# distillerone.net
KiCad netlist of a schematic drawn in EAGLE
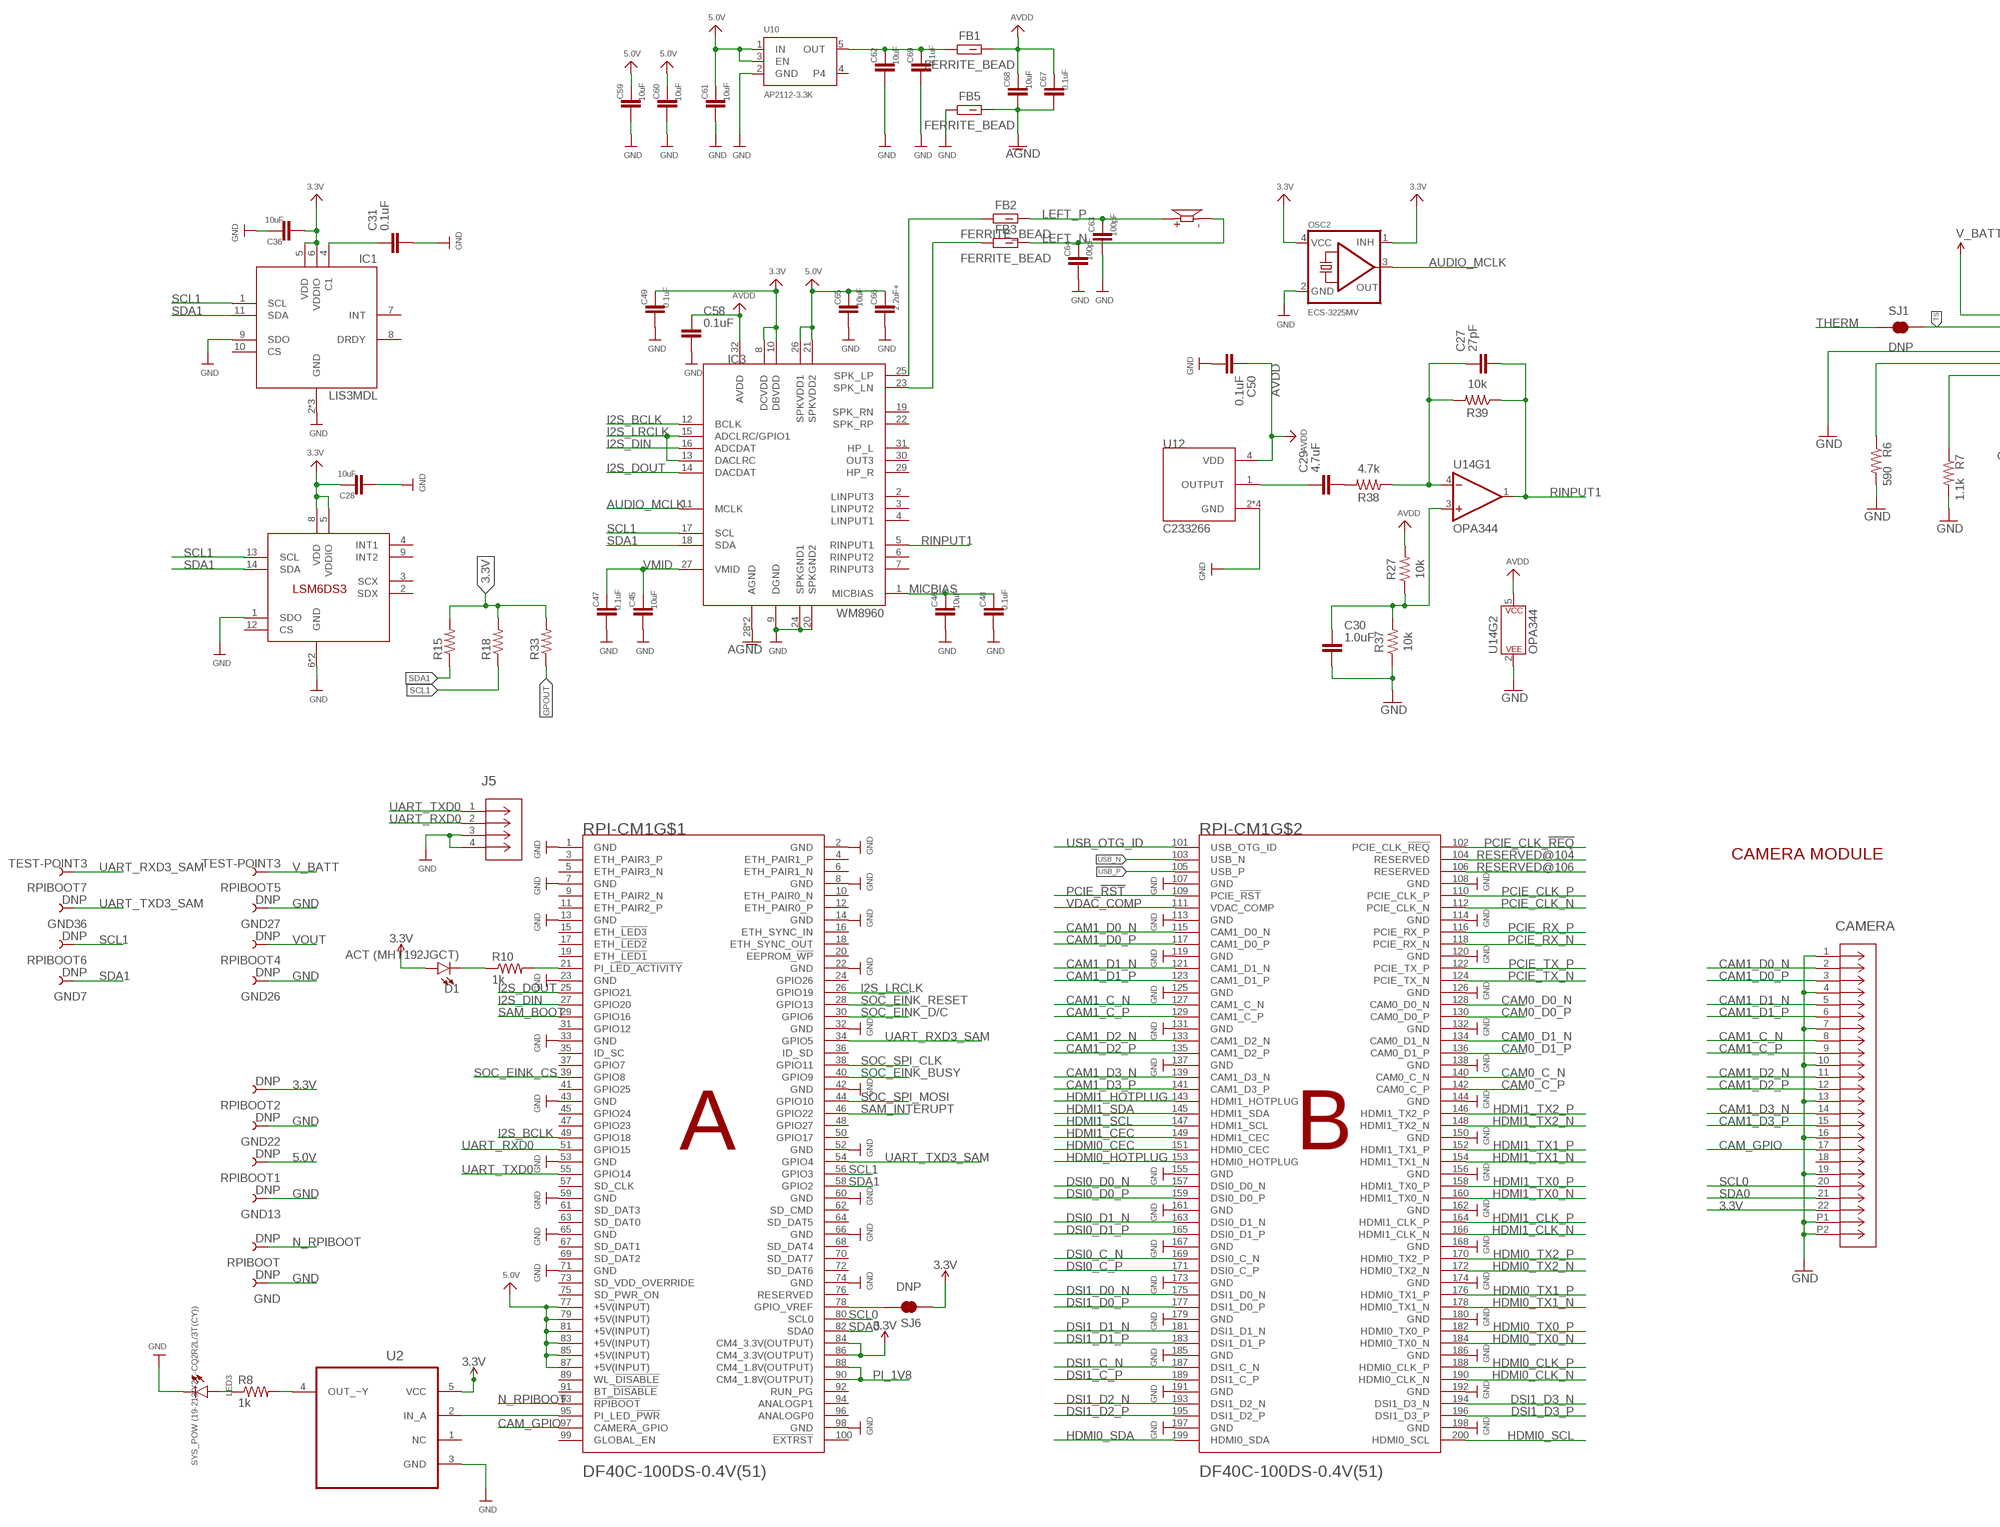
[diagram p0: schematic, sheet 1, part 1 of 3]
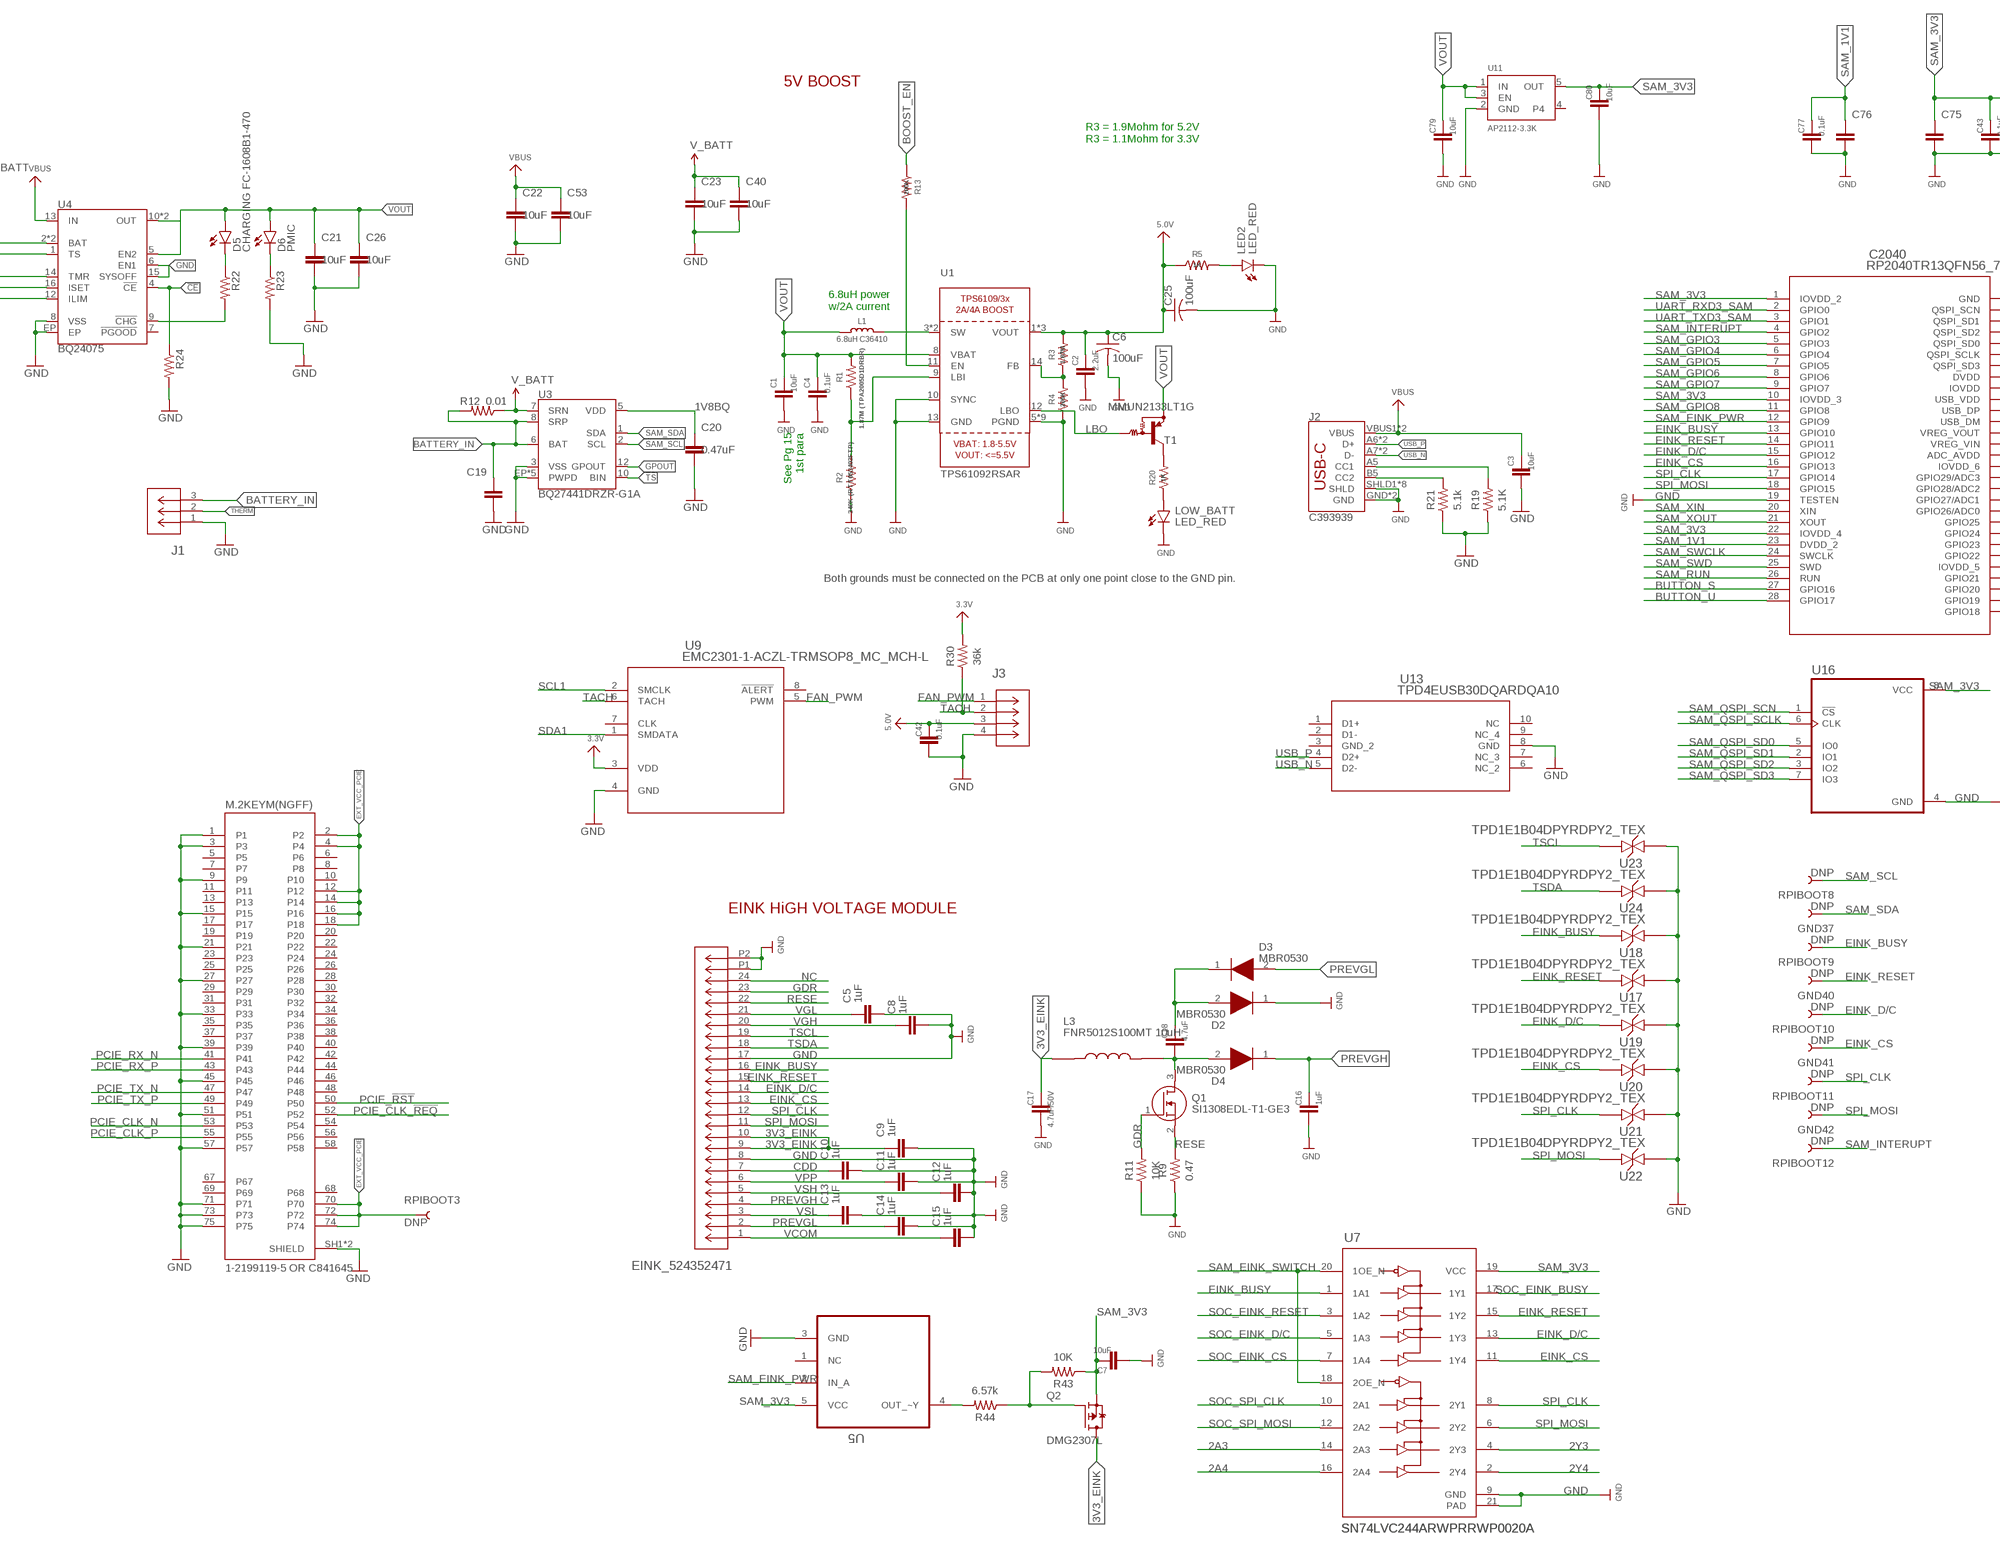
[diagram p1: schematic, sheet 1, part 2 of 3]
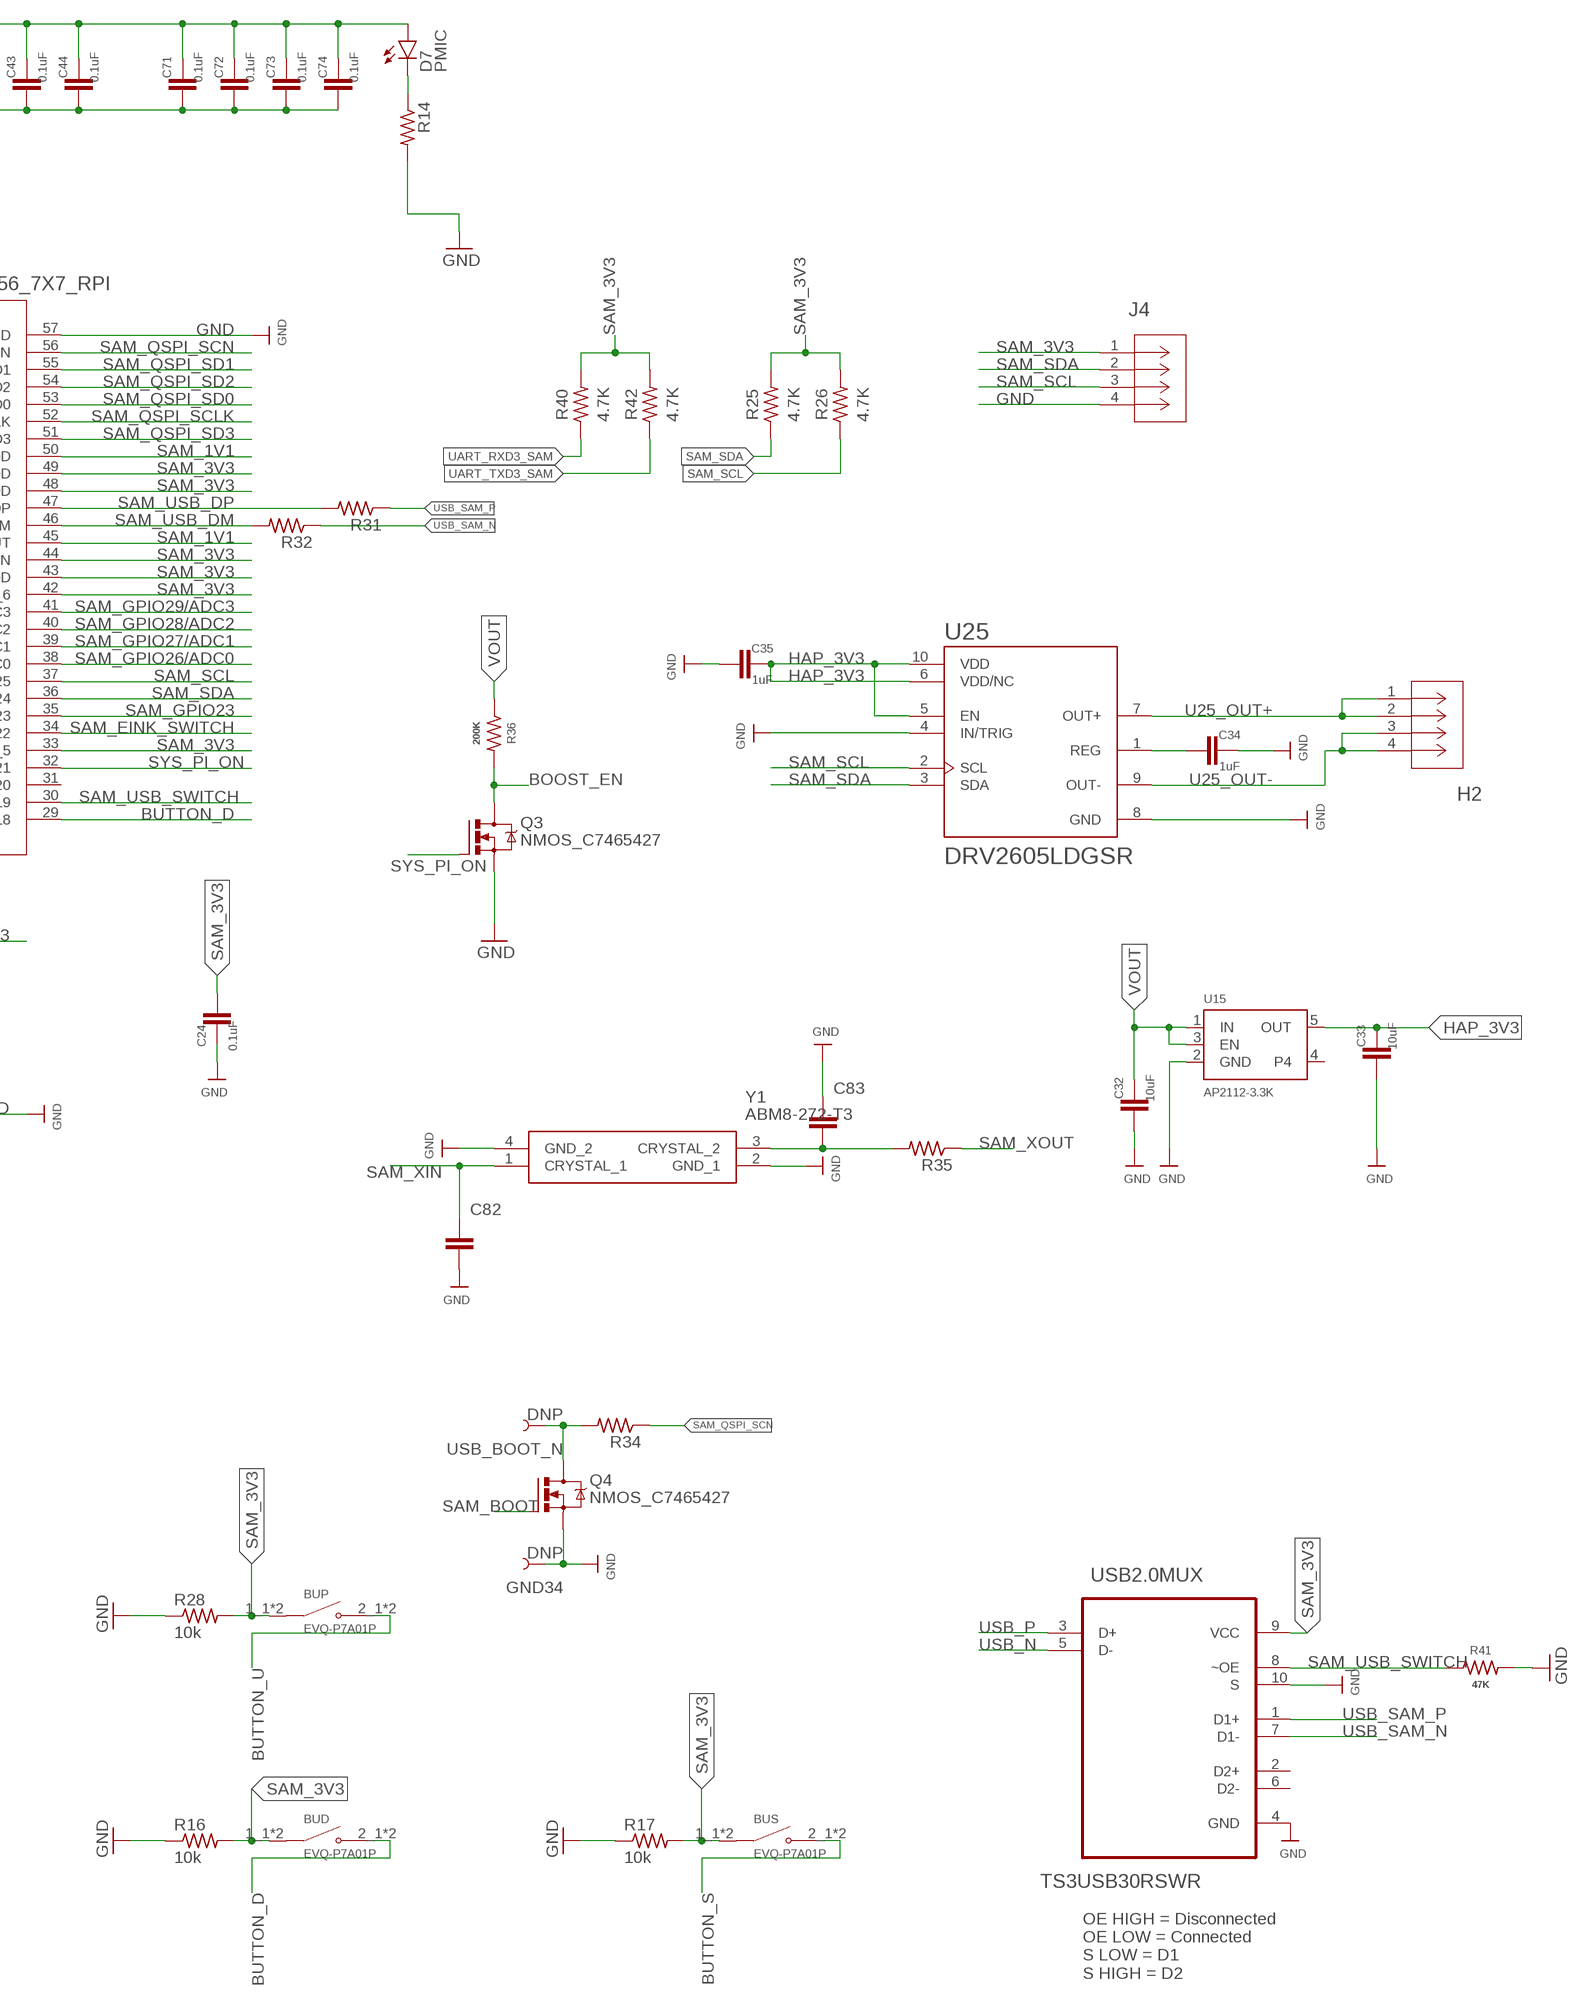
[diagram p2: schematic, sheet 1, part 3 of 3]

(export (version "E")
  (design (tool "Eeschema 10.0.6"))
  (components
    (comp (ref "BUD")
      (value "EVQ-P7A01P")
      (footprint "eagle-import:SW_EVQ-P7A01P")
      (fields (field (name "MANUFACTURER") "Panasonic Electronic Components"))
      (libsource (lib "eagle-import") (part "EVQ-P7A01P"))
    )
    (comp (ref "BUP")
      (value "EVQ-P7A01P")
      (footprint "eagle-import:SW_EVQ-P7A01P")
      (fields (field (name "MANUFACTURER") "Panasonic Electronic Components"))
      (libsource (lib "eagle-import") (part "EVQ-P7A01P"))
    )
    (comp (ref "BUS")
      (value "EVQ-P7A01P")
      (footprint "eagle-import:SW_EVQ-P7A01P")
      (fields (field (name "MANUFACTURER") "Panasonic Electronic Components"))
      (libsource (lib "eagle-import") (part "EVQ-P7A01P"))
    )
    (comp (ref "C1")
      (value "10uF")
      (footprint "eagle-import:CAPC1005X60")
      (libsource (lib "eagle-import") (part "CCHIP-0402(1005-METRIC)_"))
    )
    (comp (ref "C2")
      (value "2.2uF")
      (footprint "eagle-import:CAPC1005X60")
      (libsource (lib "eagle-import") (part "CCHIP-0402(1005-METRIC)_"))
    )
    (comp (ref "C3")
      (value "10uF")
      (footprint "eagle-import:CAPC1005X60")
      (libsource (lib "eagle-import") (part "CCHIP-0402(1005-METRIC)_"))
    )
    (comp (ref "C4")
      (value "0.1uF")
      (footprint "eagle-import:CAPC1005X60")
      (libsource (lib "eagle-import") (part "CCHIP-0402(1005-METRIC)_"))
    )
    (comp (ref "C5")
      (value "1uF")
      (footprint "eagle-import:CAPC1005X60")
      (libsource (lib "eagle-import") (part "CCHIP-0402(1005-METRIC)_"))
    )
    (comp (ref "C6")
      (value "100uF")
      (footprint "eagle-import:C1210")
      (libsource (lib "eagle-import") (part "C-USC1210"))
    )
    (comp (ref "C7")
      (value "10uF")
      (footprint "eagle-import:CAPC1005X60")
      (libsource (lib "eagle-import") (part "CCHIP-0402(1005-METRIC)_"))
    )
    (comp (ref "C8")
      (value "1uF")
      (footprint "eagle-import:CAPC1005X60")
      (libsource (lib "eagle-import") (part "CCHIP-0402(1005-METRIC)_"))
    )
    (comp (ref "C9")
      (value "1uF")
      (footprint "eagle-import:CAPC1005X60")
      (libsource (lib "eagle-import") (part "CCHIP-0402(1005-METRIC)_"))
    )
    (comp (ref "C10")
      (value "1uF")
      (footprint "eagle-import:CAPC1005X60")
      (libsource (lib "eagle-import") (part "CCHIP-0402(1005-METRIC)_"))
    )
    (comp (ref "C11")
      (value "1uF")
      (footprint "eagle-import:CAPC1005X60")
      (libsource (lib "eagle-import") (part "CCHIP-0402(1005-METRIC)_"))
    )
    (comp (ref "C12")
      (value "1uF")
      (footprint "eagle-import:CAPC1005X60")
      (libsource (lib "eagle-import") (part "CCHIP-0402(1005-METRIC)_"))
    )
    (comp (ref "C13")
      (value "1uF")
      (footprint "eagle-import:CAPC1005X60")
      (libsource (lib "eagle-import") (part "CCHIP-0402(1005-METRIC)_"))
    )
    (comp (ref "C14")
      (value "1uF")
      (footprint "eagle-import:CAPC1005X60")
      (libsource (lib "eagle-import") (part "CCHIP-0402(1005-METRIC)_"))
    )
    (comp (ref "C15")
      (value "1uF")
      (footprint "eagle-import:CAPC1005X60")
      (libsource (lib "eagle-import") (part "CCHIP-0402(1005-METRIC)_"))
    )
    (comp (ref "C16")
      (value "1uF")
      (footprint "eagle-import:CAPC1005X60")
      (libsource (lib "eagle-import") (part "CCHIP-0402(1005-METRIC)_"))
    )
    (comp (ref "C17")
      (value "4.7uF/50V")
      (footprint "eagle-import:CAPC1005X60")
      (libsource (lib "eagle-import") (part "CCHIP-0402(1005-METRIC)_"))
    )
    (comp (ref "C18")
      (value "4.7uF")
      (footprint "eagle-import:CAPC1608X85")
      (libsource (lib "eagle-import") (part "CCHIP-0603(1608-METRIC)_"))
    )
    (comp (ref "C19")
      (value "1.0uF")
      (footprint "eagle-import:CAPC1005X60")
      (libsource (lib "eagle-import") (part "CCHIP-0402(1005-METRIC)_"))
    )
    (comp (ref "C20")
      (value "0.47uF")
      (footprint "eagle-import:CAPC1005X60")
      (libsource (lib "eagle-import") (part "CCHIP-0402(1005-METRIC)_"))
    )
    (comp (ref "C21")
      (value "10uF")
      (footprint "eagle-import:CAPC1005X60")
      (libsource (lib "eagle-import") (part "CCHIP-0402(1005-METRIC)_"))
    )
    (comp (ref "C22")
      (value "10uF")
      (footprint "eagle-import:CAPC1005X60")
      (libsource (lib "eagle-import") (part "CCHIP-0402(1005-METRIC)_"))
    )
    (comp (ref "C23")
      (value "10uF")
      (footprint "eagle-import:CAPC1005X60")
      (libsource (lib "eagle-import") (part "CCHIP-0402(1005-METRIC)_"))
    )
    (comp (ref "C24")
      (value "0.1uF")
      (footprint "eagle-import:CAPC1005X60")
      (libsource (lib "eagle-import") (part "CCHIP-0402(1005-METRIC)_"))
    )
    (comp (ref "C25")
      (value "100uF")
      (footprint "eagle-import:C1210")
      (libsource (lib "eagle-import") (part "C-USC1210"))
    )
    (comp (ref "C26")
      (value "10uF")
      (footprint "eagle-import:CAPC1005X60")
      (libsource (lib "eagle-import") (part "CCHIP-0402(1005-METRIC)_"))
    )
    (comp (ref "C27")
      (value "27pF")
      (footprint "eagle-import:CAPC1005X60")
      (libsource (lib "eagle-import") (part "CCHIP-0402(1005-METRIC)_"))
    )
    (comp (ref "C28")
      (value "10uF")
      (footprint "eagle-import:CAPC1005X60")
      (libsource (lib "eagle-import") (part "CCHIP-0402(1005-METRIC)_"))
    )
    (comp (ref "C29")
      (value "4.7uF")
      (footprint "eagle-import:CAPC1005X60")
      (libsource (lib "eagle-import") (part "CCHIP-0402(1005-METRIC)_"))
    )
    (comp (ref "C30")
      (value "1.0uF")
      (footprint "eagle-import:CAPC1005X60")
      (libsource (lib "eagle-import") (part "CCHIP-0402(1005-METRIC)_"))
    )
    (comp (ref "C31")
      (value "0.1uF")
      (footprint "eagle-import:CAPC1005X60")
      (libsource (lib "eagle-import") (part "CCHIP-0402(1005-METRIC)_"))
    )
    (comp (ref "C32")
      (value "10uF")
      (footprint "eagle-import:CAPC1005X60")
      (libsource (lib "eagle-import") (part "CCHIP-0402(1005-METRIC)_"))
    )
    (comp (ref "C33")
      (value "10uF")
      (footprint "eagle-import:CAPC1005X60")
      (libsource (lib "eagle-import") (part "CCHIP-0402(1005-METRIC)_"))
    )
    (comp (ref "C34")
      (value "1uF")
      (footprint "eagle-import:CAPC1005X60")
      (libsource (lib "eagle-import") (part "CCHIP-0402(1005-METRIC)_"))
    )
    (comp (ref "C35")
      (value "1uF")
      (footprint "eagle-import:CAPC1005X60")
      (libsource (lib "eagle-import") (part "CCHIP-0402(1005-METRIC)_"))
    )
    (comp (ref "C36")
      (value "10uF")
      (footprint "eagle-import:CAPC1005X60")
      (libsource (lib "eagle-import") (part "CCHIP-0402(1005-METRIC)_"))
    )
    (comp (ref "C40")
      (value "10uF")
      (footprint "eagle-import:CAPC1005X60")
      (libsource (lib "eagle-import") (part "CCHIP-0402(1005-METRIC)_"))
    )
    (comp (ref "C42")
      (value "0.1uF")
      (footprint "eagle-import:CAPC1608X85")
      (libsource (lib "eagle-import") (part "CCHIP-0603(1608-METRIC)_"))
    )
    (comp (ref "C43")
      (value "0.1uF")
      (footprint "eagle-import:CAPC1005X60")
      (libsource (lib "eagle-import") (part "CCHIP-0402(1005-METRIC)_"))
    )
    (comp (ref "C44")
      (value "0.1uF")
      (footprint "eagle-import:CAPC1005X60")
      (libsource (lib "eagle-import") (part "CCHIP-0402(1005-METRIC)_"))
    )
    (comp (ref "C45")
      (value "10uF")
      (footprint "eagle-import:CAPC1005X60")
      (libsource (lib "eagle-import") (part "CCHIP-0402(1005-METRIC)_"))
    )
    (comp (ref "C46")
      (value "10uF")
      (footprint "eagle-import:CAPC1005X60")
      (libsource (lib "eagle-import") (part "CCHIP-0402(1005-METRIC)_"))
    )
    (comp (ref "C47")
      (value "0.1uF")
      (footprint "eagle-import:CAPC1005X60")
      (libsource (lib "eagle-import") (part "CCHIP-0402(1005-METRIC)_"))
    )
    (comp (ref "C48")
      (value "0.1uF")
      (footprint "eagle-import:CAPC1005X60")
      (libsource (lib "eagle-import") (part "CCHIP-0402(1005-METRIC)_"))
    )
    (comp (ref "C49")
      (value "0.1uF")
      (footprint "eagle-import:CAPC1005X60")
      (libsource (lib "eagle-import") (part "CCHIP-0402(1005-METRIC)_"))
    )
    (comp (ref "C50")
      (value "0.1uF")
      (footprint "eagle-import:CAPC1005X60")
      (libsource (lib "eagle-import") (part "CCHIP-0402(1005-METRIC)_"))
    )
    (comp (ref "C53")
      (value "10uF")
      (footprint "eagle-import:CAPC1005X60")
      (libsource (lib "eagle-import") (part "CCHIP-0402(1005-METRIC)_"))
    )
    (comp (ref "C58")
      (value "0.1uF")
      (footprint "eagle-import:CAPC1005X60")
      (libsource (lib "eagle-import") (part "CCHIP-0402(1005-METRIC)_"))
    )
    (comp (ref "C59")
      (value "10uF")
      (footprint "eagle-import:CAPC1005X60")
      (libsource (lib "eagle-import") (part "CCHIP-0402(1005-METRIC)_"))
    )
    (comp (ref "C60")
      (value "10uF")
      (footprint "eagle-import:CAPC1005X60")
      (libsource (lib "eagle-import") (part "CCHIP-0402(1005-METRIC)_"))
    )
    (comp (ref "C61")
      (value "10uF")
      (footprint "eagle-import:CAPC1005X60")
      (libsource (lib "eagle-import") (part "CCHIP-0402(1005-METRIC)_"))
    )
    (comp (ref "C62")
      (value "10uF")
      (footprint "eagle-import:CAPC1005X60")
      (libsource (lib "eagle-import") (part "CCHIP-0402(1005-METRIC)_"))
    )
    (comp (ref "C63")
      (value "100pF")
      (footprint "eagle-import:CAPC1005X60")
      (libsource (lib "eagle-import") (part "CCHIP-0402(1005-METRIC)_"))
    )
    (comp (ref "C64")
      (value "100pF")
      (footprint "eagle-import:CAPC1005X60")
      (libsource (lib "eagle-import") (part "CCHIP-0402(1005-METRIC)_"))
    )
    (comp (ref "C65")
      (value "10uF")
      (footprint "eagle-import:CAPC1005X60")
      (libsource (lib "eagle-import") (part "CCHIP-0402(1005-METRIC)_"))
    )
    (comp (ref "C66")
      (value "2.2uF+")
      (footprint "eagle-import:CAPC1005X60")
      (libsource (lib "eagle-import") (part "CCHIP-0402(1005-METRIC)_"))
    )
    (comp (ref "C67")
      (value "0.1uF")
      (footprint "eagle-import:CAPC1005X60")
      (libsource (lib "eagle-import") (part "CCHIP-0402(1005-METRIC)_"))
    )
    (comp (ref "C68")
      (value "10uF")
      (footprint "eagle-import:CAPC1005X60")
      (libsource (lib "eagle-import") (part "CCHIP-0402(1005-METRIC)_"))
    )
    (comp (ref "C69")
      (value "0.1uF")
      (footprint "eagle-import:CAPC1005X60")
      (libsource (lib "eagle-import") (part "CCHIP-0402(1005-METRIC)_"))
    )
    (comp (ref "C71")
      (value "0.1uF")
      (footprint "eagle-import:CAPC1005X60")
      (libsource (lib "eagle-import") (part "CCHIP-0402(1005-METRIC)_"))
    )
    (comp (ref "C72")
      (value "0.1uF")
      (footprint "eagle-import:CAPC1005X60")
      (libsource (lib "eagle-import") (part "CCHIP-0402(1005-METRIC)_"))
    )
    (comp (ref "C73")
      (value "0.1uF")
      (footprint "eagle-import:CAPC1005X60")
      (libsource (lib "eagle-import") (part "CCHIP-0402(1005-METRIC)_"))
    )
    (comp (ref "C74")
      (value "0.1uF")
      (footprint "eagle-import:CAPC1005X60")
      (libsource (lib "eagle-import") (part "CCHIP-0402(1005-METRIC)_"))
    )
    (comp (ref "C75")
      (value "1.0uF")
      (footprint "eagle-import:CAPC1005X60")
      (libsource (lib "eagle-import") (part "CCHIP-0402(1005-METRIC)_"))
    )
    (comp (ref "C76")
      (value "1.0uF")
      (footprint "eagle-import:CAPC1005X60")
      (libsource (lib "eagle-import") (part "CCHIP-0402(1005-METRIC)_"))
    )
    (comp (ref "C77")
      (value "0.1uF")
      (footprint "eagle-import:CAPC1005X60")
      (libsource (lib "eagle-import") (part "CCHIP-0402(1005-METRIC)_"))
    )
    (comp (ref "C79")
      (value "10uF")
      (footprint "eagle-import:CAPC1005X60")
      (libsource (lib "eagle-import") (part "CCHIP-0402(1005-METRIC)_"))
    )
    (comp (ref "C80")
      (value "10uF")
      (footprint "eagle-import:CAPC1005X60")
      (libsource (lib "eagle-import") (part "CCHIP-0402(1005-METRIC)_"))
    )
    (comp (ref "C82")
      (value "15p")
      (footprint "eagle-import:CAPC1005X60")
      (libsource (lib "eagle-import") (part "CCHIP-0402(1005-METRIC)_"))
    )
    (comp (ref "C83")
      (value "15p")
      (footprint "eagle-import:CAPC1005X60")
      (libsource (lib "eagle-import") (part "CCHIP-0402(1005-METRIC)_"))
    )
    (comp (ref "C2040")
      (value "RP2040TR13QFN56_7X7_RPI")
      (footprint "eagle-import:QFN56_7X7_RPI")
      (fields
        (field (name "MANUFACTURER_PART_NUMBER") "RP2040TR13")
        (field (name "COPYRIGHT") "Copyright (C) 2024 Ultra Librarian. All rights reserved.")
      )
      (libsource (lib "eagle-import") (part "RP2040TR13QFN56_7X7_RPI"))
    )
    (comp (ref "CAMERA")
      (value "C262642")
      (footprint "eagle-import:CON_524372271_MOL")
      (fields
        (field (name "MANUFACTURER_PART_NUMBER") "524372271")
        (field (name "COPYRIGHT") "Copyright (C) 2024 Ultra Librarian. All rights reserved.")
      )
      (libsource (lib "eagle-import") (part "524372271CON_524372271_MOL"))
    )
    (comp (ref "D1")
      (value "ACT (MHT192JGCT)")
      (footprint "eagle-import:LED-0603@1")
      (libsource (lib "eagle-import") (part "LED-GREEN0603"))
    )
    (comp (ref "D2")
      (value "MBR0530")
      (footprint "eagle-import:SOD3716X135N")
      (fields (field (name "MF") "ON Semiconductor"))
      (libsource (lib "eagle-import") (part "MBR0530"))
    )
    (comp (ref "D3")
      (value "MBR0530")
      (footprint "eagle-import:SOD3716X135N")
      (fields (field (name "MF") "ON Semiconductor"))
      (libsource (lib "eagle-import") (part "MBR0530"))
    )
    (comp (ref "D4")
      (value "MBR0530")
      (footprint "eagle-import:SOD3716X135N")
      (fields (field (name "MF") "ON Semiconductor"))
      (libsource (lib "eagle-import") (part "MBR0530"))
    )
    (comp (ref "D5")
      (value "CHARGING FC-1608B1-470")
      (footprint "eagle-import:LED-0603")
      (libsource (lib "eagle-import") (part "LED-BLUE0603"))
    )
    (comp (ref "D6")
      (value "PMIC")
      (footprint "eagle-import:LED-0603")
      (libsource (lib "eagle-import") (part "LED-RED0603"))
    )
    (comp (ref "D7")
      (value "PMIC")
      (footprint "eagle-import:LED-0603")
      (libsource (lib "eagle-import") (part "LED-RED0603"))
    )
    (comp (ref "EINK_524352471")
      (value "524372471")
      (footprint "eagle-import:CON_524372471_MOL")
      (fields (field (name "COPYRIGHT") "Copyright (C) 2024 Ultra Librarian. All rights reserved."))
      (libsource (lib "eagle-import") (part "524372471CON_524372471_MOL"))
    )
    (comp (ref "FB1")
      (value "FERRITE_BEAD")
      (footprint "eagle-import:BEADC1608X95N")
      (libsource (lib "eagle-import") (part "FBCHIP-0603(1608-METRIC)"))
    )
    (comp (ref "FB2")
      (value "FERRITE_BEAD")
      (footprint "eagle-import:BEADC1608X95N")
      (libsource (lib "eagle-import") (part "FBCHIP-0603(1608-METRIC)"))
    )
    (comp (ref "FB3")
      (value "FERRITE_BEAD")
      (footprint "eagle-import:BEADC1608X95N")
      (libsource (lib "eagle-import") (part "FBCHIP-0603(1608-METRIC)"))
    )
    (comp (ref "FB5")
      (value "FERRITE_BEAD")
      (footprint "eagle-import:BEADC1608X95N")
      (libsource (lib "eagle-import") (part "FBCHIP-0603(1608-METRIC)"))
    )
    (comp (ref "GND")
      (value "DNP")
      (footprint "eagle-import:PAD.03X.03")
      (libsource (lib "eagle-import") (part "TEST-POINT3"))
    )
    (comp (ref "GND7")
      (value "DNP")
      (footprint "eagle-import:PAD.03X.03")
      (libsource (lib "eagle-import") (part "TEST-POINT3"))
    )
    (comp (ref "GND13")
      (value "DNP")
      (footprint "eagle-import:PAD.03X.03")
      (libsource (lib "eagle-import") (part "TEST-POINT3"))
    )
    (comp (ref "GND22")
      (value "DNP")
      (footprint "eagle-import:PAD.03X.03")
      (libsource (lib "eagle-import") (part "TEST-POINT3"))
    )
    (comp (ref "GND26")
      (value "DNP")
      (footprint "eagle-import:PAD.03X.03")
      (libsource (lib "eagle-import") (part "TEST-POINT3"))
    )
    (comp (ref "GND27")
      (value "DNP")
      (footprint "eagle-import:PAD.03X.03")
      (libsource (lib "eagle-import") (part "TEST-POINT3"))
    )
    (comp (ref "GND34")
      (value "DNP")
      (footprint "eagle-import:PAD.03X.03")
      (libsource (lib "eagle-import") (part "TEST-POINT3"))
    )
    (comp (ref "GND36")
      (value "DNP")
      (footprint "eagle-import:PAD.03X.03")
      (libsource (lib "eagle-import") (part "TEST-POINT3"))
    )
    (comp (ref "GND37")
      (value "DNP")
      (footprint "eagle-import:PAD.03X.03")
      (libsource (lib "eagle-import") (part "TEST-POINT3"))
    )
    (comp (ref "GND40")
      (value "DNP")
      (footprint "eagle-import:PAD.03X.03")
      (libsource (lib "eagle-import") (part "TEST-POINT3"))
    )
    (comp (ref "GND41")
      (value "DNP")
      (footprint "eagle-import:PAD.03X.03")
      (libsource (lib "eagle-import") (part "TEST-POINT3"))
    )
    (comp (ref "GND42")
      (value "DNP")
      (footprint "eagle-import:PAD.03X.03")
      (libsource (lib "eagle-import") (part "TEST-POINT3"))
    )
    (comp (ref "H2")
      (value "BM04B-SRSS-TBCONN4_BM04B-SRSS_JST")
      (footprint "eagle-import:CONN4_BM04B-SRSS_JST")
      (fields
        (field (name "MANUFACTURER_PART_NUMBER") "BM04B-SRSS-TB")
        (field (name "COPYRIGHT") "Copyright (C) 2024 Ultra Librarian. All rights reserved.")
      )
      (libsource (lib "eagle-import") (part "BM04B-SRSS-TBCONN4_BM04B-SRSS_JST"))
    )
    (comp (ref "IC1")
      (value "LIS3MDL")
      (footprint "eagle-import:LGA12_2X2MM")
      (libsource (lib "eagle-import") (part "LIS3MDL"))
    )
    (comp (ref "IC3")
      (value "WM8960")
      (footprint "eagle-import:QFN32_5MM")
      (libsource (lib "eagle-import") (part "WM8960"))
    )
    (comp (ref "J1")
      (value "SM03B-SRSS-TBCONN_SM03B-SRSS-TB_JST")
      (footprint "eagle-import:CONN_SM03B-SRSS-TB_JST")
      (fields
        (field (name "MANUFACTURER_PART_NUMBER") "SM03B-SRSS-TB")
        (field (name "COPYRIGHT") "Copyright (C) 2024 Ultra Librarian. All rights reserved.")
      )
      (libsource (lib "eagle-import") (part "SM03B-SRSS-TBCONN_SM03B-SRSS-TB_JST"))
    )
    (comp (ref "J2")
      (value "C393939")
      (footprint "eagle-import:USB-C-16P")
      (libsource (lib "eagle-import") (part "USB_C16PIN"))
    )
    (comp (ref "J3")
      (value "BM04B-SRSS-TBCONN4_BM04B-SRSS_JST")
      (footprint "eagle-import:CONN4_BM04B-SRSS_JST")
      (fields
        (field (name "MANUFACTURER_PART_NUMBER") "BM04B-SRSS-TB")
        (field (name "COPYRIGHT") "Copyright (C) 2024 Ultra Librarian. All rights reserved.")
      )
      (libsource (lib "eagle-import") (part "BM04B-SRSS-TBCONN4_BM04B-SRSS_JST"))
    )
    (comp (ref "J4")
      (value "BM04B-SRSS-TBCONN4_BM04B-SRSS_JST")
      (footprint "eagle-import:CONN4_BM04B-SRSS_JST")
      (fields
        (field (name "MANUFACTURER_PART_NUMBER") "BM04B-SRSS-TB")
        (field (name "COPYRIGHT") "Copyright (C) 2024 Ultra Librarian. All rights reserved.")
      )
      (libsource (lib "eagle-import") (part "BM04B-SRSS-TBCONN4_BM04B-SRSS_JST"))
    )
    (comp (ref "J5")
      (value "BM04B-SRSS-TBCONN4_BM04B-SRSS_JST")
      (footprint "eagle-import:CONN4_BM04B-SRSS_JST")
      (fields
        (field (name "MANUFACTURER_PART_NUMBER") "BM04B-SRSS-TB")
        (field (name "COPYRIGHT") "Copyright (C) 2024 Ultra Librarian. All rights reserved.")
      )
      (libsource (lib "eagle-import") (part "BM04B-SRSS-TBCONN4_BM04B-SRSS_JST"))
    )
    (comp (ref "L1")
      (value "6.8uH C36410")
      (footprint "eagle-import:INDUCTOR_5X5MM_TDK_VLC5045")
      (libsource (lib "eagle-import") (part "INDUCTORTDK_VLC5045"))
    )
    (comp (ref "L3")
      (value "FNR5012S100MT 10uH")
      (footprint "eagle-import:IND_LQH5BPN2R2NT0L")
      (fields (field (name "MANUFACTURER") "Murata"))
      (libsource (lib "eagle-import") (part "LQH5BPN2R2NT0L"))
    )
    (comp (ref "LED2")
      (value "LED_RED")
      (footprint "eagle-import:LEDC1608X65N_RND-R")
      (libsource (lib "eagle-import") (part "CHIP-ROUND-R_0603"))
    )
    (comp (ref "LED3")
      (value "SYS_POW (19-213/Y2C-CQ2R2L/3T(CY))")
      (footprint "eagle-import:LED-0603")
      (libsource (lib "eagle-import") (part "LED0603"))
    )
    (comp (ref "LOW_BATT")
      (value "LED_RED")
      (footprint "eagle-import:LEDC1608X65N_RND-R")
      (libsource (lib "eagle-import") (part "CHIP-ROUND-R_0603"))
    )
    (comp (ref "LS1")
      (value "CMS-18138A-SP")
      (footprint "eagle-import:CUI_CMS-18138A-SP")
      (fields (field (name "MF") "CUI Devices"))
      (libsource (lib "eagle-import") (part "CMS-18138A-SP"))
    )
    (comp (ref "M.2KEYM(NGFF)")
      (value "1-2199119-5 OR C841645")
      (footprint "eagle-import:TE_1-2199119-5")
      (fields
        (field (name "COMMENT") "1-2199119-5")
        (field (name "DIGIKEY_PART_NUMBER") "A115902TR-ND")
        (field (name "MF") "TE Connectivity")
      )
      (libsource (lib "eagle-import") (part "1-2199119-5"))
    )
    (comp (ref "OSC2")
      (value "ECS-3225MV")
      (footprint "eagle-import:OSC_3.2X2.5MM")
      (libsource (lib "eagle-import") (part "OSCILLATOR3.2X2.5"))
    )
    (comp (ref "Q1")
      (value "SI1308EDL-T1-GE3")
      (footprint "eagle-import:SOT65P210X110-3N")
      (fields (field (name "MF") "Vishay Siliconix"))
      (libsource (lib "eagle-import") (part "SI1308EDL-T1-GE3"))
    )
    (comp (ref "Q2")
      (value "DMG2307L")
      (footprint "eagle-import:SOT96P240X110-3N")
      (fields (field (name "MF") "Diodes Inc."))
      (libsource (lib "eagle-import") (part "DMG2307L"))
    )
    (comp (ref "Q3")
      (value "NMOS_C7465427")
      (footprint "eagle-import:SOT23")
      (libsource (lib "eagle-import") (part "NMOSFETSOT23-GSD"))
    )
    (comp (ref "Q4")
      (value "NMOS_C7465427")
      (footprint "eagle-import:SOT23")
      (libsource (lib "eagle-import") (part "NMOSFETSOT23-GSD"))
    )
    (comp (ref "R1")
      (value "1.87M (TPA2005D1DRBR)")
      (footprint "eagle-import:RESC1005X40")
      (libsource (lib "eagle-import") (part "R-USCHIP-0402(1005-METRIC)_"))
    )
    (comp (ref "R2")
      (value "340K (RTT053403FTP)")
      (footprint "eagle-import:RESC1005X40")
      (libsource (lib "eagle-import") (part "R-USCHIP-0402(1005-METRIC)_"))
    )
    (comp (ref "R3")
      (value "1.87M")
      (footprint "eagle-import:RESC1005X40")
      (libsource (lib "eagle-import") (part "R-USCHIP-0402(1005-METRIC)_"))
    )
    (comp (ref "R4")
      (value "200K")
      (footprint "eagle-import:RESC1005X40")
      (libsource (lib "eagle-import") (part "R-USCHIP-0402(1005-METRIC)_"))
    )
    (comp (ref "R5")
      (value "1K")
      (footprint "eagle-import:RESC1005X40")
      (libsource (lib "eagle-import") (part "R-USCHIP-0402(1005-METRIC)_"))
    )
    (comp (ref "R6")
      (value "590")
      (footprint "eagle-import:RESC1005X40")
      (libsource (lib "eagle-import") (part "R-USCHIP-0402(1005-METRIC)_"))
    )
    (comp (ref "R7")
      (value "1.1k")
      (footprint "eagle-import:RESC1005X40")
      (libsource (lib "eagle-import") (part "R-USCHIP-0402(1005-METRIC)_"))
    )
    (comp (ref "R8")
      (value "1k")
      (footprint "eagle-import:RESC1005X40")
      (libsource (lib "eagle-import") (part "R-USCHIP-0402(1005-METRIC)_"))
    )
    (comp (ref "R9")
      (value "0.47")
      (footprint "eagle-import:RESC1005X40")
      (libsource (lib "eagle-import") (part "R-USCHIP-0402(1005-METRIC)_"))
    )
    (comp (ref "R10")
      (value "1k")
      (footprint "eagle-import:RESC1005X40")
      (libsource (lib "eagle-import") (part "R-USCHIP-0402(1005-METRIC)_"))
    )
    (comp (ref "R11")
      (value "10K")
      (footprint "eagle-import:RESC1005X40")
      (libsource (lib "eagle-import") (part "R-USCHIP-0402(1005-METRIC)_"))
    )
    (comp (ref "R12")
      (value "0.01")
      (footprint "eagle-import:1206")
      (libsource (lib "eagle-import") (part "RESISTOR1206"))
    )
    (comp (ref "R13")
      (value "200K")
      (footprint "eagle-import:RESC1005X40")
      (libsource (lib "eagle-import") (part "R-USCHIP-0402(1005-METRIC)_"))
    )
    (comp (ref "R14")
      (value "1K")
      (footprint "eagle-import:RESC1005X40")
      (libsource (lib "eagle-import") (part "R-USCHIP-0402(1005-METRIC)_"))
    )
    (comp (ref "R15")
      (value "4.7K")
      (footprint "eagle-import:RESC1005X40")
      (libsource (lib "eagle-import") (part "R-USCHIP-0402(1005-METRIC)_"))
    )
    (comp (ref "R16")
      (value "10k")
      (footprint "eagle-import:RESC1005X40")
      (libsource (lib "eagle-import") (part "R-USCHIP-0402(1005-METRIC)_"))
    )
    (comp (ref "R17")
      (value "10k")
      (footprint "eagle-import:RESC1005X40")
      (libsource (lib "eagle-import") (part "R-USCHIP-0402(1005-METRIC)_"))
    )
    (comp (ref "R18")
      (value "4.7K")
      (footprint "eagle-import:RESC1005X40")
      (libsource (lib "eagle-import") (part "R-USCHIP-0402(1005-METRIC)_"))
    )
    (comp (ref "R19")
      (value "5.1K")
      (footprint "eagle-import:RESC1005X40")
      (libsource (lib "eagle-import") (part "R-USCHIP-0402(1005-METRIC)_"))
    )
    (comp (ref "R20")
      (value "1K")
      (footprint "eagle-import:RESC1005X40")
      (libsource (lib "eagle-import") (part "R-USCHIP-0402(1005-METRIC)_"))
    )
    (comp (ref "R21")
      (value "5.1k")
      (footprint "eagle-import:RESC1005X40")
      (libsource (lib "eagle-import") (part "R-USCHIP-0402(1005-METRIC)_"))
    )
    (comp (ref "R22")
      (value "180")
      (footprint "eagle-import:RESC1005X40")
      (libsource (lib "eagle-import") (part "R-USCHIP-0402(1005-METRIC)_"))
    )
    (comp (ref "R23")
      (value "1K")
      (footprint "eagle-import:RESC1005X40")
      (libsource (lib "eagle-import") (part "R-USCHIP-0402(1005-METRIC)_"))
    )
    (comp (ref "R24")
      (value "100k")
      (footprint "eagle-import:RESC1005X40")
      (libsource (lib "eagle-import") (part "R-USCHIP-0402(1005-METRIC)_"))
    )
    (comp (ref "R25")
      (value "4.7K")
      (footprint "eagle-import:RESC1005X40")
      (libsource (lib "eagle-import") (part "R-USCHIP-0402(1005-METRIC)_"))
    )
    (comp (ref "R26")
      (value "4.7K")
      (footprint "eagle-import:RESC1005X40")
      (libsource (lib "eagle-import") (part "R-USCHIP-0402(1005-METRIC)_"))
    )
    (comp (ref "R27")
      (value "10k")
      (footprint "eagle-import:RESC1005X40")
      (libsource (lib "eagle-import") (part "R-USCHIP-0402(1005-METRIC)_"))
    )
    (comp (ref "R28")
      (value "10k")
      (footprint "eagle-import:RESC1005X40")
      (libsource (lib "eagle-import") (part "R-USCHIP-0402(1005-METRIC)_"))
    )
    (comp (ref "R30")
      (value "36k")
      (footprint "eagle-import:RESC1005X40")
      (libsource (lib "eagle-import") (part "R-USCHIP-0402(1005-METRIC)_"))
    )
    (comp (ref "R31")
      (value "27")
      (footprint "eagle-import:RESC1005X40")
      (libsource (lib "eagle-import") (part "R-USCHIP-0402(1005-METRIC)_"))
    )
    (comp (ref "R32")
      (value "27")
      (footprint "eagle-import:RESC1005X40")
      (libsource (lib "eagle-import") (part "R-USCHIP-0402(1005-METRIC)_"))
    )
    (comp (ref "R33")
      (value "10K")
      (footprint "eagle-import:RESC1005X40")
      (libsource (lib "eagle-import") (part "R-USCHIP-0402(1005-METRIC)_"))
    )
    (comp (ref "R34")
      (value "1k")
      (footprint "eagle-import:RESC1005X40")
      (libsource (lib "eagle-import") (part "R-USCHIP-0402(1005-METRIC)_"))
    )
    (comp (ref "R35")
      (value "1k")
      (footprint "eagle-import:RESC1005X40")
      (libsource (lib "eagle-import") (part "R-USCHIP-0402(1005-METRIC)_"))
    )
    (comp (ref "R36")
      (value "200K")
      (footprint "eagle-import:RESC1005X40")
      (libsource (lib "eagle-import") (part "R-USCHIP-0402(1005-METRIC)_"))
    )
    (comp (ref "R37")
      (value "10k")
      (footprint "eagle-import:RESC1005X40")
      (libsource (lib "eagle-import") (part "R-USCHIP-0402(1005-METRIC)_"))
    )
    (comp (ref "R38")
      (value "4.7k")
      (footprint "eagle-import:RESC1005X40")
      (libsource (lib "eagle-import") (part "R-USCHIP-0402(1005-METRIC)_"))
    )
    (comp (ref "R39")
      (value "10k")
      (footprint "eagle-import:RESC1005X40")
      (libsource (lib "eagle-import") (part "R-USCHIP-0402(1005-METRIC)_"))
    )
    (comp (ref "R40")
      (value "4.7K")
      (footprint "eagle-import:RESC1005X40")
      (libsource (lib "eagle-import") (part "R-USCHIP-0402(1005-METRIC)_"))
    )
    (comp (ref "R41")
      (value "47K")
      (footprint "eagle-import:RESC1005X40")
      (libsource (lib "eagle-import") (part "R-USCHIP-0402(1005-METRIC)_"))
    )
    (comp (ref "R42")
      (value "4.7K")
      (footprint "eagle-import:RESC1005X40")
      (libsource (lib "eagle-import") (part "R-USCHIP-0402(1005-METRIC)_"))
    )
    (comp (ref "R43")
      (value "10K")
      (footprint "eagle-import:RESC1005X40")
      (libsource (lib "eagle-import") (part "R-USCHIP-0402(1005-METRIC)_"))
    )
    (comp (ref "R44")
      (value "6.57k")
      (footprint "eagle-import:RESC1005X40")
      (libsource (lib "eagle-import") (part "R-USCHIP-0402(1005-METRIC)_"))
    )
    (comp (ref "RPI-CM1")
      (value "DF40C-100DS-0.4V(51)")
      (footprint "eagle-import:RPI-CM4")
      (libsource (lib "eagle-import") (part "RPI-CM4"))
    )
    (comp (ref "RPIBOOT")
      (value "DNP")
      (footprint "eagle-import:PAD.03X.03")
      (libsource (lib "eagle-import") (part "TEST-POINT3"))
    )
    (comp (ref "RPIBOOT1")
      (value "DNP")
      (footprint "eagle-import:PAD.03X.03")
      (libsource (lib "eagle-import") (part "TEST-POINT3"))
    )
    (comp (ref "RPIBOOT2")
      (value "DNP")
      (footprint "eagle-import:PAD.03X.03")
      (libsource (lib "eagle-import") (part "TEST-POINT3"))
    )
    (comp (ref "RPIBOOT3")
      (value "DNP")
      (footprint "eagle-import:PAD.03X.03")
      (libsource (lib "eagle-import") (part "TEST-POINT3"))
    )
    (comp (ref "RPIBOOT4")
      (value "DNP")
      (footprint "eagle-import:PAD.03X.03")
      (libsource (lib "eagle-import") (part "TEST-POINT3"))
    )
    (comp (ref "RPIBOOT5")
      (value "TEST-POINT3")
      (footprint "eagle-import:PAD.03X.03")
      (libsource (lib "eagle-import") (part "TEST-POINT3"))
    )
    (comp (ref "RPIBOOT6")
      (value "DNP")
      (footprint "eagle-import:PAD.03X.03")
      (libsource (lib "eagle-import") (part "TEST-POINT3"))
    )
    (comp (ref "RPIBOOT7")
      (value "TEST-POINT3")
      (footprint "eagle-import:PAD.03X.03")
      (libsource (lib "eagle-import") (part "TEST-POINT3"))
    )
    (comp (ref "RPIBOOT8")
      (value "DNP")
      (footprint "eagle-import:PAD.03X.03")
      (libsource (lib "eagle-import") (part "TEST-POINT3"))
    )
    (comp (ref "RPIBOOT9")
      (value "DNP")
      (footprint "eagle-import:PAD.03X.03")
      (libsource (lib "eagle-import") (part "TEST-POINT3"))
    )
    (comp (ref "RPIBOOT10")
      (value "DNP")
      (footprint "eagle-import:PAD.03X.03")
      (libsource (lib "eagle-import") (part "TEST-POINT3"))
    )
    (comp (ref "RPIBOOT11")
      (value "DNP")
      (footprint "eagle-import:PAD.03X.03")
      (libsource (lib "eagle-import") (part "TEST-POINT3"))
    )
    (comp (ref "RPIBOOT12")
      (value "DNP")
      (footprint "eagle-import:PAD.03X.03")
      (libsource (lib "eagle-import") (part "TEST-POINT3"))
    )
    (comp (ref "SJ1")
      (value "DNP")
      (footprint "eagle-import:PAD-JUMPER-2-NC_BY_TRACE_YES_SILK")
      (libsource (lib "eagle-import") (part "JUMPER-PAD-2-NC_BY_TRACE"))
    )
    (comp (ref "SJ6")
      (value "DNP")
      (footprint "eagle-import:PAD-JUMPER-2-NC_BY_TRACE_YES_SILK")
      (libsource (lib "eagle-import") (part "JUMPER-PAD-2-NC_BY_TRACE"))
    )
    (comp (ref "T1")
      (value "MMUN2133LT1G")
      (footprint "eagle-import:SC59-BEC")
      (libsource (lib "eagle-import") (part "-PNP_DRIVER-SC59-BECMUN2114T1"))
    )
    (comp (ref "U1")
      (value "TPS61092RSAR")
      (footprint "eagle-import:PVQFN-16")
      (libsource (lib "eagle-import") (part "VREG_TPS6103X"))
    )
    (comp (ref "U2")
      (value "MC74VHC1G14DFT1G")
      (footprint "eagle-import:SOT65P210X110-5N")
      (fields (field (name "MF") "ON Semiconductor"))
      (libsource (lib "eagle-import") (part "MC74VHC1G14DFT1G"))
    )
    (comp (ref "U3")
      (value "BQ27441DRZR-G1A")
      (footprint "eagle-import:PDSO-N12")
      (libsource (lib "eagle-import") (part "BQ27441-G1"))
    )
    (comp (ref "U4")
      (value "BQ24075")
      (footprint "eagle-import:PVQFN-N16")
      (libsource (lib "eagle-import") (part "BQ24075"))
    )
    (comp (ref "U5")
      (value "MC74VHC1G14DFT1G OR C66196")
      (footprint "eagle-import:SOT65P210X110-5N")
      (fields (field (name "MF") "ON Semiconductor") (field (name "MP") "MC74VHC1G14DFT1G"))
      (libsource (lib "eagle-import") (part "MC74VHC1G14DFT1G"))
    )
    (comp (ref "U6")
      (value "LSM6DS3")
      (footprint "eagle-import:LGA-14L")
      (libsource (lib "eagle-import") (part "LSM6DS3"))
    )
    (comp (ref "U7")
      (value "SN74LVC244ARWPRRWP0020A")
      (footprint "eagle-import:RWP0020A")
      (fields
        (field (name "MANUFACTURER_PART_NUMBER") "SN74LVC244ARWPR")
        (field (name "COPYRIGHT") "Copyright (C) 2024 Ultra Librarian. All rights reserved.")
      )
      (libsource (lib "eagle-import") (part "SN74LVC244ARWPRRWP0020A"))
    )
    (comp (ref "U9")
      (value "EMC2301-1-ACZL-TRMSOP8_MC_MCH-L")
      (footprint "eagle-import:MSOP8_MC_MCH-L")
      (fields
        (field (name "MANUFACTURER_PART_NUMBER") "EMC2301-1-ACZL-TR")
        (field (name "COPYRIGHT") "Copyright (C) 2024 Ultra Librarian. All rights reserved.")
      )
      (libsource (lib "eagle-import") (part "EMC2301-1-ACZL-TRMSOP8_MC_MCH-L"))
    )
    (comp (ref "U10")
      (value "AP2112-3.3K")
      (footprint "eagle-import:SOT23-5")
      (libsource (lib "eagle-import") (part "VREG_SOT23-5"))
    )
    (comp (ref "U11")
      (value "AP2112-3.3K")
      (footprint "eagle-import:SOT23-5")
      (libsource (lib "eagle-import") (part "VREG_SOT23-5"))
    )
    (comp (ref "U12")
      (value "C233266")
      (footprint "eagle-import:XDCR_SPU0410LR5H-QB")
      (fields (field (name "MANUFACTURER") "KNOWLES"))
      (libsource (lib "eagle-import") (part "SPU0410LR5H-QB"))
    )
    (comp (ref "U13")
      (value "TPD4EUSB30DQARDQA10")
      (footprint "eagle-import:DQA10")
      (fields
        (field (name "MANUFACTURER_PART_NUMBER") "TPD4EUSB30DQAR")
        (field (name "COPYRIGHT") "Copyright (C) 2024 Ultra Librarian. All rights reserved.")
      )
      (libsource (lib "eagle-import") (part "TPD4EUSB30DQARDQA10"))
    )
    (comp (ref "U14")
      (value "OPA344")
      (footprint "eagle-import:SOT23-5")
      (libsource (lib "eagle-import") (part "OPA344"))
    )
    (comp (ref "U15")
      (value "AP2112-3.3K")
      (footprint "eagle-import:SOT23-5")
      (libsource (lib "eagle-import") (part "VREG_SOT23-5"))
    )
    (comp (ref "U16")
      (value "W25Q16JVUXIQ_TR")
      (footprint "eagle-import:PSON50P300X200X60-9N")
      (fields (field (name "MANUFACTURER") "Winbond"))
      (libsource (lib "eagle-import") (part "W25Q16JVUXIQ_TR"))
    )
    (comp (ref "U17")
      (value "TPD1E1B04DPYRDPY2_TEX")
      (footprint "eagle-import:DPY2_TEX")
      (fields
        (field (name "MANUFACTURER_PART_NUMBER") "TPD1E1B04DPYR")
        (field (name "COPYRIGHT") "Copyright (C) 2024 Ultra Librarian. All rights reserved.")
      )
      (libsource (lib "eagle-import") (part "TPD1E1B04DPYRDPY2_TEX"))
    )
    (comp (ref "U18")
      (value "TPD1E1B04DPYRDPY2_TEX")
      (footprint "eagle-import:DPY2_TEX")
      (fields
        (field (name "MANUFACTURER_PART_NUMBER") "TPD1E1B04DPYR")
        (field (name "COPYRIGHT") "Copyright (C) 2024 Ultra Librarian. All rights reserved.")
      )
      (libsource (lib "eagle-import") (part "TPD1E1B04DPYRDPY2_TEX"))
    )
    (comp (ref "U19")
      (value "TPD1E1B04DPYRDPY2_TEX")
      (footprint "eagle-import:DPY2_TEX")
      (fields
        (field (name "MANUFACTURER_PART_NUMBER") "TPD1E1B04DPYR")
        (field (name "COPYRIGHT") "Copyright (C) 2024 Ultra Librarian. All rights reserved.")
      )
      (libsource (lib "eagle-import") (part "TPD1E1B04DPYRDPY2_TEX"))
    )
    (comp (ref "U20")
      (value "TPD1E1B04DPYRDPY2_TEX")
      (footprint "eagle-import:DPY2_TEX")
      (fields
        (field (name "MANUFACTURER_PART_NUMBER") "TPD1E1B04DPYR")
        (field (name "COPYRIGHT") "Copyright (C) 2024 Ultra Librarian. All rights reserved.")
      )
      (libsource (lib "eagle-import") (part "TPD1E1B04DPYRDPY2_TEX"))
    )
    (comp (ref "U21")
      (value "TPD1E1B04DPYRDPY2_TEX")
      (footprint "eagle-import:DPY2_TEX")
      (fields
        (field (name "MANUFACTURER_PART_NUMBER") "TPD1E1B04DPYR")
        (field (name "COPYRIGHT") "Copyright (C) 2024 Ultra Librarian. All rights reserved.")
      )
      (libsource (lib "eagle-import") (part "TPD1E1B04DPYRDPY2_TEX"))
    )
    (comp (ref "U22")
      (value "TPD1E1B04DPYRDPY2_TEX")
      (footprint "eagle-import:DPY2_TEX")
      (fields
        (field (name "MANUFACTURER_PART_NUMBER") "TPD1E1B04DPYR")
        (field (name "COPYRIGHT") "Copyright (C) 2024 Ultra Librarian. All rights reserved.")
      )
      (libsource (lib "eagle-import") (part "TPD1E1B04DPYRDPY2_TEX"))
    )
    (comp (ref "U23")
      (value "TPD1E1B04DPYRDPY2_TEX")
      (footprint "eagle-import:DPY2_TEX")
      (fields
        (field (name "MANUFACTURER_PART_NUMBER") "TPD1E1B04DPYR")
        (field (name "COPYRIGHT") "Copyright (C) 2024 Ultra Librarian. All rights reserved.")
      )
      (libsource (lib "eagle-import") (part "TPD1E1B04DPYRDPY2_TEX"))
    )
    (comp (ref "U24")
      (value "TPD1E1B04DPYRDPY2_TEX")
      (footprint "eagle-import:DPY2_TEX")
      (fields
        (field (name "MANUFACTURER_PART_NUMBER") "TPD1E1B04DPYR")
        (field (name "COPYRIGHT") "Copyright (C) 2024 Ultra Librarian. All rights reserved.")
      )
      (libsource (lib "eagle-import") (part "TPD1E1B04DPYRDPY2_TEX"))
    )
    (comp (ref "U25")
      (value "DRV2605LDGSR")
      (footprint "eagle-import:SOP50P490X110-10N")
      (fields (field (name "MANUFACTURER") "Texas Instruments"))
      (libsource (lib "eagle-import") (part "DRV2605LDGSR"))
    )
    (comp (ref "USB2.0MUX")
      (value "TS3USB30RSWR")
      (footprint "eagle-import:10-UFQFN")
      (fields (field (name "DIGI-KEY_PART_NUMBER") "296-22547-2-ND") (field (name "MF") "Texas Instruments"))
      (libsource (lib "eagle-import") (part "TS3USB30RSWR"))
    )
    (comp (ref "USB_BOOT_N")
      (value "DNP")
      (footprint "eagle-import:PAD.03X.03")
      (libsource (lib "eagle-import") (part "TEST-POINT3"))
    )
    (comp (ref "Y1")
      (value "ABM8-272-T3")
      (footprint "eagle-import:ABM8272T3")
      (fields (field (name "MOUSER_PART_NUMBER") "815-ABM8-272-T3"))
      (libsource (lib "eagle-import") (part "ABM8-272-T3"))
    )
  )
  (nets
    (net (code "1") (name "/1V8BQ") (class "Default")
      (node (ref "C20") (pin "1") (pinfunction "1_1") (pintype "passive"))
      (node (ref "U3") (pin "5") (pinfunction "VDD_5") (pintype "bidirectional"))
    )
    (net (code "2") (name "/2A3") (class "Default")
      (node (ref "U7") (pin "14") (pinfunction "2A3_14") (pintype "input"))
    )
    (net (code "3") (name "/2A4") (class "Default")
      (node (ref "U7") (pin "16") (pinfunction "2A4_16") (pintype "input"))
    )
    (net (code "4") (name "/2Y3") (class "Default")
      (node (ref "U7") (pin "4") (pinfunction "2Y3_4") (pintype "output"))
    )
    (net (code "5") (name "/2Y4") (class "Default")
      (node (ref "U7") (pin "2") (pinfunction "2Y4_2") (pintype "output"))
    )
    (net (code "6") (name "/AUDIO_MCLK") (class "Default")
      (node (ref "IC3") (pin "11") (pinfunction "MCLK_11") (pintype "input"))
      (node (ref "OSC2") (pin "3") (pinfunction "OUT_3") (pintype "output"))
    )
    (net (code "7") (name "/BUTTON_D") (class "Default")
      (node (ref "BUD") (pin "2_1") (pinfunction "2_2_1") (pintype "passive"))
      (node (ref "BUD") (pin "2_2") (pinfunction "2_2_2") (pintype "passive"))
      (node (ref "C2040") (pin "29") (pinfunction "GPIO18_29") (pintype "bidirectional"))
    )
    (net (code "8") (name "/BUTTON_S") (class "Default")
      (node (ref "BUS") (pin "2_1") (pinfunction "2_2_1") (pintype "passive"))
      (node (ref "BUS") (pin "2_2") (pinfunction "2_2_2") (pintype "passive"))
      (node (ref "C2040") (pin "27") (pinfunction "GPIO16_27") (pintype "bidirectional"))
    )
    (net (code "9") (name "/BUTTON_U") (class "Default")
      (node (ref "BUP") (pin "2_1") (pinfunction "2_2_1") (pintype "passive"))
      (node (ref "BUP") (pin "2_2") (pinfunction "2_2_2") (pintype "passive"))
      (node (ref "C2040") (pin "28") (pinfunction "GPIO17_28") (pintype "bidirectional"))
    )
    (net (code "10") (name "/CAM0_C_N") (class "Default")
      (node (ref "RPI-CM1") (pin "140") (pinfunction "CAM0_C_N_140") (pintype "passive"))
    )
    (net (code "11") (name "/CAM0_C_P") (class "Default")
      (node (ref "RPI-CM1") (pin "142") (pinfunction "CAM0_C_P_142") (pintype "passive"))
    )
    (net (code "12") (name "/CAM0_D0_N") (class "Default")
      (node (ref "RPI-CM1") (pin "128") (pinfunction "CAM0_D0_N_128") (pintype "passive"))
    )
    (net (code "13") (name "/CAM0_D0_P") (class "Default")
      (node (ref "RPI-CM1") (pin "130") (pinfunction "CAM0_D0_P_130") (pintype "passive"))
    )
    (net (code "14") (name "/CAM0_D1_N") (class "Default")
      (node (ref "RPI-CM1") (pin "134") (pinfunction "CAM0_D1_N_134") (pintype "passive"))
    )
    (net (code "15") (name "/CAM0_D1_P") (class "Default")
      (node (ref "RPI-CM1") (pin "136") (pinfunction "CAM0_D1_P_136") (pintype "passive"))
    )
    (net (code "16") (name "/CAM1_C_N") (class "Default")
      (node (ref "CAMERA") (pin "8") (pinfunction "8_8") (pintype "passive"))
      (node (ref "RPI-CM1") (pin "127") (pinfunction "CAM1_C_N_127") (pintype "passive"))
    )
    (net (code "17") (name "/CAM1_C_P") (class "Default")
      (node (ref "CAMERA") (pin "9") (pinfunction "9_9") (pintype "passive"))
      (node (ref "RPI-CM1") (pin "129") (pinfunction "CAM1_C_P_129") (pintype "passive"))
    )
    (net (code "18") (name "/CAM1_D0_N") (class "Default")
      (node (ref "CAMERA") (pin "2") (pinfunction "2_2") (pintype "passive"))
      (node (ref "RPI-CM1") (pin "115") (pinfunction "CAM1_D0_N_115") (pintype "passive"))
    )
    (net (code "19") (name "/CAM1_D0_P") (class "Default")
      (node (ref "CAMERA") (pin "3") (pinfunction "3_3") (pintype "passive"))
      (node (ref "RPI-CM1") (pin "117") (pinfunction "CAM1_D0_P_117") (pintype "passive"))
    )
    (net (code "20") (name "/CAM1_D1_N") (class "Default")
      (node (ref "CAMERA") (pin "5") (pinfunction "5_5") (pintype "passive"))
      (node (ref "RPI-CM1") (pin "121") (pinfunction "CAM1_D1_N_121") (pintype "passive"))
    )
    (net (code "21") (name "/CAM1_D1_P") (class "Default")
      (node (ref "CAMERA") (pin "6") (pinfunction "6_6") (pintype "passive"))
      (node (ref "RPI-CM1") (pin "123") (pinfunction "CAM1_D1_P_123") (pintype "passive"))
    )
    (net (code "22") (name "/CAM1_D2_N") (class "Default")
      (node (ref "CAMERA") (pin "11") (pinfunction "11_11") (pintype "passive"))
      (node (ref "RPI-CM1") (pin "133") (pinfunction "CAM1_D2_N_133") (pintype "passive"))
    )
    (net (code "23") (name "/CAM1_D2_P") (class "Default")
      (node (ref "CAMERA") (pin "12") (pinfunction "12_12") (pintype "passive"))
      (node (ref "RPI-CM1") (pin "135") (pinfunction "CAM1_D2_P_135") (pintype "passive"))
    )
    (net (code "24") (name "/CAM1_D3_N") (class "Default")
      (node (ref "CAMERA") (pin "14") (pinfunction "14_14") (pintype "passive"))
      (node (ref "RPI-CM1") (pin "139") (pinfunction "CAM1_D3_N_139") (pintype "passive"))
    )
    (net (code "25") (name "/CAM1_D3_P") (class "Default")
      (node (ref "CAMERA") (pin "15") (pinfunction "15_15") (pintype "passive"))
      (node (ref "RPI-CM1") (pin "141") (pinfunction "CAM1_D3_P_141") (pintype "passive"))
    )
    (net (code "26") (name "/CAM_GPIO") (class "Default")
      (node (ref "CAMERA") (pin "17") (pinfunction "17_17") (pintype "passive"))
      (node (ref "RPI-CM1") (pin "97") (pinfunction "CAMERA_GPIO_97") (pintype "passive"))
    )
    (net (code "27") (name "/CDD") (class "Default")
      (node (ref "C10") (pin "1") (pinfunction "1_1") (pintype "passive"))
      (node (ref "EINK_524352471") (pin "7") (pinfunction "7_7") (pintype "passive"))
    )
    (net (code "28") (name "/DSI0_C_N") (class "Default")
      (node (ref "RPI-CM1") (pin "169") (pinfunction "DSI0_C_N_169") (pintype "passive"))
    )
    (net (code "29") (name "/DSI0_C_P") (class "Default")
      (node (ref "RPI-CM1") (pin "171") (pinfunction "DSI0_C_P_171") (pintype "passive"))
    )
    (net (code "30") (name "/DSI0_D0_N") (class "Default")
      (node (ref "RPI-CM1") (pin "157") (pinfunction "DSI0_D0_N_157") (pintype "passive"))
    )
    (net (code "31") (name "/DSI0_D0_P") (class "Default")
      (node (ref "RPI-CM1") (pin "159") (pinfunction "DSI0_D0_P_159") (pintype "passive"))
    )
    (net (code "32") (name "/DSI0_D1_N") (class "Default")
      (node (ref "RPI-CM1") (pin "163") (pinfunction "DSI0_D1_N_163") (pintype "passive"))
    )
    (net (code "33") (name "/DSI0_D1_P") (class "Default")
      (node (ref "RPI-CM1") (pin "165") (pinfunction "DSI0_D1_P_165") (pintype "passive"))
    )
    (net (code "34") (name "/DSI1_C_N") (class "Default")
      (node (ref "RPI-CM1") (pin "187") (pinfunction "DSI1_C_N_187") (pintype "passive"))
    )
    (net (code "35") (name "/DSI1_C_P") (class "Default")
      (node (ref "RPI-CM1") (pin "189") (pinfunction "DSI1_C_P_189") (pintype "passive"))
    )
    (net (code "36") (name "/DSI1_D0_N") (class "Default")
      (node (ref "RPI-CM1") (pin "175") (pinfunction "DSI1_D0_N_175") (pintype "passive"))
    )
    (net (code "37") (name "/DSI1_D0_P") (class "Default")
      (node (ref "RPI-CM1") (pin "177") (pinfunction "DSI1_D0_P_177") (pintype "passive"))
    )
    (net (code "38") (name "/DSI1_D1_N") (class "Default")
      (node (ref "RPI-CM1") (pin "181") (pinfunction "DSI1_D1_N_181") (pintype "passive"))
    )
    (net (code "39") (name "/DSI1_D1_P") (class "Default")
      (node (ref "RPI-CM1") (pin "183") (pinfunction "DSI1_D1_P_183") (pintype "passive"))
    )
    (net (code "40") (name "/DSI1_D2_N") (class "Default")
      (node (ref "RPI-CM1") (pin "193") (pinfunction "DSI1_D2_N_193") (pintype "passive"))
    )
    (net (code "41") (name "/DSI1_D2_P") (class "Default")
      (node (ref "RPI-CM1") (pin "195") (pinfunction "DSI1_D2_P_195") (pintype "passive"))
    )
    (net (code "42") (name "/DSI1_D3_N") (class "Default")
      (node (ref "RPI-CM1") (pin "194") (pinfunction "DSI1_D3_N_194") (pintype "passive"))
    )
    (net (code "43") (name "/DSI1_D3_P") (class "Default")
      (node (ref "RPI-CM1") (pin "196") (pinfunction "DSI1_D3_P_196") (pintype "passive"))
    )
    (net (code "44") (name "/EINK_BUSY") (class "Default")
      (node (ref "C2040") (pin "13") (pinfunction "GPIO10_13") (pintype "bidirectional"))
      (node (ref "EINK_524352471") (pin "16") (pinfunction "16_16") (pintype "passive"))
      (node (ref "RPIBOOT9") (pin "P$1") (pinfunction "1_P$1") (pintype "bidirectional"))
      (node (ref "U18") (pin "2") (pinfunction "I/O_2") (pintype "passive"))
      (node (ref "U7") (pin "1") (pinfunction "1A1_1") (pintype "input"))
    )
    (net (code "45") (name "/EINK_CS") (class "Default")
      (node (ref "C2040") (pin "16") (pinfunction "GPIO13_16") (pintype "bidirectional"))
      (node (ref "EINK_524352471") (pin "13") (pinfunction "13_13") (pintype "passive"))
      (node (ref "GND41") (pin "P$1") (pinfunction "1_P$1") (pintype "bidirectional"))
      (node (ref "U20") (pin "2") (pinfunction "I/O_2") (pintype "passive"))
      (node (ref "U7") (pin "11") (pinfunction "1Y4_11") (pintype "output"))
    )
    (net (code "46") (name "/EINK_D{slash}C") (class "Default")
      (node (ref "C2040") (pin "15") (pinfunction "GPIO12_15") (pintype "bidirectional"))
      (node (ref "EINK_524352471") (pin "14") (pinfunction "14_14") (pintype "passive"))
      (node (ref "RPIBOOT10") (pin "P$1") (pinfunction "1_P$1") (pintype "bidirectional"))
      (node (ref "U19") (pin "2") (pinfunction "I/O_2") (pintype "passive"))
      (node (ref "U7") (pin "13") (pinfunction "1Y3_13") (pintype "output"))
    )
    (net (code "47") (name "/EINK_RESET") (class "Default")
      (node (ref "C2040") (pin "14") (pinfunction "GPIO11_14") (pintype "bidirectional"))
      (node (ref "EINK_524352471") (pin "15") (pinfunction "15_15") (pintype "passive"))
      (node (ref "GND40") (pin "P$1") (pinfunction "1_P$1") (pintype "bidirectional"))
      (node (ref "U17") (pin "2") (pinfunction "I/O_2") (pintype "passive"))
      (node (ref "U7") (pin "15") (pinfunction "1Y2_15") (pintype "output"))
    )
    (net (code "48") (name "/FAN_PWM") (class "Default")
      (node (ref "J3") (pin "1") (pinfunction "1_1") (pintype "passive"))
      (node (ref "U9") (pin "5") (pinfunction "PWM_5") (pintype "output"))
    )
    (net (code "49") (name "/GDR") (class "Default")
      (node (ref "EINK_524352471") (pin "23") (pinfunction "23_23") (pintype "passive"))
      (node (ref "Q1") (pin "1") (pinfunction "G_1") (pintype "bidirectional"))
      (node (ref "R11") (pin "2") (pinfunction "2_2") (pintype "passive"))
    )
    (net (code "50") (name "/GND_2") (class "Default")
      (node (ref "U13") (pin "3") (pinfunction "GND_2_3") (pintype "power_in"))
    )
    (net (code "51") (name "/HDMI0_CEC") (class "Default")
      (node (ref "RPI-CM1") (pin "151") (pinfunction "HDMI0_CEC_151") (pintype "passive"))
    )
    (net (code "52") (name "/HDMI0_CLK_N") (class "Default")
      (node (ref "RPI-CM1") (pin "190") (pinfunction "HDMI0_CLK_N_190") (pintype "passive"))
    )
    (net (code "53") (name "/HDMI0_CLK_P") (class "Default")
      (node (ref "RPI-CM1") (pin "188") (pinfunction "HDMI0_CLK_P_188") (pintype "passive"))
    )
    (net (code "54") (name "/HDMI0_HOTPLUG") (class "Default")
      (node (ref "RPI-CM1") (pin "153") (pinfunction "HDMI0_HOTPLUG_153") (pintype "passive"))
    )
    (net (code "55") (name "/HDMI0_SCL") (class "Default")
      (node (ref "RPI-CM1") (pin "200") (pinfunction "HDMI0_SCL_200") (pintype "passive"))
    )
    (net (code "56") (name "/HDMI0_SDA") (class "Default")
      (node (ref "RPI-CM1") (pin "199") (pinfunction "HDMI0_SDA_199") (pintype "passive"))
    )
    (net (code "57") (name "/HDMI0_TX0_N") (class "Default")
      (node (ref "RPI-CM1") (pin "184") (pinfunction "HDMI0_TX0_N_184") (pintype "passive"))
    )
    (net (code "58") (name "/HDMI0_TX0_P") (class "Default")
      (node (ref "RPI-CM1") (pin "182") (pinfunction "HDMI0_TX0_P_182") (pintype "passive"))
    )
    (net (code "59") (name "/HDMI0_TX1_N") (class "Default")
      (node (ref "RPI-CM1") (pin "178") (pinfunction "HDMI0_TX1_N_178") (pintype "passive"))
    )
    (net (code "60") (name "/HDMI0_TX1_P") (class "Default")
      (node (ref "RPI-CM1") (pin "176") (pinfunction "HDMI0_TX1_P_176") (pintype "passive"))
    )
    (net (code "61") (name "/HDMI0_TX2_N") (class "Default")
      (node (ref "RPI-CM1") (pin "172") (pinfunction "HDMI0_TX2_N_172") (pintype "passive"))
    )
    (net (code "62") (name "/HDMI0_TX2_P") (class "Default")
      (node (ref "RPI-CM1") (pin "170") (pinfunction "HDMI0_TX2_P_170") (pintype "passive"))
    )
    (net (code "63") (name "/HDMI1_CEC") (class "Default")
      (node (ref "RPI-CM1") (pin "149") (pinfunction "HDMI1_CEC_149") (pintype "passive"))
    )
    (net (code "64") (name "/HDMI1_CLK_N") (class "Default")
      (node (ref "RPI-CM1") (pin "166") (pinfunction "HDMI1_CLK_N_166") (pintype "passive"))
    )
    (net (code "65") (name "/HDMI1_CLK_P") (class "Default")
      (node (ref "RPI-CM1") (pin "164") (pinfunction "HDMI1_CLK_P_164") (pintype "passive"))
    )
    (net (code "66") (name "/HDMI1_HOTPLUG") (class "Default")
      (node (ref "RPI-CM1") (pin "143") (pinfunction "HDMI1_HOTPLUG_143") (pintype "passive"))
    )
    (net (code "67") (name "/HDMI1_SCL") (class "Default")
      (node (ref "RPI-CM1") (pin "147") (pinfunction "HDMI1_SCL_147") (pintype "passive"))
    )
    (net (code "68") (name "/HDMI1_SDA") (class "Default")
      (node (ref "RPI-CM1") (pin "145") (pinfunction "HDMI1_SDA_145") (pintype "passive"))
    )
    (net (code "69") (name "/HDMI1_TX0_N") (class "Default")
      (node (ref "RPI-CM1") (pin "160") (pinfunction "HDMI1_TX0_N_160") (pintype "passive"))
    )
    (net (code "70") (name "/HDMI1_TX0_P") (class "Default")
      (node (ref "RPI-CM1") (pin "158") (pinfunction "HDMI1_TX0_P_158") (pintype "passive"))
    )
    (net (code "71") (name "/HDMI1_TX1_N") (class "Default")
      (node (ref "RPI-CM1") (pin "154") (pinfunction "HDMI1_TX1_N_154") (pintype "passive"))
    )
    (net (code "72") (name "/HDMI1_TX1_P") (class "Default")
      (node (ref "RPI-CM1") (pin "152") (pinfunction "HDMI1_TX1_P_152") (pintype "passive"))
    )
    (net (code "73") (name "/HDMI1_TX2_N") (class "Default")
      (node (ref "RPI-CM1") (pin "148") (pinfunction "HDMI1_TX2_N_148") (pintype "passive"))
    )
    (net (code "74") (name "/HDMI1_TX2_P") (class "Default")
      (node (ref "RPI-CM1") (pin "146") (pinfunction "HDMI1_TX2_P_146") (pintype "passive"))
    )
    (net (code "75") (name "/I2S_BCLK") (class "Default")
      (node (ref "IC3") (pin "12") (pinfunction "BCLK_12") (pintype "bidirectional"))
      (node (ref "RPI-CM1") (pin "49") (pinfunction "GPIO18_49") (pintype "passive"))
    )
    (net (code "76") (name "/I2S_DIN") (class "Default")
      (node (ref "IC3") (pin "16") (pinfunction "ADCDAT_16") (pintype "input"))
      (node (ref "RPI-CM1") (pin "27") (pinfunction "GPIO20_27") (pintype "passive"))
    )
    (net (code "77") (name "/I2S_DOUT") (class "Default")
      (node (ref "IC3") (pin "14") (pinfunction "DACDAT_14") (pintype "bidirectional"))
      (node (ref "RPI-CM1") (pin "25") (pinfunction "GPIO21_25") (pintype "passive"))
    )
    (net (code "78") (name "/I2S_LRCLK") (class "Default")
      (node (ref "IC3") (pin "13") (pinfunction "DACLRC_13") (pintype "bidirectional"))
      (node (ref "IC3") (pin "15") (pinfunction "ADCLRC/GPIO1_15") (pintype "bidirectional"))
      (node (ref "RPI-CM1") (pin "26") (pinfunction "GPIO19_26") (pintype "passive"))
    )
    (net (code "79") (name "/LBO") (class "Default")
      (node (ref "T1") (pin "B") (pinfunction "B_B") (pintype "passive"))
      (node (ref "U1") (pin "12") (pinfunction "LBO_12") (pintype "output"))
    )
    (net (code "80") (name "/LEFT_N") (class "Default")
      (node (ref "C64") (pin "1") (pinfunction "1_1") (pintype "passive"))
      (node (ref "FB3") (pin "2") (pinfunction "2_2") (pintype "passive"))
      (node (ref "LS1") (pin "N") (pinfunction "N_N") (pintype "passive"))
    )
    (net (code "81") (name "/LEFT_P") (class "Default")
      (node (ref "C63") (pin "1") (pinfunction "1_1") (pintype "passive"))
      (node (ref "FB2") (pin "2") (pinfunction "2_2") (pintype "passive"))
      (node (ref "LS1") (pin "P") (pinfunction "P_P") (pintype "passive"))
    )
    (net (code "82") (name "/MICBIAS") (class "Default")
      (node (ref "C46") (pin "1") (pinfunction "1_1") (pintype "passive"))
      (node (ref "C48") (pin "1") (pinfunction "1_1") (pintype "passive"))
      (node (ref "IC3") (pin "1") (pinfunction "MICBIAS_1") (pintype "output"))
    )
    (net (code "83") (name "/NC") (class "Default")
      (node (ref "EINK_524352471") (pin "24") (pinfunction "24_24") (pintype "passive"))
    )
    (net (code "84") (name "/N_RPIBOOT") (class "Default")
      (node (ref "RPI-CM1") (pin "93") (pinfunction "~{RPIBOOT}_93") (pintype "passive"))
      (node (ref "RPIBOOT") (pin "P$1") (pinfunction "1_P$1") (pintype "bidirectional"))
    )
    (net (code "85") (name "/PCIE_CLK_N") (class "Default")
      (node (ref "M.2KEYM(NGFF)") (pin "53") (pinfunction "P53_53") (pintype "passive"))
      (node (ref "RPI-CM1") (pin "112") (pinfunction "PCIE_CLK_N_112") (pintype "passive"))
    )
    (net (code "86") (name "/PCIE_CLK_P") (class "Default")
      (node (ref "M.2KEYM(NGFF)") (pin "55") (pinfunction "P55_55") (pintype "passive"))
      (node (ref "RPI-CM1") (pin "110") (pinfunction "PCIE_CLK_P_110") (pintype "passive"))
    )
    (net (code "87") (name "/PCIE_CLK_~{REQ}") (class "Default")
      (node (ref "M.2KEYM(NGFF)") (pin "52") (pinfunction "P52_52") (pintype "passive"))
      (node (ref "RPI-CM1") (pin "102") (pinfunction "PCIE_CLK_~{REQ}_102") (pintype "passive"))
    )
    (net (code "88") (name "/PCIE_RX_N") (class "Default")
      (node (ref "M.2KEYM(NGFF)") (pin "41") (pinfunction "P41_41") (pintype "passive"))
      (node (ref "RPI-CM1") (pin "118") (pinfunction "PCIE_RX_N_118") (pintype "passive"))
    )
    (net (code "89") (name "/PCIE_RX_P") (class "Default")
      (node (ref "M.2KEYM(NGFF)") (pin "43") (pinfunction "P43_43") (pintype "passive"))
      (node (ref "RPI-CM1") (pin "116") (pinfunction "PCIE_RX_P_116") (pintype "passive"))
    )
    (net (code "90") (name "/PCIE_TX_N") (class "Default")
      (node (ref "M.2KEYM(NGFF)") (pin "47") (pinfunction "P47_47") (pintype "passive"))
      (node (ref "RPI-CM1") (pin "124") (pinfunction "PCIE_TX_N_124") (pintype "passive"))
    )
    (net (code "91") (name "/PCIE_TX_P") (class "Default")
      (node (ref "M.2KEYM(NGFF)") (pin "49") (pinfunction "P49_49") (pintype "passive"))
      (node (ref "RPI-CM1") (pin "122") (pinfunction "PCIE_TX_P_122") (pintype "passive"))
    )
    (net (code "92") (name "/PCIE_~{RST}") (class "Default")
      (node (ref "M.2KEYM(NGFF)") (pin "50") (pinfunction "P50_50") (pintype "passive"))
      (node (ref "RPI-CM1") (pin "109") (pinfunction "PCIE_~{RST}_109") (pintype "passive"))
    )
    (net (code "93") (name "/PI_1V8") (class "Default")
      (node (ref "RPI-CM1") (pin "88") (pinfunction "CM4_1.8V(OUTPUT)_88") (pintype "passive"))
      (node (ref "RPI-CM1") (pin "90") (pinfunction "CM4_1.8V(OUTPUT)_90") (pintype "passive"))
    )
    (net (code "94") (name "/RESE") (class "Default")
      (node (ref "EINK_524352471") (pin "22") (pinfunction "22_22") (pintype "passive"))
      (node (ref "Q1") (pin "2") (pinfunction "S_2") (pintype "bidirectional"))
      (node (ref "R9") (pin "2") (pinfunction "2_2") (pintype "passive"))
    )
    (net (code "95") (name "/RESERVED@104") (class "Default")
      (node (ref "RPI-CM1") (pin "104") (pinfunction "RESERVED_104") (pintype "passive"))
    )
    (net (code "96") (name "/RESERVED@106") (class "Default")
      (node (ref "RPI-CM1") (pin "106") (pinfunction "RESERVED_106") (pintype "passive"))
    )
    (net (code "97") (name "/RINPUT1") (class "Default")
      (node (ref "C27") (pin "2") (pinfunction "2_2") (pintype "passive"))
      (node (ref "IC3") (pin "5") (pinfunction "RINPUT1_5") (pintype "input"))
      (node (ref "R39") (pin "1") (pinfunction "1_1") (pintype "passive"))
      (node (ref "U14") (pin "1") (pinfunction "OUT_1") (pintype "output"))
    )
    (net (code "98") (name "/SAM_BOOT") (class "Default")
      (node (ref "Q4") (pin "1") (pinfunction "G_1") (pintype "passive"))
      (node (ref "RPI-CM1") (pin "29") (pinfunction "GPIO16_29") (pintype "passive"))
    )
    (net (code "99") (name "/SAM_EINK_PWR") (class "Default")
      (node (ref "C2040") (pin "12") (pinfunction "GPIO9_12") (pintype "bidirectional"))
      (node (ref "U5") (pin "2") (pinfunction "IN_A_2") (pintype "input"))
    )
    (net (code "100") (name "/SAM_EINK_SWITCH") (class "Default")
      (node (ref "C2040") (pin "34") (pinfunction "GPIO22_34") (pintype "bidirectional"))
      (node (ref "U7") (pin "18") (pinfunction "2OE_N_18") (pintype "input"))
      (node (ref "U7") (pin "20") (pinfunction "1OE_N_20") (pintype "input"))
    )
    (net (code "101") (name "/SAM_GPIO3") (class "Default")
      (node (ref "C2040") (pin "5") (pinfunction "GPIO3_5") (pintype "bidirectional"))
    )
    (net (code "102") (name "/SAM_GPIO4") (class "Default")
      (node (ref "C2040") (pin "6") (pinfunction "GPIO4_6") (pintype "bidirectional"))
    )
    (net (code "103") (name "/SAM_GPIO5") (class "Default")
      (node (ref "C2040") (pin "7") (pinfunction "GPIO5_7") (pintype "bidirectional"))
    )
    (net (code "104") (name "/SAM_GPIO6") (class "Default")
      (node (ref "C2040") (pin "8") (pinfunction "GPIO6_8") (pintype "bidirectional"))
    )
    (net (code "105") (name "/SAM_GPIO7") (class "Default")
      (node (ref "C2040") (pin "9") (pinfunction "GPIO7_9") (pintype "bidirectional"))
    )
    (net (code "106") (name "/SAM_GPIO8") (class "Default")
      (node (ref "C2040") (pin "11") (pinfunction "GPIO8_11") (pintype "bidirectional"))
    )
    (net (code "107") (name "/SAM_GPIO23") (class "Default")
      (node (ref "C2040") (pin "35") (pinfunction "GPIO23_35") (pintype "bidirectional"))
    )
    (net (code "108") (name "/SAM_GPIO26{slash}ADC0") (class "Default")
      (node (ref "C2040") (pin "38") (pinfunction "GPIO26/ADC0_38") (pintype "bidirectional"))
    )
    (net (code "109") (name "/SAM_GPIO27{slash}ADC1") (class "Default")
      (node (ref "C2040") (pin "39") (pinfunction "GPIO27/ADC1_39") (pintype "bidirectional"))
    )
    (net (code "110") (name "/SAM_GPIO28{slash}ADC2") (class "Default")
      (node (ref "C2040") (pin "40") (pinfunction "GPIO28/ADC2_40") (pintype "bidirectional"))
    )
    (net (code "111") (name "/SAM_GPIO29{slash}ADC3") (class "Default")
      (node (ref "C2040") (pin "41") (pinfunction "GPIO29/ADC3_41") (pintype "bidirectional"))
    )
    (net (code "112") (name "/SAM_INTERUPT") (class "Default")
      (node (ref "C2040") (pin "4") (pinfunction "GPIO2_4") (pintype "bidirectional"))
      (node (ref "RPI-CM1") (pin "46") (pinfunction "GPIO22_46") (pintype "passive"))
      (node (ref "RPIBOOT12") (pin "P$1") (pinfunction "1_P$1") (pintype "bidirectional"))
    )
    (net (code "113") (name "/SAM_QSPI_SCLK") (class "Default")
      (node (ref "C2040") (pin "52") (pinfunction "QSPI_SCLK_52") (pintype "bidirectional"))
      (node (ref "U16") (pin "6") (pinfunction "CLK_6") (pintype "input"))
    )
    (net (code "114") (name "/SAM_QSPI_SD0") (class "Default")
      (node (ref "C2040") (pin "53") (pinfunction "QSPI_SD0_53") (pintype "bidirectional"))
      (node (ref "U16") (pin "5") (pinfunction "IO0_5") (pintype "bidirectional"))
    )
    (net (code "115") (name "/SAM_QSPI_SD1") (class "Default")
      (node (ref "C2040") (pin "55") (pinfunction "QSPI_SD1_55") (pintype "bidirectional"))
      (node (ref "U16") (pin "2") (pinfunction "IO1_2") (pintype "bidirectional"))
    )
    (net (code "116") (name "/SAM_QSPI_SD2") (class "Default")
      (node (ref "C2040") (pin "54") (pinfunction "QSPI_SD2_54") (pintype "bidirectional"))
      (node (ref "U16") (pin "3") (pinfunction "IO2_3") (pintype "bidirectional"))
    )
    (net (code "117") (name "/SAM_QSPI_SD3") (class "Default")
      (node (ref "C2040") (pin "51") (pinfunction "QSPI_SD3_51") (pintype "bidirectional"))
      (node (ref "U16") (pin "7") (pinfunction "IO3_7") (pintype "bidirectional"))
    )
    (net (code "118") (name "/SAM_RUN") (class "Default")
      (node (ref "C2040") (pin "26") (pinfunction "RUN_26") (pintype "input"))
    )
    (net (code "119") (name "/SAM_SWCLK") (class "Default")
      (node (ref "C2040") (pin "24") (pinfunction "SWCLK_24") (pintype "input"))
    )
    (net (code "120") (name "/SAM_SWD") (class "Default")
      (node (ref "C2040") (pin "25") (pinfunction "SWD_25") (pintype "bidirectional"))
    )
    (net (code "121") (name "/SAM_USB_DM") (class "Default")
      (node (ref "C2040") (pin "46") (pinfunction "USB_DM_46") (pintype "bidirectional"))
      (node (ref "R32") (pin "2") (pinfunction "2_2") (pintype "passive"))
    )
    (net (code "122") (name "/SAM_USB_DP") (class "Default")
      (node (ref "C2040") (pin "47") (pinfunction "USB_DP_47") (pintype "bidirectional"))
      (node (ref "R31") (pin "2") (pinfunction "2_2") (pintype "passive"))
    )
    (net (code "123") (name "/SAM_USB_SWITCH") (class "Default")
      (node (ref "C2040") (pin "30") (pinfunction "GPIO19_30") (pintype "bidirectional"))
      (node (ref "R41") (pin "1") (pinfunction "1_1") (pintype "passive"))
      (node (ref "USB2.0MUX") (pin "8") (pinfunction "~{OE}_8") (pintype "input"))
    )
    (net (code "124") (name "/SAM_XIN") (class "Default")
      (node (ref "C2040") (pin "20") (pinfunction "XIN_20") (pintype "passive"))
      (node (ref "C82") (pin "1") (pinfunction "1_1") (pintype "passive"))
      (node (ref "Y1") (pin "1") (pinfunction "CRYSTAL_1_1") (pintype "bidirectional"))
    )
    (net (code "125") (name "/SAM_XOUT") (class "Default")
      (node (ref "C2040") (pin "21") (pinfunction "XOUT_21") (pintype "passive"))
      (node (ref "R35") (pin "1") (pinfunction "1_1") (pintype "passive"))
    )
    (net (code "126") (name "/SCL0") (class "Default")
      (node (ref "CAMERA") (pin "20") (pinfunction "20_20") (pintype "passive"))
      (node (ref "RPI-CM1") (pin "80") (pinfunction "SCL0_80") (pintype "passive"))
    )
    (net (code "127") (name "/SDA0") (class "Default")
      (node (ref "CAMERA") (pin "21") (pinfunction "21_21") (pintype "passive"))
      (node (ref "RPI-CM1") (pin "82") (pinfunction "SDA0_82") (pintype "passive"))
    )
    (net (code "128") (name "/SOC_EINK_BUSY") (class "Default")
      (node (ref "RPI-CM1") (pin "40") (pinfunction "GPIO9_40") (pintype "passive"))
      (node (ref "U7") (pin "17") (pinfunction "1Y1_17") (pintype "output"))
    )
    (net (code "129") (name "/SOC_EINK_CS") (class "Default")
      (node (ref "RPI-CM1") (pin "39") (pinfunction "GPIO8_39") (pintype "passive"))
      (node (ref "U7") (pin "7") (pinfunction "1A4_7") (pintype "input"))
    )
    (net (code "130") (name "/SOC_EINK_D{slash}C") (class "Default")
      (node (ref "RPI-CM1") (pin "30") (pinfunction "GPIO6_30") (pintype "passive"))
      (node (ref "U7") (pin "5") (pinfunction "1A3_5") (pintype "input"))
    )
    (net (code "131") (name "/SOC_EINK_RESET") (class "Default")
      (node (ref "RPI-CM1") (pin "28") (pinfunction "GPIO13_28") (pintype "passive"))
      (node (ref "U7") (pin "3") (pinfunction "1A2_3") (pintype "input"))
    )
    (net (code "132") (name "/SOC_SPI_CLK") (class "Default")
      (node (ref "RPI-CM1") (pin "38") (pinfunction "GPIO11_38") (pintype "passive"))
      (node (ref "U7") (pin "10") (pinfunction "2A1_10") (pintype "input"))
    )
    (net (code "133") (name "/SOC_SPI_MOSI") (class "Default")
      (node (ref "RPI-CM1") (pin "44") (pinfunction "GPIO10_44") (pintype "passive"))
      (node (ref "U7") (pin "12") (pinfunction "2A2_12") (pintype "input"))
    )
    (net (code "134") (name "/SPI_CLK") (class "Default")
      (node (ref "C2040") (pin "17") (pinfunction "GPIO14_17") (pintype "bidirectional"))
      (node (ref "EINK_524352471") (pin "12") (pinfunction "12_12") (pintype "passive"))
      (node (ref "RPIBOOT11") (pin "P$1") (pinfunction "1_P$1") (pintype "bidirectional"))
      (node (ref "U21") (pin "2") (pinfunction "I/O_2") (pintype "passive"))
      (node (ref "U7") (pin "8") (pinfunction "2Y1_8") (pintype "output"))
    )
    (net (code "135") (name "/SPI_MOSI") (class "Default")
      (node (ref "C2040") (pin "18") (pinfunction "GPIO15_18") (pintype "bidirectional"))
      (node (ref "EINK_524352471") (pin "11") (pinfunction "11_11") (pintype "passive"))
      (node (ref "GND42") (pin "P$1") (pinfunction "1_P$1") (pintype "bidirectional"))
      (node (ref "U22") (pin "2") (pinfunction "I/O_2") (pintype "passive"))
      (node (ref "U7") (pin "6") (pinfunction "2Y2_6") (pintype "output"))
    )
    (net (code "136") (name "/SYS_PI_ON") (class "Default")
      (node (ref "C2040") (pin "32") (pinfunction "GPIO21_32") (pintype "bidirectional"))
      (node (ref "Q3") (pin "1") (pinfunction "G_1") (pintype "passive"))
    )
    (net (code "137") (name "/TACH") (class "Default")
      (node (ref "J3") (pin "2") (pinfunction "2_2") (pintype "passive"))
      (node (ref "R30") (pin "1") (pinfunction "1_1") (pintype "passive"))
      (node (ref "U9") (pin "6") (pinfunction "TACH_6") (pintype "input"))
    )
    (net (code "138") (name "/TSCL") (class "Default")
      (node (ref "EINK_524352471") (pin "19") (pinfunction "19_19") (pintype "passive"))
      (node (ref "U23") (pin "2") (pinfunction "I/O_2") (pintype "passive"))
    )
    (net (code "139") (name "/TSDA") (class "Default")
      (node (ref "EINK_524352471") (pin "18") (pinfunction "18_18") (pintype "passive"))
      (node (ref "U24") (pin "2") (pinfunction "I/O_2") (pintype "passive"))
    )
    (net (code "140") (name "/U25_OUT+") (class "Default")
      (node (ref "H2") (pin "1") (pinfunction "1_1") (pintype "passive"))
      (node (ref "H2") (pin "2") (pinfunction "2_2") (pintype "passive"))
      (node (ref "U25") (pin "7") (pinfunction "OUT+_7") (pintype "output"))
    )
    (net (code "141") (name "/U25_OUT-") (class "Default")
      (node (ref "H2") (pin "3") (pinfunction "3_3") (pintype "passive"))
      (node (ref "H2") (pin "4") (pinfunction "4_4") (pintype "passive"))
      (node (ref "U25") (pin "9") (pinfunction "OUT-_9") (pintype "output"))
    )
    (net (code "142") (name "/UART_RXD0") (class "Default")
      (node (ref "J5") (pin "2") (pinfunction "2_2") (pintype "passive"))
      (node (ref "RPI-CM1") (pin "51") (pinfunction "GPIO15_51") (pintype "passive"))
    )
    (net (code "143") (name "/UART_TXD0") (class "Default")
      (node (ref "J5") (pin "1") (pinfunction "1_1") (pintype "passive"))
      (node (ref "RPI-CM1") (pin "55") (pinfunction "GPIO14_55") (pintype "passive"))
    )
    (net (code "144") (name "/USB_OTG_ID") (class "Default")
      (node (ref "RPI-CM1") (pin "101") (pinfunction "USB_OTG_ID_101") (pintype "passive"))
    )
    (net (code "145") (name "/VCOM") (class "Default")
      (node (ref "C15") (pin "1") (pinfunction "1_1") (pintype "passive"))
      (node (ref "EINK_524352471") (pin "1") (pinfunction "1_1") (pintype "passive"))
    )
    (net (code "146") (name "/VDAC_COMP") (class "Default")
      (node (ref "RPI-CM1") (pin "111") (pinfunction "VDAC_COMP_111") (pintype "passive"))
    )
    (net (code "147") (name "/VGH") (class "Default")
      (node (ref "C8") (pin "1") (pinfunction "1_1") (pintype "passive"))
      (node (ref "EINK_524352471") (pin "20") (pinfunction "20_20") (pintype "passive"))
    )
    (net (code "148") (name "/VGL") (class "Default")
      (node (ref "C5") (pin "1") (pinfunction "1_1") (pintype "passive"))
      (node (ref "EINK_524352471") (pin "21") (pinfunction "21_21") (pintype "passive"))
    )
    (net (code "149") (name "/VMID") (class "Default")
      (node (ref "C45") (pin "1") (pinfunction "1_1") (pintype "passive"))
      (node (ref "C47") (pin "1") (pinfunction "1_1") (pintype "passive"))
      (node (ref "IC3") (pin "27") (pinfunction "VMID_27") (pintype "input"))
    )
    (net (code "150") (name "/VPP") (class "Default")
      (node (ref "C11") (pin "1") (pinfunction "1_1") (pintype "passive"))
      (node (ref "EINK_524352471") (pin "6") (pinfunction "6_6") (pintype "passive"))
    )
    (net (code "151") (name "/VSH") (class "Default")
      (node (ref "C12") (pin "1") (pinfunction "1_1") (pintype "passive"))
      (node (ref "EINK_524352471") (pin "5") (pinfunction "5_5") (pintype "passive"))
    )
    (net (code "152") (name "/VSL") (class "Default")
      (node (ref "C13") (pin "1") (pinfunction "1_1") (pintype "passive"))
      (node (ref "EINK_524352471") (pin "3") (pinfunction "3_3") (pintype "passive"))
    )
    (net (code "153") (name "/~{CE}") (class "Default")
      (node (ref "R24") (pin "1") (pinfunction "1_1") (pintype "passive"))
      (node (ref "U4") (pin "4") (pinfunction "~{CE}_4") (pintype "bidirectional"))
    )
    (net (code "154") (name "3.3V") (class "Default")
      (node (ref "C28") (pin "1") (pinfunction "1_1") (pintype "passive"))
      (node (ref "C36") (pin "2") (pinfunction "2_2") (pintype "passive"))
      (node (ref "C49") (pin "1") (pinfunction "1_1") (pintype "passive"))
      (node (ref "CAMERA") (pin "22") (pinfunction "22_22") (pintype "passive"))
      (node (ref "D1") (pin "A") (pinfunction "A_A") (pintype "passive"))
      (node (ref "IC1") (pin "5") (pinfunction "VDD_5") (pintype "power_in"))
      (node (ref "IC1") (pin "6") (pinfunction "VDDIO_6") (pintype "power_in"))
      (node (ref "IC3") (pin "10") (pinfunction "DBVDD_10") (pintype "power_in"))
      (node (ref "IC3") (pin "8") (pinfunction "DCVDD_8") (pintype "power_in"))
      (node (ref "OSC2") (pin "1") (pinfunction "INH_1") (pintype "bidirectional"))
      (node (ref "OSC2") (pin "4") (pinfunction "VCC_4") (pintype "power_in"))
      (node (ref "R15") (pin "2") (pinfunction "2_2") (pintype "passive"))
      (node (ref "R18") (pin "2") (pinfunction "2_2") (pintype "passive"))
      (node (ref "R30") (pin "2") (pinfunction "2_2") (pintype "passive"))
      (node (ref "R33") (pin "2") (pinfunction "2_2") (pintype "passive"))
      (node (ref "RPI-CM1") (pin "84") (pinfunction "CM4_3.3V(OUTPUT)_84") (pintype "passive"))
      (node (ref "RPI-CM1") (pin "86") (pinfunction "CM4_3.3V(OUTPUT)_86") (pintype "passive"))
      (node (ref "RPIBOOT2") (pin "P$1") (pinfunction "1_P$1") (pintype "bidirectional"))
      (node (ref "SJ6") (pin "1") (pinfunction "1_1") (pintype "passive"))
      (node (ref "U2") (pin "5") (pinfunction "VCC_5") (pintype "power_in"))
      (node (ref "U6") (pin "5") (pinfunction "VDDIO_5") (pintype "power_in"))
      (node (ref "U6") (pin "8") (pinfunction "VDD_8") (pintype "power_in"))
      (node (ref "U9") (pin "3") (pinfunction "VDD_3") (pintype "power_in"))
    )
    (net (code "155") (name "3V3_EINK") (class "Default")
      (node (ref "C17") (pin "1") (pinfunction "1_1") (pintype "passive"))
      (node (ref "C9") (pin "1") (pinfunction "1_1") (pintype "passive"))
      (node (ref "EINK_524352471") (pin "10") (pinfunction "10_10") (pintype "passive"))
      (node (ref "EINK_524352471") (pin "9") (pinfunction "9_9") (pintype "passive"))
      (node (ref "L3") (pin "1") (pinfunction "1_1") (pintype "passive"))
      (node (ref "Q2") (pin "3") (pinfunction "D_3") (pintype "passive"))
    )
    (net (code "156") (name "5.0V") (class "Default")
      (node (ref "C2") (pin "1") (pinfunction "1_1") (pintype "passive"))
      (node (ref "C25") (pin "1") (pinfunction "1_1") (pintype "passive"))
      (node (ref "C42") (pin "1") (pinfunction "1_1") (pintype "passive"))
      (node (ref "C59") (pin "1") (pinfunction "1_1") (pintype "passive"))
      (node (ref "C6") (pin "1") (pinfunction "1_1") (pintype "passive"))
      (node (ref "C60") (pin "1") (pinfunction "1_1") (pintype "passive"))
      (node (ref "C61") (pin "1") (pinfunction "1_1") (pintype "passive"))
      (node (ref "C65") (pin "1") (pinfunction "1_1") (pintype "passive"))
      (node (ref "C66") (pin "1") (pinfunction "1_1") (pintype "passive"))
      (node (ref "IC3") (pin "21") (pinfunction "SPKVDD2_21") (pintype "power_in"))
      (node (ref "IC3") (pin "26") (pinfunction "SPKVDD1_26") (pintype "power_in"))
      (node (ref "J3") (pin "3") (pinfunction "3_3") (pintype "passive"))
      (node (ref "R3") (pin "2") (pinfunction "2_2") (pintype "passive"))
      (node (ref "R5") (pin "1") (pinfunction "1_1") (pintype "passive"))
      (node (ref "RPI-CM1") (pin "77") (pinfunction "+5V(INPUT)_77") (pintype "passive"))
      (node (ref "RPI-CM1") (pin "79") (pinfunction "+5V(INPUT)_79") (pintype "passive"))
      (node (ref "RPI-CM1") (pin "81") (pinfunction "+5V(INPUT)_81") (pintype "passive"))
      (node (ref "RPI-CM1") (pin "83") (pinfunction "+5V(INPUT)_83") (pintype "passive"))
      (node (ref "RPI-CM1") (pin "85") (pinfunction "+5V(INPUT)_85") (pintype "passive"))
      (node (ref "RPI-CM1") (pin "87") (pinfunction "+5V(INPUT)_87") (pintype "passive"))
      (node (ref "RPIBOOT1") (pin "P$1") (pinfunction "1_P$1") (pintype "bidirectional"))
      (node (ref "U1") (pin "1") (pinfunction "VOUT_1") (pintype "power_in"))
      (node (ref "U1") (pin "15") (pinfunction "VOUT_15") (pintype "power_in"))
      (node (ref "U1") (pin "16") (pinfunction "VOUT_16") (pintype "power_in"))
      (node (ref "U10") (pin "1") (pinfunction "IN_1") (pintype "power_in"))
      (node (ref "U10") (pin "3") (pinfunction "EN_3") (pintype "input"))
    )
    (net (code "157") (name "AGND") (class "Default")
      (node (ref "C67") (pin "2") (pinfunction "2_2") (pintype "passive"))
      (node (ref "C68") (pin "2") (pinfunction "2_2") (pintype "passive"))
      (node (ref "FB5") (pin "2") (pinfunction "2_2") (pintype "passive"))
      (node (ref "IC3") (pin "28") (pinfunction "AGND_28") (pintype "power_in"))
      (node (ref "IC3") (pin "33") (pinfunction "AGND_33") (pintype "power_in"))
    )
    (net (code "158") (name "AVDD") (class "Default")
      (node (ref "C50") (pin "1") (pinfunction "1_1") (pintype "passive"))
      (node (ref "C58") (pin "1") (pinfunction "1_1") (pintype "passive"))
      (node (ref "C67") (pin "1") (pinfunction "1_1") (pintype "passive"))
      (node (ref "C68") (pin "1") (pinfunction "1_1") (pintype "passive"))
      (node (ref "FB1") (pin "2") (pinfunction "2_2") (pintype "passive"))
      (node (ref "IC3") (pin "32") (pinfunction "AVDD_32") (pintype "power_in"))
      (node (ref "R27") (pin "2") (pinfunction "2_2") (pintype "passive"))
      (node (ref "U12") (pin "4") (pinfunction "VDD_4") (pintype "power_in"))
      (node (ref "U14") (pin "5") (pinfunction "P$V+_5") (pintype "bidirectional"))
    )
    (net (code "159") (name "BATTERY_IN") (class "Default")
      (node (ref "C19") (pin "1") (pinfunction "1_1") (pintype "passive"))
      (node (ref "J1") (pin "3") (pinfunction "3_3") (pintype "passive"))
      (node (ref "R12") (pin "2") (pinfunction "2_2") (pintype "passive"))
      (node (ref "U3") (pin "6") (pinfunction "BAT_6") (pintype "bidirectional"))
      (node (ref "U3") (pin "8") (pinfunction "SRP_8") (pintype "bidirectional"))
    )
    (net (code "160") (name "BOOST_EN") (class "Default")
      (node (ref "Q3") (pin "3") (pinfunction "D_3") (pintype "passive"))
      (node (ref "R13") (pin "1") (pinfunction "1_1") (pintype "passive"))
      (node (ref "R36") (pin "2") (pinfunction "2_2") (pintype "passive"))
    )
    (net (code "161") (name "EXT_VCC_PCIE") (class "Default")
      (node (ref "M.2KEYM(NGFF)") (pin "12") (pinfunction "P12_12") (pintype "passive"))
      (node (ref "M.2KEYM(NGFF)") (pin "14") (pinfunction "P14_14") (pintype "passive"))
      (node (ref "M.2KEYM(NGFF)") (pin "16") (pinfunction "P16_16") (pintype "passive"))
      (node (ref "M.2KEYM(NGFF)") (pin "18") (pinfunction "P18_18") (pintype "passive"))
      (node (ref "M.2KEYM(NGFF)") (pin "2") (pinfunction "P2_2") (pintype "passive"))
      (node (ref "M.2KEYM(NGFF)") (pin "4") (pinfunction "P4_4") (pintype "passive"))
      (node (ref "M.2KEYM(NGFF)") (pin "70") (pinfunction "P70_70") (pintype "passive"))
      (node (ref "M.2KEYM(NGFF)") (pin "72") (pinfunction "P72_72") (pintype "passive"))
      (node (ref "M.2KEYM(NGFF)") (pin "74") (pinfunction "P74_74") (pintype "passive"))
      (node (ref "RPIBOOT3") (pin "P$1") (pinfunction "1_P$1") (pintype "bidirectional"))
    )
    (net (code "162") (name "GND") (class "Default")
      (node (ref "C1") (pin "2") (pinfunction "2_2") (pintype "passive"))
      (node (ref "C10") (pin "2") (pinfunction "2_2") (pintype "passive"))
      (node (ref "C11") (pin "2") (pinfunction "2_2") (pintype "passive"))
      (node (ref "C12") (pin "2") (pinfunction "2_2") (pintype "passive"))
      (node (ref "C13") (pin "2") (pinfunction "2_2") (pintype "passive"))
      (node (ref "C14") (pin "2") (pinfunction "2_2") (pintype "passive"))
      (node (ref "C15") (pin "2") (pinfunction "2_2") (pintype "passive"))
      (node (ref "C16") (pin "2") (pinfunction "2_2") (pintype "passive"))
      (node (ref "C17") (pin "2") (pinfunction "2_2") (pintype "passive"))
      (node (ref "C19") (pin "2") (pinfunction "2_2") (pintype "passive"))
      (node (ref "C2") (pin "2") (pinfunction "2_2") (pintype "passive"))
      (node (ref "C20") (pin "2") (pinfunction "2_2") (pintype "passive"))
      (node (ref "C2040") (pin "19") (pinfunction "TESTEN_19") (pintype "input"))
      (node (ref "C2040") (pin "57") (pinfunction "GND_57") (pintype "passive"))
      (node (ref "C21") (pin "2") (pinfunction "2_2") (pintype "passive"))
      (node (ref "C22") (pin "2") (pinfunction "2_2") (pintype "passive"))
      (node (ref "C23") (pin "2") (pinfunction "2_2") (pintype "passive"))
      (node (ref "C24") (pin "1") (pinfunction "1_1") (pintype "passive"))
      (node (ref "C25") (pin "2") (pinfunction "2_2") (pintype "passive"))
      (node (ref "C26") (pin "2") (pinfunction "2_2") (pintype "passive"))
      (node (ref "C28") (pin "2") (pinfunction "2_2") (pintype "passive"))
      (node (ref "C3") (pin "2") (pinfunction "2_2") (pintype "passive"))
      (node (ref "C30") (pin "2") (pinfunction "2_2") (pintype "passive"))
      (node (ref "C31") (pin "2") (pinfunction "2_2") (pintype "passive"))
      (node (ref "C32") (pin "2") (pinfunction "2_2") (pintype "passive"))
      (node (ref "C33") (pin "2") (pinfunction "2_2") (pintype "passive"))
      (node (ref "C34") (pin "1") (pinfunction "1_1") (pintype "passive"))
      (node (ref "C35") (pin "2") (pinfunction "2_2") (pintype "passive"))
      (node (ref "C36") (pin "1") (pinfunction "1_1") (pintype "passive"))
      (node (ref "C4") (pin "2") (pinfunction "2_2") (pintype "passive"))
      (node (ref "C40") (pin "2") (pinfunction "2_2") (pintype "passive"))
      (node (ref "C42") (pin "2") (pinfunction "2_2") (pintype "passive"))
      (node (ref "C43") (pin "2") (pinfunction "2_2") (pintype "passive"))
      (node (ref "C44") (pin "2") (pinfunction "2_2") (pintype "passive"))
      (node (ref "C45") (pin "2") (pinfunction "2_2") (pintype "passive"))
      (node (ref "C46") (pin "2") (pinfunction "2_2") (pintype "passive"))
      (node (ref "C47") (pin "2") (pinfunction "2_2") (pintype "passive"))
      (node (ref "C48") (pin "2") (pinfunction "2_2") (pintype "passive"))
      (node (ref "C49") (pin "2") (pinfunction "2_2") (pintype "passive"))
      (node (ref "C5") (pin "2") (pinfunction "2_2") (pintype "passive"))
      (node (ref "C50") (pin "2") (pinfunction "2_2") (pintype "passive"))
      (node (ref "C53") (pin "2") (pinfunction "2_2") (pintype "passive"))
      (node (ref "C58") (pin "2") (pinfunction "2_2") (pintype "passive"))
      (node (ref "C59") (pin "2") (pinfunction "2_2") (pintype "passive"))
      (node (ref "C6") (pin "2") (pinfunction "2_2") (pintype "passive"))
      (node (ref "C60") (pin "2") (pinfunction "2_2") (pintype "passive"))
      (node (ref "C61") (pin "2") (pinfunction "2_2") (pintype "passive"))
      (node (ref "C62") (pin "2") (pinfunction "2_2") (pintype "passive"))
      (node (ref "C63") (pin "2") (pinfunction "2_2") (pintype "passive"))
      (node (ref "C64") (pin "2") (pinfunction "2_2") (pintype "passive"))
      (node (ref "C65") (pin "2") (pinfunction "2_2") (pintype "passive"))
      (node (ref "C66") (pin "2") (pinfunction "2_2") (pintype "passive"))
      (node (ref "C69") (pin "2") (pinfunction "2_2") (pintype "passive"))
      (node (ref "C7") (pin "2") (pinfunction "2_2") (pintype "passive"))
      (node (ref "C71") (pin "2") (pinfunction "2_2") (pintype "passive"))
      (node (ref "C72") (pin "2") (pinfunction "2_2") (pintype "passive"))
      (node (ref "C73") (pin "2") (pinfunction "2_2") (pintype "passive"))
      (node (ref "C74") (pin "2") (pinfunction "2_2") (pintype "passive"))
      (node (ref "C75") (pin "2") (pinfunction "2_2") (pintype "passive"))
      (node (ref "C76") (pin "2") (pinfunction "2_2") (pintype "passive"))
      (node (ref "C77") (pin "2") (pinfunction "2_2") (pintype "passive"))
      (node (ref "C79") (pin "2") (pinfunction "2_2") (pintype "passive"))
      (node (ref "C8") (pin "2") (pinfunction "2_2") (pintype "passive"))
      (node (ref "C80") (pin "2") (pinfunction "2_2") (pintype "passive"))
      (node (ref "C82") (pin "2") (pinfunction "2_2") (pintype "passive"))
      (node (ref "C83") (pin "1") (pinfunction "1_1") (pintype "passive"))
      (node (ref "C9") (pin "2") (pinfunction "2_2") (pintype "passive"))
      (node (ref "CAMERA") (pin "1") (pinfunction "1_1") (pintype "passive"))
      (node (ref "CAMERA") (pin "10") (pinfunction "10_10") (pintype "passive"))
      (node (ref "CAMERA") (pin "13") (pinfunction "13_13") (pintype "passive"))
      (node (ref "CAMERA") (pin "16") (pinfunction "16_16") (pintype "passive"))
      (node (ref "CAMERA") (pin "19") (pinfunction "19_19") (pintype "passive"))
      (node (ref "CAMERA") (pin "4") (pinfunction "4_4") (pintype "passive"))
      (node (ref "CAMERA") (pin "7") (pinfunction "7_7") (pintype "passive"))
      (node (ref "CAMERA") (pin "P1") (pinfunction "P1_P1") (pintype "passive"))
      (node (ref "CAMERA") (pin "P2") (pinfunction "P2_P2") (pintype "passive"))
      (node (ref "D2") (pin "1") (pinfunction "K_1") (pintype "bidirectional"))
      (node (ref "EINK_524352471") (pin "17") (pinfunction "17_17") (pintype "passive"))
      (node (ref "EINK_524352471") (pin "8") (pinfunction "8_8") (pintype "passive"))
      (node (ref "EINK_524352471") (pin "P1") (pinfunction "P1_P1") (pintype "passive"))
      (node (ref "EINK_524352471") (pin "P2") (pinfunction "P2_P2") (pintype "passive"))
      (node (ref "FB5") (pin "1") (pinfunction "1_1") (pintype "passive"))
      (node (ref "GND") (pin "P$1") (pinfunction "1_P$1") (pintype "bidirectional"))
      (node (ref "GND13") (pin "P$1") (pinfunction "1_P$1") (pintype "bidirectional"))
      (node (ref "GND22") (pin "P$1") (pinfunction "1_P$1") (pintype "bidirectional"))
      (node (ref "GND26") (pin "P$1") (pinfunction "1_P$1") (pintype "bidirectional"))
      (node (ref "GND27") (pin "P$1") (pinfunction "1_P$1") (pintype "bidirectional"))
      (node (ref "GND34") (pin "P$1") (pinfunction "1_P$1") (pintype "bidirectional"))
      (node (ref "IC1") (pin "12") (pinfunction "GND_12") (pintype "power_in"))
      (node (ref "IC1") (pin "2") (pinfunction "GND_2") (pintype "power_in"))
      (node (ref "IC1") (pin "3") (pinfunction "GND_3") (pintype "power_in"))
      (node (ref "IC1") (pin "9") (pinfunction "SDO_9") (pintype "bidirectional"))
      (node (ref "IC3") (pin "20") (pinfunction "SPKGND2_20") (pintype "power_in"))
      (node (ref "IC3") (pin "24") (pinfunction "SPKGND1_24") (pintype "power_in"))
      (node (ref "IC3") (pin "9") (pinfunction "DGND_9") (pintype "power_in"))
      (node (ref "J1") (pin "1") (pinfunction "1_1") (pintype "passive"))
      (node (ref "J2") (pin "GND") (pinfunction "GND_GND") (pintype "bidirectional"))
      (node (ref "J2") (pin "GND2") (pinfunction "GND_GND2") (pintype "bidirectional"))
      (node (ref "J2") (pin "SHLD1") (pinfunction "SHLD_SHLD1") (pintype "bidirectional"))
      (node (ref "J2") (pin "SHLD2") (pinfunction "SHLD_SHLD2") (pintype "bidirectional"))
      (node (ref "J2") (pin "SHLD3") (pinfunction "SHLD_SHLD3") (pintype "bidirectional"))
      (node (ref "J2") (pin "SHLD4") (pinfunction "SHLD_SHLD4") (pintype "bidirectional"))
      (node (ref "J2") (pin "SHLD5") (pinfunction "SHLD_SHLD5") (pintype "bidirectional"))
      (node (ref "J2") (pin "SHLD6") (pinfunction "SHLD_SHLD6") (pintype "bidirectional"))
      (node (ref "J2") (pin "SHLD7") (pinfunction "SHLD_SHLD7") (pintype "bidirectional"))
      (node (ref "J2") (pin "SHLD8") (pinfunction "SHLD_SHLD8") (pintype "bidirectional"))
      (node (ref "J3") (pin "4") (pinfunction "4_4") (pintype "passive"))
      (node (ref "J4") (pin "4") (pinfunction "4_4") (pintype "passive"))
      (node (ref "J5") (pin "3") (pinfunction "3_3") (pintype "passive"))
      (node (ref "J5") (pin "4") (pinfunction "4_4") (pintype "passive"))
      (node (ref "LED2") (pin "C") (pinfunction "C_C") (pintype "passive"))
      (node (ref "LED3") (pin "C") (pinfunction "C_C") (pintype "passive"))
      (node (ref "LOW_BATT") (pin "C") (pinfunction "C_C") (pintype "passive"))
      (node (ref "M.2KEYM(NGFF)") (pin "1") (pinfunction "P1_1") (pintype "passive"))
      (node (ref "M.2KEYM(NGFF)") (pin "15") (pinfunction "P15_15") (pintype "passive"))
      (node (ref "M.2KEYM(NGFF)") (pin "21") (pinfunction "P21_21") (pintype "passive"))
      (node (ref "M.2KEYM(NGFF)") (pin "27") (pinfunction "P27_27") (pintype "passive"))
      (node (ref "M.2KEYM(NGFF)") (pin "3") (pinfunction "P3_3") (pintype "passive"))
      (node (ref "M.2KEYM(NGFF)") (pin "33") (pinfunction "P33_33") (pintype "passive"))
      (node (ref "M.2KEYM(NGFF)") (pin "39") (pinfunction "P39_39") (pintype "passive"))
      (node (ref "M.2KEYM(NGFF)") (pin "45") (pinfunction "P45_45") (pintype "passive"))
      (node (ref "M.2KEYM(NGFF)") (pin "51") (pinfunction "P51_51") (pintype "passive"))
      (node (ref "M.2KEYM(NGFF)") (pin "57") (pinfunction "P57_57") (pintype "passive"))
      (node (ref "M.2KEYM(NGFF)") (pin "71") (pinfunction "P71_71") (pintype "passive"))
      (node (ref "M.2KEYM(NGFF)") (pin "73") (pinfunction "P73_73") (pintype "passive"))
      (node (ref "M.2KEYM(NGFF)") (pin "75") (pinfunction "P75_75") (pintype "passive"))
      (node (ref "M.2KEYM(NGFF)") (pin "9") (pinfunction "P9_9") (pintype "passive"))
      (node (ref "M.2KEYM(NGFF)") (pin "SH1") (pinfunction "SHIELD_SH1") (pintype "passive"))
      (node (ref "M.2KEYM(NGFF)") (pin "SH2") (pinfunction "SHIELD_SH2") (pintype "passive"))
      (node (ref "OSC2") (pin "2") (pinfunction "GND_2") (pintype "power_in"))
      (node (ref "Q3") (pin "2") (pinfunction "S_2") (pintype "passive"))
      (node (ref "Q4") (pin "2") (pinfunction "S_2") (pintype "passive"))
      (node (ref "R11") (pin "1") (pinfunction "1_1") (pintype "passive"))
      (node (ref "R14") (pin "2") (pinfunction "2_2") (pintype "passive"))
      (node (ref "R16") (pin "1") (pinfunction "1_1") (pintype "passive"))
      (node (ref "R17") (pin "1") (pinfunction "1_1") (pintype "passive"))
      (node (ref "R19") (pin "1") (pinfunction "1_1") (pintype "passive"))
      (node (ref "R2") (pin "1") (pinfunction "1_1") (pintype "passive"))
      (node (ref "R21") (pin "1") (pinfunction "1_1") (pintype "passive"))
      (node (ref "R23") (pin "2") (pinfunction "2_2") (pintype "passive"))
      (node (ref "R24") (pin "2") (pinfunction "2_2") (pintype "passive"))
      (node (ref "R28") (pin "1") (pinfunction "1_1") (pintype "passive"))
      (node (ref "R37") (pin "1") (pinfunction "1_1") (pintype "passive"))
      (node (ref "R4") (pin "1") (pinfunction "1_1") (pintype "passive"))
      (node (ref "R41") (pin "2") (pinfunction "2_2") (pintype "passive"))
      (node (ref "R6") (pin "2") (pinfunction "2_2") (pintype "passive"))
      (node (ref "R7") (pin "2") (pinfunction "2_2") (pintype "passive"))
      (node (ref "R9") (pin "1") (pinfunction "1_1") (pintype "passive"))
      (node (ref "RPI-CM1") (pin "1") (pinfunction "GND_1") (pintype "passive"))
      (node (ref "RPI-CM1") (pin "107") (pinfunction "GND_107") (pintype "passive"))
      (node (ref "RPI-CM1") (pin "108") (pinfunction "GND_108") (pintype "passive"))
      (node (ref "RPI-CM1") (pin "113") (pinfunction "GND_113") (pintype "passive"))
      (node (ref "RPI-CM1") (pin "114") (pinfunction "GND_114") (pintype "passive"))
      (node (ref "RPI-CM1") (pin "119") (pinfunction "GND_119") (pintype "passive"))
      (node (ref "RPI-CM1") (pin "120") (pinfunction "GND_120") (pintype "passive"))
      (node (ref "RPI-CM1") (pin "125") (pinfunction "GND_125") (pintype "passive"))
      (node (ref "RPI-CM1") (pin "126") (pinfunction "GND_126") (pintype "passive"))
      (node (ref "RPI-CM1") (pin "13") (pinfunction "GND_13") (pintype "passive"))
      (node (ref "RPI-CM1") (pin "131") (pinfunction "GND_131") (pintype "passive"))
      (node (ref "RPI-CM1") (pin "132") (pinfunction "GND_132") (pintype "passive"))
      (node (ref "RPI-CM1") (pin "137") (pinfunction "GND_137") (pintype "passive"))
      (node (ref "RPI-CM1") (pin "138") (pinfunction "GND_138") (pintype "passive"))
      (node (ref "RPI-CM1") (pin "14") (pinfunction "GND_14") (pintype "passive"))
      (node (ref "RPI-CM1") (pin "144") (pinfunction "GND_144") (pintype "passive"))
      (node (ref "RPI-CM1") (pin "150") (pinfunction "GND_150") (pintype "passive"))
      (node (ref "RPI-CM1") (pin "155") (pinfunction "GND_155") (pintype "passive"))
      (node (ref "RPI-CM1") (pin "156") (pinfunction "GND_156") (pintype "passive"))
      (node (ref "RPI-CM1") (pin "161") (pinfunction "GND_161") (pintype "passive"))
      (node (ref "RPI-CM1") (pin "162") (pinfunction "GND_162") (pintype "passive"))
      (node (ref "RPI-CM1") (pin "167") (pinfunction "GND_167") (pintype "passive"))
      (node (ref "RPI-CM1") (pin "168") (pinfunction "GND_168") (pintype "passive"))
      (node (ref "RPI-CM1") (pin "173") (pinfunction "GND_173") (pintype "passive"))
      (node (ref "RPI-CM1") (pin "174") (pinfunction "GND_174") (pintype "passive"))
      (node (ref "RPI-CM1") (pin "179") (pinfunction "GND_179") (pintype "passive"))
      (node (ref "RPI-CM1") (pin "180") (pinfunction "GND_180") (pintype "passive"))
      (node (ref "RPI-CM1") (pin "185") (pinfunction "GND_185") (pintype "passive"))
      (node (ref "RPI-CM1") (pin "186") (pinfunction "GND_186") (pintype "passive"))
      (node (ref "RPI-CM1") (pin "191") (pinfunction "GND_191") (pintype "passive"))
      (node (ref "RPI-CM1") (pin "192") (pinfunction "GND_192") (pintype "passive"))
      (node (ref "RPI-CM1") (pin "197") (pinfunction "GND_197") (pintype "passive"))
      (node (ref "RPI-CM1") (pin "198") (pinfunction "GND_198") (pintype "passive"))
      (node (ref "RPI-CM1") (pin "2") (pinfunction "GND_2") (pintype "passive"))
      (node (ref "RPI-CM1") (pin "22") (pinfunction "GND_22") (pintype "passive"))
      (node (ref "RPI-CM1") (pin "23") (pinfunction "GND_23") (pintype "passive"))
      (node (ref "RPI-CM1") (pin "32") (pinfunction "GND_32") (pintype "passive"))
      (node (ref "RPI-CM1") (pin "33") (pinfunction "GND_33") (pintype "passive"))
      (node (ref "RPI-CM1") (pin "42") (pinfunction "GND_42") (pintype "passive"))
      (node (ref "RPI-CM1") (pin "43") (pinfunction "GND_43") (pintype "passive"))
      (node (ref "RPI-CM1") (pin "52") (pinfunction "GND_52") (pintype "passive"))
      (node (ref "RPI-CM1") (pin "53") (pinfunction "GND_53") (pintype "passive"))
      (node (ref "RPI-CM1") (pin "59") (pinfunction "GND_59") (pintype "passive"))
      (node (ref "RPI-CM1") (pin "60") (pinfunction "GND_60") (pintype "passive"))
      (node (ref "RPI-CM1") (pin "65") (pinfunction "GND_65") (pintype "passive"))
      (node (ref "RPI-CM1") (pin "66") (pinfunction "GND_66") (pintype "passive"))
      (node (ref "RPI-CM1") (pin "7") (pinfunction "GND_7") (pintype "passive"))
      (node (ref "RPI-CM1") (pin "71") (pinfunction "GND_71") (pintype "passive"))
      (node (ref "RPI-CM1") (pin "74") (pinfunction "GND_74") (pintype "passive"))
      (node (ref "RPI-CM1") (pin "8") (pinfunction "GND_8") (pintype "passive"))
      (node (ref "RPI-CM1") (pin "98") (pinfunction "GND_98") (pintype "passive"))
      (node (ref "U1") (pin "10") (pinfunction "SYNC_10") (pintype "input"))
      (node (ref "U1") (pin "13") (pinfunction "GND_13") (pintype "power_in"))
      (node (ref "U1") (pin "5") (pinfunction "PGND_5") (pintype "power_in"))
      (node (ref "U1") (pin "6") (pinfunction "PGND_6") (pintype "power_in"))
      (node (ref "U1") (pin "7") (pinfunction "PGND_7") (pintype "power_in"))
      (node (ref "U1") (pin "P$18") (pinfunction "PGND_P$18") (pintype "power_in"))
      (node (ref "U1") (pin "P$19") (pinfunction "PGND_P$19") (pintype "power_in"))
      (node (ref "U1") (pin "P$20") (pinfunction "PGND_P$20") (pintype "power_in"))
      (node (ref "U1") (pin "P$21") (pinfunction "PGND_P$21") (pintype "power_in"))
      (node (ref "U1") (pin "P$22") (pinfunction "PGND_P$22") (pintype "power_in"))
      (node (ref "U1") (pin "THERMAL") (pinfunction "PGND_THERMAL") (pintype "power_in"))
      (node (ref "U10") (pin "2") (pinfunction "GND_2") (pintype "power_in"))
      (node (ref "U11") (pin "2") (pinfunction "GND_2") (pintype "power_in"))
      (node (ref "U12") (pin "2") (pinfunction "GND_2") (pintype "power_in"))
      (node (ref "U12") (pin "3") (pinfunction "GND_3") (pintype "power_in"))
      (node (ref "U12") (pin "5") (pinfunction "GND_5") (pintype "power_in"))
      (node (ref "U12") (pin "6") (pinfunction "GND_6") (pintype "power_in"))
      (node (ref "U13") (pin "8") (pinfunction "GND_8") (pintype "power_in"))
      (node (ref "U14") (pin "2") (pinfunction "P$V-_2") (pintype "bidirectional"))
      (node (ref "U15") (pin "2") (pinfunction "GND_2") (pintype "power_in"))
      (node (ref "U16") (pin "4") (pinfunction "GND_4") (pintype "power_in"))
      (node (ref "U17") (pin "1") (pinfunction "I/O_2_1") (pintype "passive"))
      (node (ref "U18") (pin "1") (pinfunction "I/O_2_1") (pintype "passive"))
      (node (ref "U19") (pin "1") (pinfunction "I/O_2_1") (pintype "passive"))
      (node (ref "U2") (pin "3") (pinfunction "GND_3") (pintype "passive"))
      (node (ref "U20") (pin "1") (pinfunction "I/O_2_1") (pintype "passive"))
      (node (ref "U21") (pin "1") (pinfunction "I/O_2_1") (pintype "passive"))
      (node (ref "U22") (pin "1") (pinfunction "I/O_2_1") (pintype "passive"))
      (node (ref "U23") (pin "1") (pinfunction "I/O_2_1") (pintype "passive"))
      (node (ref "U24") (pin "1") (pinfunction "I/O_2_1") (pintype "passive"))
      (node (ref "U25") (pin "4") (pinfunction "IN/TRIG_4") (pintype "input"))
      (node (ref "U25") (pin "8") (pinfunction "GND_8") (pintype "power_in"))
      (node (ref "U3") (pin "3") (pinfunction "VSS_3") (pintype "bidirectional"))
      (node (ref "U3") (pin "EP") (pinfunction "PWPD_EP") (pintype "bidirectional"))
      (node (ref "U3") (pin "EP1") (pinfunction "PWPD_EP1") (pintype "bidirectional"))
      (node (ref "U3") (pin "EP2") (pinfunction "PWPD_EP2") (pintype "bidirectional"))
      (node (ref "U3") (pin "EP3") (pinfunction "PWPD_EP3") (pintype "bidirectional"))
      (node (ref "U3") (pin "EP4") (pinfunction "PWPD_EP4") (pintype "bidirectional"))
      (node (ref "U4") (pin "14") (pinfunction "TMR_14") (pintype "bidirectional"))
      (node (ref "U4") (pin "15") (pinfunction "SYSOFF_15") (pintype "bidirectional"))
      (node (ref "U4") (pin "6") (pinfunction "EN1_6") (pintype "bidirectional"))
      (node (ref "U4") (pin "8") (pinfunction "VSS_8") (pintype "bidirectional"))
      (node (ref "U4") (pin "EP") (pinfunction "EP_EP") (pintype "bidirectional"))
      (node (ref "U5") (pin "3") (pinfunction "GND_3") (pintype "passive"))
      (node (ref "U6") (pin "1") (pinfunction "SDO_1") (pintype "bidirectional"))
      (node (ref "U6") (pin "6") (pinfunction "GND_6") (pintype "power_in"))
      (node (ref "U6") (pin "7") (pinfunction "GND_7") (pintype "power_in"))
      (node (ref "U7") (pin "21") (pinfunction "PAD_21") (pintype "power_in"))
      (node (ref "U7") (pin "9") (pinfunction "GND_9") (pintype "power_in"))
      (node (ref "U9") (pin "4") (pinfunction "GND_4") (pintype "power_in"))
      (node (ref "USB2.0MUX") (pin "10") (pinfunction "S_10") (pintype "input"))
      (node (ref "USB2.0MUX") (pin "4") (pinfunction "GND_4") (pintype "passive"))
      (node (ref "Y1") (pin "2") (pinfunction "GND_1_2") (pintype "bidirectional"))
      (node (ref "Y1") (pin "4") (pinfunction "GND_2_4") (pintype "bidirectional"))
    )
    (net (code "163") (name "GPOUT") (class "Default")
      (node (ref "R33") (pin "1") (pinfunction "1_1") (pintype "passive"))
      (node (ref "U3") (pin "12") (pinfunction "GPOUT_12") (pintype "bidirectional"))
    )
    (net (code "164") (name "HAP_3V3") (class "Default")
      (node (ref "C33") (pin "1") (pinfunction "1_1") (pintype "passive"))
      (node (ref "C35") (pin "1") (pinfunction "1_1") (pintype "passive"))
      (node (ref "U15") (pin "5") (pinfunction "OUT_5") (pintype "power_in"))
      (node (ref "U25") (pin "10") (pinfunction "VDD_10") (pintype "power_in"))
      (node (ref "U25") (pin "5") (pinfunction "EN_5") (pintype "input"))
      (node (ref "U25") (pin "6") (pinfunction "VDD/NC_6") (pintype "power_in"))
    )
    (net (code "165") (name "Net-(C29-Pad2)") (class "Default")
      (node (ref "C29") (pin "2") (pinfunction "2_2") (pintype "passive"))
      (node (ref "R38") (pin "2") (pinfunction "2_2") (pintype "passive"))
    )
    (net (code "166") (name "Net-(D1-PadC)") (class "Default")
      (node (ref "D1") (pin "C") (pinfunction "C_C") (pintype "passive"))
      (node (ref "R10") (pin "1") (pinfunction "1_1") (pintype "passive"))
    )
    (net (code "167") (name "Net-(D2-A)") (class "Default")
      (node (ref "C18") (pin "1") (pinfunction "1_1") (pintype "passive"))
      (node (ref "D2") (pin "2") (pinfunction "A_2") (pintype "bidirectional"))
      (node (ref "D3") (pin "1") (pinfunction "K_1") (pintype "bidirectional"))
    )
    (net (code "168") (name "Net-(D4-A)") (class "Default")
      (node (ref "C18") (pin "2") (pinfunction "2_2") (pintype "passive"))
      (node (ref "D4") (pin "2") (pinfunction "A_2") (pintype "bidirectional"))
      (node (ref "L3") (pin "2") (pinfunction "2_2") (pintype "passive"))
      (node (ref "Q1") (pin "3") (pinfunction "D_3") (pintype "bidirectional"))
    )
    (net (code "169") (name "Net-(D5-PadC)") (class "Default")
      (node (ref "D5") (pin "C") (pinfunction "C_C") (pintype "passive"))
      (node (ref "R22") (pin "1") (pinfunction "1_1") (pintype "passive"))
    )
    (net (code "170") (name "Net-(D6-PadC)") (class "Default")
      (node (ref "D6") (pin "C") (pinfunction "C_C") (pintype "passive"))
      (node (ref "R23") (pin "1") (pinfunction "1_1") (pintype "passive"))
    )
    (net (code "171") (name "Net-(D7-PadC)") (class "Default")
      (node (ref "D7") (pin "C") (pinfunction "C_C") (pintype "passive"))
      (node (ref "R14") (pin "1") (pinfunction "1_1") (pintype "passive"))
    )
    (net (code "172") (name "Net-(IC1-C1)") (class "Default")
      (node (ref "C31") (pin "1") (pinfunction "1_1") (pintype "passive"))
      (node (ref "IC1") (pin "4") (pinfunction "C1_4") (pintype "input"))
    )
    (net (code "173") (name "Net-(IC3-SPK_LN)") (class "Default")
      (node (ref "FB3") (pin "1") (pinfunction "1_1") (pintype "passive"))
      (node (ref "IC3") (pin "23") (pinfunction "SPK_LN_23") (pintype "output"))
    )
    (net (code "174") (name "Net-(IC3-SPK_LP)") (class "Default")
      (node (ref "FB2") (pin "1") (pinfunction "1_1") (pintype "passive"))
      (node (ref "IC3") (pin "25") (pinfunction "SPK_LP_25") (pintype "output"))
    )
    (net (code "175") (name "Net-(J2-CC1)") (class "Default")
      (node (ref "J2") (pin "A5") (pinfunction "CC1_A5") (pintype "bidirectional"))
      (node (ref "R19") (pin "2") (pinfunction "2_2") (pintype "passive"))
    )
    (net (code "176") (name "Net-(J2-CC2)") (class "Default")
      (node (ref "J2") (pin "B5") (pinfunction "CC2_B5") (pintype "bidirectional"))
      (node (ref "R21") (pin "2") (pinfunction "2_2") (pintype "passive"))
    )
    (net (code "177") (name "Net-(L1-2)") (class "Default")
      (node (ref "L1") (pin "P$2") (pinfunction "2_P$2") (pintype "passive"))
      (node (ref "U1") (pin "3") (pinfunction "SW_3") (pintype "input"))
      (node (ref "U1") (pin "4") (pinfunction "SW_4") (pintype "input"))
    )
    (net (code "178") (name "Net-(LED2-PadA)") (class "Default")
      (node (ref "LED2") (pin "A") (pinfunction "A_A") (pintype "passive"))
      (node (ref "R5") (pin "2") (pinfunction "2_2") (pintype "passive"))
    )
    (net (code "179") (name "Net-(LED3-PadA)") (class "Default")
      (node (ref "LED3") (pin "A") (pinfunction "A_A") (pintype "passive"))
      (node (ref "R8") (pin "1") (pinfunction "1_1") (pintype "passive"))
    )
    (net (code "180") (name "Net-(LOW_BATT-PadA)") (class "Default")
      (node (ref "LOW_BATT") (pin "A") (pinfunction "A_A") (pintype "passive"))
      (node (ref "R20") (pin "1") (pinfunction "1_1") (pintype "passive"))
    )
    (net (code "181") (name "Net-(Q2-G)") (class "Default")
      (node (ref "Q2") (pin "1") (pinfunction "G_1") (pintype "passive"))
      (node (ref "R43") (pin "2") (pinfunction "2_2") (pintype "passive"))
      (node (ref "R44") (pin "1") (pinfunction "1_1") (pintype "passive"))
    )
    (net (code "182") (name "Net-(Q4-D)") (class "Default")
      (node (ref "Q4") (pin "3") (pinfunction "D_3") (pintype "passive"))
      (node (ref "R34") (pin "2") (pinfunction "2_2") (pintype "passive"))
      (node (ref "USB_BOOT_N") (pin "P$1") (pinfunction "1_P$1") (pintype "bidirectional"))
    )
    (net (code "183") (name "Net-(R20-Pad2)") (class "Default")
      (node (ref "R20") (pin "2") (pinfunction "2_2") (pintype "passive"))
      (node (ref "T1") (pin "C") (pinfunction "C_C") (pintype "passive"))
    )
    (net (code "184") (name "Net-(RPI-CM1A-GPIO_VREF)") (class "Default")
      (node (ref "RPI-CM1") (pin "78") (pinfunction "GPIO_VREF_78") (pintype "passive"))
      (node (ref "SJ6") (pin "2") (pinfunction "2_2") (pintype "passive"))
    )
    (net (code "185") (name "Net-(RPI-CM1A-PI_LED_~{PWR})") (class "Default")
      (node (ref "RPI-CM1") (pin "95") (pinfunction "PI_LED_~{PWR}_95") (pintype "passive"))
      (node (ref "U2") (pin "2") (pinfunction "IN_A_2") (pintype "input"))
    )
    (net (code "186") (name "Net-(RPI-CM1A-PI_~{LED_ACTIVITY})") (class "Default")
      (node (ref "R10") (pin "2") (pinfunction "2_2") (pintype "passive"))
      (node (ref "RPI-CM1") (pin "21") (pinfunction "PI_~{LED_ACTIVITY}_21") (pintype "passive"))
    )
    (net (code "187") (name "Net-(U1-EN)") (class "Default")
      (node (ref "R13") (pin "2") (pinfunction "2_2") (pintype "passive"))
      (node (ref "U1") (pin "11") (pinfunction "EN_11") (pintype "input"))
    )
    (net (code "188") (name "Net-(U1-FB)") (class "Default")
      (node (ref "R3") (pin "1") (pinfunction "1_1") (pintype "passive"))
      (node (ref "R4") (pin "2") (pinfunction "2_2") (pintype "passive"))
      (node (ref "U1") (pin "14") (pinfunction "FB_14") (pintype "input"))
    )
    (net (code "189") (name "Net-(U1-LBI)") (class "Default")
      (node (ref "R1") (pin "1") (pinfunction "1_1") (pintype "passive"))
      (node (ref "R2") (pin "2") (pinfunction "2_2") (pintype "passive"))
      (node (ref "U1") (pin "9") (pinfunction "LBI_9") (pintype "input"))
    )
    (net (code "190") (name "Net-(U2-OUT_~{Y})") (class "Default")
      (node (ref "R8") (pin "2") (pinfunction "2_2") (pintype "passive"))
      (node (ref "U2") (pin "4") (pinfunction "OUT_~{Y}_4") (pintype "output"))
    )
    (net (code "191") (name "Net-(U4-ILIM)") (class "Default")
      (node (ref "R7") (pin "1") (pinfunction "1_1") (pintype "passive"))
      (node (ref "U4") (pin "12") (pinfunction "ILIM_12") (pintype "bidirectional"))
    )
    (net (code "192") (name "Net-(U4-ISET)") (class "Default")
      (node (ref "R6") (pin "1") (pinfunction "1_1") (pintype "passive"))
      (node (ref "U4") (pin "16") (pinfunction "ISET_16") (pintype "bidirectional"))
    )
    (net (code "193") (name "Net-(U4-~{CHG})") (class "Default")
      (node (ref "R22") (pin "2") (pinfunction "2_2") (pintype "passive"))
      (node (ref "U4") (pin "9") (pinfunction "~{CHG}_9") (pintype "bidirectional"))
    )
    (net (code "194") (name "Net-(U5-OUT_~{Y})") (class "Default")
      (node (ref "R44") (pin "2") (pinfunction "2_2") (pintype "passive"))
      (node (ref "U5") (pin "4") (pinfunction "OUT_~{Y}_4") (pintype "output"))
    )
    (net (code "195") (name "Net-(U10-OUT)") (class "Default")
      (node (ref "C62") (pin "1") (pinfunction "1_1") (pintype "passive"))
      (node (ref "C69") (pin "1") (pinfunction "1_1") (pintype "passive"))
      (node (ref "FB1") (pin "1") (pinfunction "1_1") (pintype "passive"))
      (node (ref "U10") (pin "5") (pinfunction "OUT_5") (pintype "power_in"))
    )
    (net (code "196") (name "Net-(U12-OUTPUT)") (class "Default")
      (node (ref "C29") (pin "1") (pinfunction "1_1") (pintype "passive"))
      (node (ref "U12") (pin "1") (pinfunction "OUTPUT_1") (pintype "output"))
    )
    (net (code "197") (name "Net-(U14A-+IN)") (class "Default")
      (node (ref "C30") (pin "1") (pinfunction "1_1") (pintype "passive"))
      (node (ref "R27") (pin "1") (pinfunction "1_1") (pintype "passive"))
      (node (ref "R37") (pin "2") (pinfunction "2_2") (pintype "passive"))
      (node (ref "U14") (pin "3") (pinfunction "+IN_3") (pintype "input"))
    )
    (net (code "198") (name "Net-(U14A--IN)") (class "Default")
      (node (ref "C27") (pin "1") (pinfunction "1_1") (pintype "passive"))
      (node (ref "R38") (pin "1") (pinfunction "1_1") (pintype "passive"))
      (node (ref "R39") (pin "2") (pinfunction "2_2") (pintype "passive"))
      (node (ref "U14") (pin "4") (pinfunction "-IN_4") (pintype "input"))
    )
    (net (code "199") (name "Net-(U25-REG)") (class "Default")
      (node (ref "C34") (pin "2") (pinfunction "2_2") (pintype "passive"))
      (node (ref "U25") (pin "1") (pinfunction "REG_1") (pintype "output"))
    )
    (net (code "200") (name "Net-(Y1-CRYSTAL_2)") (class "Default")
      (node (ref "C83") (pin "2") (pinfunction "2_2") (pintype "passive"))
      (node (ref "R35") (pin "2") (pinfunction "2_2") (pintype "passive"))
      (node (ref "Y1") (pin "3") (pinfunction "CRYSTAL_2_3") (pintype "bidirectional"))
    )
    (net (code "201") (name "PREVGH") (class "Default")
      (node (ref "C16") (pin "1") (pinfunction "1_1") (pintype "passive"))
      (node (ref "D4") (pin "1") (pinfunction "K_1") (pintype "bidirectional"))
      (node (ref "EINK_524352471") (pin "4") (pinfunction "4_4") (pintype "passive"))
    )
    (net (code "202") (name "PREVGL") (class "Default")
      (node (ref "C14") (pin "1") (pinfunction "1_1") (pintype "passive"))
      (node (ref "D3") (pin "2") (pinfunction "A_2") (pintype "bidirectional"))
      (node (ref "EINK_524352471") (pin "2") (pinfunction "2_2") (pintype "passive"))
    )
    (net (code "203") (name "SAM_1V1") (class "Default")
      (node (ref "C2040") (pin "23") (pinfunction "DVDD_2_23") (pintype "power_in"))
      (node (ref "C2040") (pin "45") (pinfunction "VREG_VOUT_45") (pintype "output"))
      (node (ref "C2040") (pin "50") (pinfunction "DVDD_50") (pintype "power_in"))
      (node (ref "C76") (pin "1") (pinfunction "1_1") (pintype "passive"))
      (node (ref "C77") (pin "1") (pinfunction "1_1") (pintype "passive"))
    )
    (net (code "204") (name "SAM_3V3") (class "Default")
      (node (ref "BUD") (pin "1_1") (pinfunction "1_1_1") (pintype "passive"))
      (node (ref "BUD") (pin "1_2") (pinfunction "1_1_2") (pintype "passive"))
      (node (ref "BUP") (pin "1_1") (pinfunction "1_1_1") (pintype "passive"))
      (node (ref "BUP") (pin "1_2") (pinfunction "1_1_2") (pintype "passive"))
      (node (ref "BUS") (pin "1_1") (pinfunction "1_1_1") (pintype "passive"))
      (node (ref "BUS") (pin "1_2") (pinfunction "1_1_2") (pintype "passive"))
      (node (ref "C2040") (pin "1") (pinfunction "IOVDD_2_1") (pintype "power_in"))
      (node (ref "C2040") (pin "10") (pinfunction "IOVDD_3_10") (pintype "power_in"))
      (node (ref "C2040") (pin "22") (pinfunction "IOVDD_4_22") (pintype "power_in"))
      (node (ref "C2040") (pin "33") (pinfunction "IOVDD_5_33") (pintype "power_in"))
      (node (ref "C2040") (pin "42") (pinfunction "IOVDD_6_42") (pintype "power_in"))
      (node (ref "C2040") (pin "43") (pinfunction "ADC_AVDD_43") (pintype "power_in"))
      (node (ref "C2040") (pin "44") (pinfunction "VREG_VIN_44") (pintype "power_in"))
      (node (ref "C2040") (pin "48") (pinfunction "USB_VDD_48") (pintype "power_in"))
      (node (ref "C2040") (pin "49") (pinfunction "IOVDD_49") (pintype "power_in"))
      (node (ref "C24") (pin "2") (pinfunction "2_2") (pintype "passive"))
      (node (ref "C43") (pin "1") (pinfunction "1_1") (pintype "passive"))
      (node (ref "C44") (pin "1") (pinfunction "1_1") (pintype "passive"))
      (node (ref "C7") (pin "1") (pinfunction "1_1") (pintype "passive"))
      (node (ref "C71") (pin "1") (pinfunction "1_1") (pintype "passive"))
      (node (ref "C72") (pin "1") (pinfunction "1_1") (pintype "passive"))
      (node (ref "C73") (pin "1") (pinfunction "1_1") (pintype "passive"))
      (node (ref "C74") (pin "1") (pinfunction "1_1") (pintype "passive"))
      (node (ref "C75") (pin "1") (pinfunction "1_1") (pintype "passive"))
      (node (ref "C80") (pin "1") (pinfunction "1_1") (pintype "passive"))
      (node (ref "D7") (pin "A") (pinfunction "A_A") (pintype "passive"))
      (node (ref "J4") (pin "1") (pinfunction "1_1") (pintype "passive"))
      (node (ref "Q2") (pin "2") (pinfunction "S_2") (pintype "passive"))
      (node (ref "R16") (pin "2") (pinfunction "2_2") (pintype "passive"))
      (node (ref "R17") (pin "2") (pinfunction "2_2") (pintype "passive"))
      (node (ref "R25") (pin "2") (pinfunction "2_2") (pintype "passive"))
      (node (ref "R26") (pin "2") (pinfunction "2_2") (pintype "passive"))
      (node (ref "R28") (pin "2") (pinfunction "2_2") (pintype "passive"))
      (node (ref "R40") (pin "2") (pinfunction "2_2") (pintype "passive"))
      (node (ref "R42") (pin "2") (pinfunction "2_2") (pintype "passive"))
      (node (ref "R43") (pin "1") (pinfunction "1_1") (pintype "passive"))
      (node (ref "U11") (pin "5") (pinfunction "OUT_5") (pintype "power_in"))
      (node (ref "U16") (pin "8") (pinfunction "VCC_8") (pintype "power_in"))
      (node (ref "U5") (pin "5") (pinfunction "VCC_5") (pintype "power_in"))
      (node (ref "U7") (pin "19") (pinfunction "VCC_19") (pintype "power_in"))
      (node (ref "USB2.0MUX") (pin "9") (pinfunction "VCC_9") (pintype "power_in"))
    )
    (net (code "205") (name "SAM_QSPI_SCN") (class "Default")
      (node (ref "C2040") (pin "56") (pinfunction "QSPI_SCN_56") (pintype "bidirectional"))
      (node (ref "R34") (pin "1") (pinfunction "1_1") (pintype "passive"))
      (node (ref "U16") (pin "1") (pinfunction "~{CS}_1") (pintype "input"))
    )
    (net (code "206") (name "SAM_SCL") (class "Default")
      (node (ref "C2040") (pin "37") (pinfunction "GPIO25_37") (pintype "bidirectional"))
      (node (ref "J4") (pin "3") (pinfunction "3_3") (pintype "passive"))
      (node (ref "R26") (pin "1") (pinfunction "1_1") (pintype "passive"))
      (node (ref "RPIBOOT8") (pin "P$1") (pinfunction "1_P$1") (pintype "bidirectional"))
      (node (ref "U25") (pin "2") (pinfunction "SCL_2") (pintype "input"))
      (node (ref "U3") (pin "2") (pinfunction "SCL_2") (pintype "bidirectional"))
    )
    (net (code "207") (name "SAM_SDA") (class "Default")
      (node (ref "C2040") (pin "36") (pinfunction "GPIO24_36") (pintype "bidirectional"))
      (node (ref "GND37") (pin "P$1") (pinfunction "1_P$1") (pintype "bidirectional"))
      (node (ref "J4") (pin "2") (pinfunction "2_2") (pintype "passive"))
      (node (ref "R25") (pin "1") (pinfunction "1_1") (pintype "passive"))
      (node (ref "U25") (pin "3") (pinfunction "SDA_3") (pintype "bidirectional"))
      (node (ref "U3") (pin "1") (pinfunction "SDA_1") (pintype "bidirectional"))
    )
    (net (code "208") (name "SCL1") (class "Default")
      (node (ref "IC1") (pin "1") (pinfunction "SCL_1") (pintype "input"))
      (node (ref "IC3") (pin "17") (pinfunction "SCL_17") (pintype "input"))
      (node (ref "R18") (pin "1") (pinfunction "1_1") (pintype "passive"))
      (node (ref "RPI-CM1") (pin "56") (pinfunction "GPIO3_56") (pintype "passive"))
      (node (ref "RPIBOOT6") (pin "P$1") (pinfunction "1_P$1") (pintype "bidirectional"))
      (node (ref "U6") (pin "13") (pinfunction "SCL_13") (pintype "bidirectional"))
      (node (ref "U9") (pin "2") (pinfunction "SMCLK_2") (pintype "input"))
    )
    (net (code "209") (name "SDA1") (class "Default")
      (node (ref "GND7") (pin "P$1") (pinfunction "1_P$1") (pintype "bidirectional"))
      (node (ref "IC1") (pin "11") (pinfunction "SDA_11") (pintype "bidirectional"))
      (node (ref "IC3") (pin "18") (pinfunction "SDA_18") (pintype "bidirectional"))
      (node (ref "R15") (pin "1") (pinfunction "1_1") (pintype "passive"))
      (node (ref "RPI-CM1") (pin "58") (pinfunction "GPIO2_58") (pintype "passive"))
      (node (ref "U6") (pin "14") (pinfunction "SDA_14") (pintype "bidirectional"))
      (node (ref "U9") (pin "1") (pinfunction "SMDATA_1") (pintype "bidirectional"))
    )
    (net (code "210") (name "THERM") (class "Default")
      (node (ref "J1") (pin "2") (pinfunction "2_2") (pintype "passive"))
      (node (ref "SJ1") (pin "1") (pinfunction "1_1") (pintype "passive"))
    )
    (net (code "211") (name "TS") (class "Default")
      (node (ref "SJ1") (pin "2") (pinfunction "2_2") (pintype "passive"))
      (node (ref "U3") (pin "10") (pinfunction "BIN_10") (pintype "bidirectional"))
      (node (ref "U4") (pin "1") (pinfunction "TS_1") (pintype "bidirectional"))
    )
    (net (code "212") (name "UART_RXD3_SAM") (class "Default")
      (node (ref "C2040") (pin "2") (pinfunction "GPIO0_2") (pintype "bidirectional"))
      (node (ref "R40") (pin "1") (pinfunction "1_1") (pintype "passive"))
      (node (ref "RPI-CM1") (pin "34") (pinfunction "GPIO5_34") (pintype "passive"))
      (node (ref "RPIBOOT7") (pin "P$1") (pinfunction "1_P$1") (pintype "bidirectional"))
    )
    (net (code "213") (name "UART_TXD3_SAM") (class "Default")
      (node (ref "C2040") (pin "3") (pinfunction "GPIO1_3") (pintype "bidirectional"))
      (node (ref "GND36") (pin "P$1") (pinfunction "1_P$1") (pintype "bidirectional"))
      (node (ref "R42") (pin "1") (pinfunction "1_1") (pintype "passive"))
      (node (ref "RPI-CM1") (pin "54") (pinfunction "GPIO4_54") (pintype "passive"))
    )
    (net (code "214") (name "USB_N") (class "Default")
      (node (ref "J2") (pin "A7") (pinfunction "D-_A7") (pintype "bidirectional"))
      (node (ref "J2") (pin "B7") (pinfunction "D-_B7") (pintype "bidirectional"))
      (node (ref "RPI-CM1") (pin "103") (pinfunction "USB_N_103") (pintype "passive"))
      (node (ref "U13") (pin "5") (pinfunction "D2-_5") (pintype "passive"))
      (node (ref "USB2.0MUX") (pin "5") (pinfunction "D-_5") (pintype "bidirectional"))
    )
    (net (code "215") (name "USB_P") (class "Default")
      (node (ref "J2") (pin "A6") (pinfunction "D+_A6") (pintype "bidirectional"))
      (node (ref "J2") (pin "B6") (pinfunction "D+_B6") (pintype "bidirectional"))
      (node (ref "RPI-CM1") (pin "105") (pinfunction "USB_P_105") (pintype "passive"))
      (node (ref "U13") (pin "4") (pinfunction "D2+_4") (pintype "passive"))
      (node (ref "USB2.0MUX") (pin "3") (pinfunction "D+_3") (pintype "bidirectional"))
    )
    (net (code "216") (name "USB_SAM_N") (class "Default")
      (node (ref "R32") (pin "1") (pinfunction "1_1") (pintype "passive"))
      (node (ref "USB2.0MUX") (pin "7") (pinfunction "D1-_7") (pintype "bidirectional"))
    )
    (net (code "217") (name "USB_SAM_P") (class "Default")
      (node (ref "R31") (pin "1") (pinfunction "1_1") (pintype "passive"))
      (node (ref "USB2.0MUX") (pin "1") (pinfunction "D1+_1") (pintype "bidirectional"))
    )
    (net (code "218") (name "VBUS") (class "Default")
      (node (ref "C22") (pin "1") (pinfunction "1_1") (pintype "passive"))
      (node (ref "C3") (pin "1") (pinfunction "1_1") (pintype "passive"))
      (node (ref "C53") (pin "1") (pinfunction "1_1") (pintype "passive"))
      (node (ref "J2") (pin "VBUS1") (pinfunction "VBUS_VBUS1") (pintype "bidirectional"))
      (node (ref "J2") (pin "VBUS2") (pinfunction "VBUS_VBUS2") (pintype "bidirectional"))
      (node (ref "U4") (pin "13") (pinfunction "IN_13") (pintype "bidirectional"))
    )
    (net (code "219") (name "VOUT") (class "Default")
      (node (ref "C1") (pin "1") (pinfunction "1_1") (pintype "passive"))
      (node (ref "C21") (pin "1") (pinfunction "1_1") (pintype "passive"))
      (node (ref "C26") (pin "1") (pinfunction "1_1") (pintype "passive"))
      (node (ref "C32") (pin "1") (pinfunction "1_1") (pintype "passive"))
      (node (ref "C4") (pin "1") (pinfunction "1_1") (pintype "passive"))
      (node (ref "C79") (pin "1") (pinfunction "1_1") (pintype "passive"))
      (node (ref "D5") (pin "A") (pinfunction "A_A") (pintype "passive"))
      (node (ref "D6") (pin "A") (pinfunction "A_A") (pintype "passive"))
      (node (ref "L1") (pin "P$1") (pinfunction "1_P$1") (pintype "passive"))
      (node (ref "R1") (pin "2") (pinfunction "2_2") (pintype "passive"))
      (node (ref "R36") (pin "1") (pinfunction "1_1") (pintype "passive"))
      (node (ref "RPIBOOT4") (pin "P$1") (pinfunction "1_P$1") (pintype "bidirectional"))
      (node (ref "T1") (pin "E") (pinfunction "E_E") (pintype "passive"))
      (node (ref "U1") (pin "8") (pinfunction "VBAT_8") (pintype "input"))
      (node (ref "U11") (pin "1") (pinfunction "IN_1") (pintype "power_in"))
      (node (ref "U11") (pin "3") (pinfunction "EN_3") (pintype "input"))
      (node (ref "U15") (pin "1") (pinfunction "IN_1") (pintype "power_in"))
      (node (ref "U15") (pin "3") (pinfunction "EN_3") (pintype "input"))
      (node (ref "U4") (pin "10") (pinfunction "OUT_10") (pintype "bidirectional"))
      (node (ref "U4") (pin "11") (pinfunction "OUT_11") (pintype "bidirectional"))
      (node (ref "U4") (pin "5") (pinfunction "EN2_5") (pintype "bidirectional"))
    )
    (net (code "220") (name "V_BATT") (class "Default")
      (node (ref "C23") (pin "1") (pinfunction "1_1") (pintype "passive"))
      (node (ref "C40") (pin "1") (pinfunction "1_1") (pintype "passive"))
      (node (ref "R12") (pin "1") (pinfunction "1_1") (pintype "passive"))
      (node (ref "RPIBOOT5") (pin "P$1") (pinfunction "1_P$1") (pintype "bidirectional"))
      (node (ref "U3") (pin "7") (pinfunction "SRN_7") (pintype "bidirectional"))
      (node (ref "U4") (pin "2") (pinfunction "BAT_2") (pintype "bidirectional"))
      (node (ref "U4") (pin "3") (pinfunction "BAT_3") (pintype "bidirectional"))
    )
    (net (code "221") (name "unconnected-(C2040-GPIO20-Pad31)") (class "Default")
      (node (ref "C2040") (pin "31") (pinfunction "GPIO20_31") (pintype "bidirectional"))
    )
    (net (code "222") (name "unconnected-(CAMERA-Pad18)") (class "Default")
      (node (ref "CAMERA") (pin "18") (pinfunction "18_18") (pintype "passive"))
    )
    (net (code "223") (name "unconnected-(IC1-CS-Pad10)") (class "Default")
      (node (ref "IC1") (pin "10") (pinfunction "CS_10") (pintype "input"))
    )
    (net (code "224") (name "unconnected-(IC1-DRDY-Pad8)") (class "Default")
      (node (ref "IC1") (pin "8") (pinfunction "DRDY_8") (pintype "output"))
    )
    (net (code "225") (name "unconnected-(IC1-INT-Pad7)") (class "Default")
      (node (ref "IC1") (pin "7") (pinfunction "INT_7") (pintype "output"))
    )
    (net (code "226") (name "unconnected-(IC3-HP_L-Pad31)") (class "Default")
      (node (ref "IC3") (pin "31") (pinfunction "HP_L_31") (pintype "output"))
    )
    (net (code "227") (name "unconnected-(IC3-HP_R-Pad29)") (class "Default")
      (node (ref "IC3") (pin "29") (pinfunction "HP_R_29") (pintype "output"))
    )
    (net (code "228") (name "unconnected-(IC3-LINPUT1-Pad4)") (class "Default")
      (node (ref "IC3") (pin "4") (pinfunction "LINPUT1_4") (pintype "input"))
    )
    (net (code "229") (name "unconnected-(IC3-LINPUT2-Pad3)") (class "Default")
      (node (ref "IC3") (pin "3") (pinfunction "LINPUT2_3") (pintype "input"))
    )
    (net (code "230") (name "unconnected-(IC3-LINPUT3-Pad2)") (class "Default")
      (node (ref "IC3") (pin "2") (pinfunction "LINPUT3_2") (pintype "input"))
    )
    (net (code "231") (name "unconnected-(IC3-OUT3-Pad30)") (class "Default")
      (node (ref "IC3") (pin "30") (pinfunction "OUT3_30") (pintype "output"))
    )
    (net (code "232") (name "unconnected-(IC3-RINPUT2-Pad6)") (class "Default")
      (node (ref "IC3") (pin "6") (pinfunction "RINPUT2_6") (pintype "input"))
    )
    (net (code "233") (name "unconnected-(IC3-RINPUT3-Pad7)") (class "Default")
      (node (ref "IC3") (pin "7") (pinfunction "RINPUT3_7") (pintype "input"))
    )
    (net (code "234") (name "unconnected-(IC3-SPK_RN-Pad19)") (class "Default")
      (node (ref "IC3") (pin "19") (pinfunction "SPK_RN_19") (pintype "output"))
    )
    (net (code "235") (name "unconnected-(IC3-SPK_RP-Pad22)") (class "Default")
      (node (ref "IC3") (pin "22") (pinfunction "SPK_RP_22") (pintype "output"))
    )
    (net (code "236") (name "unconnected-(M.2KEYM(NGFF)-P5-Pad5)") (class "Default")
      (node (ref "M.2KEYM(NGFF)") (pin "5") (pinfunction "P5_5") (pintype "passive"))
    )
    (net (code "237") (name "unconnected-(M.2KEYM(NGFF)-P6-Pad6)") (class "Default")
      (node (ref "M.2KEYM(NGFF)") (pin "6") (pinfunction "P6_6") (pintype "passive"))
    )
    (net (code "238") (name "unconnected-(M.2KEYM(NGFF)-P7-Pad7)") (class "Default")
      (node (ref "M.2KEYM(NGFF)") (pin "7") (pinfunction "P7_7") (pintype "passive"))
    )
    (net (code "239") (name "unconnected-(M.2KEYM(NGFF)-P8-Pad8)") (class "Default")
      (node (ref "M.2KEYM(NGFF)") (pin "8") (pinfunction "P8_8") (pintype "passive"))
    )
    (net (code "240") (name "unconnected-(M.2KEYM(NGFF)-P10-Pad10)") (class "Default")
      (node (ref "M.2KEYM(NGFF)") (pin "10") (pinfunction "P10_10") (pintype "passive"))
    )
    (net (code "241") (name "unconnected-(M.2KEYM(NGFF)-P11-Pad11)") (class "Default")
      (node (ref "M.2KEYM(NGFF)") (pin "11") (pinfunction "P11_11") (pintype "passive"))
    )
    (net (code "242") (name "unconnected-(M.2KEYM(NGFF)-P13-Pad13)") (class "Default")
      (node (ref "M.2KEYM(NGFF)") (pin "13") (pinfunction "P13_13") (pintype "passive"))
    )
    (net (code "243") (name "unconnected-(M.2KEYM(NGFF)-P17-Pad17)") (class "Default")
      (node (ref "M.2KEYM(NGFF)") (pin "17") (pinfunction "P17_17") (pintype "passive"))
    )
    (net (code "244") (name "unconnected-(M.2KEYM(NGFF)-P19-Pad19)") (class "Default")
      (node (ref "M.2KEYM(NGFF)") (pin "19") (pinfunction "P19_19") (pintype "passive"))
    )
    (net (code "245") (name "unconnected-(M.2KEYM(NGFF)-P20-Pad20)") (class "Default")
      (node (ref "M.2KEYM(NGFF)") (pin "20") (pinfunction "P20_20") (pintype "passive"))
    )
    (net (code "246") (name "unconnected-(M.2KEYM(NGFF)-P22-Pad22)") (class "Default")
      (node (ref "M.2KEYM(NGFF)") (pin "22") (pinfunction "P22_22") (pintype "passive"))
    )
    (net (code "247") (name "unconnected-(M.2KEYM(NGFF)-P23-Pad23)") (class "Default")
      (node (ref "M.2KEYM(NGFF)") (pin "23") (pinfunction "P23_23") (pintype "passive"))
    )
    (net (code "248") (name "unconnected-(M.2KEYM(NGFF)-P24-Pad24)") (class "Default")
      (node (ref "M.2KEYM(NGFF)") (pin "24") (pinfunction "P24_24") (pintype "passive"))
    )
    (net (code "249") (name "unconnected-(M.2KEYM(NGFF)-P25-Pad25)") (class "Default")
      (node (ref "M.2KEYM(NGFF)") (pin "25") (pinfunction "P25_25") (pintype "passive"))
    )
    (net (code "250") (name "unconnected-(M.2KEYM(NGFF)-P26-Pad26)") (class "Default")
      (node (ref "M.2KEYM(NGFF)") (pin "26") (pinfunction "P26_26") (pintype "passive"))
    )
    (net (code "251") (name "unconnected-(M.2KEYM(NGFF)-P28-Pad28)") (class "Default")
      (node (ref "M.2KEYM(NGFF)") (pin "28") (pinfunction "P28_28") (pintype "passive"))
    )
    (net (code "252") (name "unconnected-(M.2KEYM(NGFF)-P29-Pad29)") (class "Default")
      (node (ref "M.2KEYM(NGFF)") (pin "29") (pinfunction "P29_29") (pintype "passive"))
    )
    (net (code "253") (name "unconnected-(M.2KEYM(NGFF)-P30-Pad30)") (class "Default")
      (node (ref "M.2KEYM(NGFF)") (pin "30") (pinfunction "P30_30") (pintype "passive"))
    )
    (net (code "254") (name "unconnected-(M.2KEYM(NGFF)-P31-Pad31)") (class "Default")
      (node (ref "M.2KEYM(NGFF)") (pin "31") (pinfunction "P31_31") (pintype "passive"))
    )
    (net (code "255") (name "unconnected-(M.2KEYM(NGFF)-P32-Pad32)") (class "Default")
      (node (ref "M.2KEYM(NGFF)") (pin "32") (pinfunction "P32_32") (pintype "passive"))
    )
    (net (code "256") (name "unconnected-(M.2KEYM(NGFF)-P34-Pad34)") (class "Default")
      (node (ref "M.2KEYM(NGFF)") (pin "34") (pinfunction "P34_34") (pintype "passive"))
    )
    (net (code "257") (name "unconnected-(M.2KEYM(NGFF)-P35-Pad35)") (class "Default")
      (node (ref "M.2KEYM(NGFF)") (pin "35") (pinfunction "P35_35") (pintype "passive"))
    )
    (net (code "258") (name "unconnected-(M.2KEYM(NGFF)-P36-Pad36)") (class "Default")
      (node (ref "M.2KEYM(NGFF)") (pin "36") (pinfunction "P36_36") (pintype "passive"))
    )
    (net (code "259") (name "unconnected-(M.2KEYM(NGFF)-P37-Pad37)") (class "Default")
      (node (ref "M.2KEYM(NGFF)") (pin "37") (pinfunction "P37_37") (pintype "passive"))
    )
    (net (code "260") (name "unconnected-(M.2KEYM(NGFF)-P38-Pad38)") (class "Default")
      (node (ref "M.2KEYM(NGFF)") (pin "38") (pinfunction "P38_38") (pintype "passive"))
    )
    (net (code "261") (name "unconnected-(M.2KEYM(NGFF)-P40-Pad40)") (class "Default")
      (node (ref "M.2KEYM(NGFF)") (pin "40") (pinfunction "P40_40") (pintype "passive"))
    )
    (net (code "262") (name "unconnected-(M.2KEYM(NGFF)-P42-Pad42)") (class "Default")
      (node (ref "M.2KEYM(NGFF)") (pin "42") (pinfunction "P42_42") (pintype "passive"))
    )
    (net (code "263") (name "unconnected-(M.2KEYM(NGFF)-P44-Pad44)") (class "Default")
      (node (ref "M.2KEYM(NGFF)") (pin "44") (pinfunction "P44_44") (pintype "passive"))
    )
    (net (code "264") (name "unconnected-(M.2KEYM(NGFF)-P46-Pad46)") (class "Default")
      (node (ref "M.2KEYM(NGFF)") (pin "46") (pinfunction "P46_46") (pintype "passive"))
    )
    (net (code "265") (name "unconnected-(M.2KEYM(NGFF)-P48-Pad48)") (class "Default")
      (node (ref "M.2KEYM(NGFF)") (pin "48") (pinfunction "P48_48") (pintype "passive"))
    )
    (net (code "266") (name "unconnected-(M.2KEYM(NGFF)-P54-Pad54)") (class "Default")
      (node (ref "M.2KEYM(NGFF)") (pin "54") (pinfunction "P54_54") (pintype "passive"))
    )
    (net (code "267") (name "unconnected-(M.2KEYM(NGFF)-P56-Pad56)") (class "Default")
      (node (ref "M.2KEYM(NGFF)") (pin "56") (pinfunction "P56_56") (pintype "passive"))
    )
    (net (code "268") (name "unconnected-(M.2KEYM(NGFF)-P58-Pad58)") (class "Default")
      (node (ref "M.2KEYM(NGFF)") (pin "58") (pinfunction "P58_58") (pintype "passive"))
    )
    (net (code "269") (name "unconnected-(M.2KEYM(NGFF)-P67-Pad67)") (class "Default")
      (node (ref "M.2KEYM(NGFF)") (pin "67") (pinfunction "P67_67") (pintype "passive"))
    )
    (net (code "270") (name "unconnected-(M.2KEYM(NGFF)-P68-Pad68)") (class "Default")
      (node (ref "M.2KEYM(NGFF)") (pin "68") (pinfunction "P68_68") (pintype "passive"))
    )
    (net (code "271") (name "unconnected-(M.2KEYM(NGFF)-P69-Pad69)") (class "Default")
      (node (ref "M.2KEYM(NGFF)") (pin "69") (pinfunction "P69_69") (pintype "passive"))
    )
    (net (code "272") (name "unconnected-(RPI-CM1A-ANALOGP0-Pad96)") (class "Default")
      (node (ref "RPI-CM1") (pin "96") (pinfunction "ANALOGP0_96") (pintype "passive"))
    )
    (net (code "273") (name "unconnected-(RPI-CM1A-ANALOGP1-Pad94)") (class "Default")
      (node (ref "RPI-CM1") (pin "94") (pinfunction "ANALOGP1_94") (pintype "passive"))
    )
    (net (code "274") (name "unconnected-(RPI-CM1A-BT_~{DISABLE}-Pad91)") (class "Default")
      (node (ref "RPI-CM1") (pin "91") (pinfunction "BT_~{DISABLE}_91") (pintype "passive"))
    )
    (net (code "275") (name "unconnected-(RPI-CM1A-EEPROM_~{WP}-Pad20)") (class "Default")
      (node (ref "RPI-CM1") (pin "20") (pinfunction "EEPROM_~{WP}_20") (pintype "passive"))
    )
    (net (code "276") (name "unconnected-(RPI-CM1A-ETH_PAIR0_N-Pad10)") (class "Default")
      (node (ref "RPI-CM1") (pin "10") (pinfunction "ETH_PAIR0_N_10") (pintype "passive"))
    )
    (net (code "277") (name "unconnected-(RPI-CM1A-ETH_PAIR0_P-Pad12)") (class "Default")
      (node (ref "RPI-CM1") (pin "12") (pinfunction "ETH_PAIR0_P_12") (pintype "passive"))
    )
    (net (code "278") (name "unconnected-(RPI-CM1A-ETH_PAIR1_N-Pad6)") (class "Default")
      (node (ref "RPI-CM1") (pin "6") (pinfunction "ETH_PAIR1_N_6") (pintype "passive"))
    )
    (net (code "279") (name "unconnected-(RPI-CM1A-ETH_PAIR1_P-Pad4)") (class "Default")
      (node (ref "RPI-CM1") (pin "4") (pinfunction "ETH_PAIR1_P_4") (pintype "passive"))
    )
    (net (code "280") (name "unconnected-(RPI-CM1A-ETH_PAIR2_N-Pad9)") (class "Default")
      (node (ref "RPI-CM1") (pin "9") (pinfunction "ETH_PAIR2_N_9") (pintype "passive"))
    )
    (net (code "281") (name "unconnected-(RPI-CM1A-ETH_PAIR2_P-Pad11)") (class "Default")
      (node (ref "RPI-CM1") (pin "11") (pinfunction "ETH_PAIR2_P_11") (pintype "passive"))
    )
    (net (code "282") (name "unconnected-(RPI-CM1A-ETH_PAIR3_N-Pad5)") (class "Default")
      (node (ref "RPI-CM1") (pin "5") (pinfunction "ETH_PAIR3_N_5") (pintype "passive"))
    )
    (net (code "283") (name "unconnected-(RPI-CM1A-ETH_PAIR3_P-Pad3)") (class "Default")
      (node (ref "RPI-CM1") (pin "3") (pinfunction "ETH_PAIR3_P_3") (pintype "passive"))
    )
    (net (code "284") (name "unconnected-(RPI-CM1A-ETH_SYNC_IN-Pad16)") (class "Default")
      (node (ref "RPI-CM1") (pin "16") (pinfunction "ETH_SYNC_IN_16") (pintype "passive"))
    )
    (net (code "285") (name "unconnected-(RPI-CM1A-ETH_SYNC_OUT-Pad18)") (class "Default")
      (node (ref "RPI-CM1") (pin "18") (pinfunction "ETH_SYNC_OUT_18") (pintype "passive"))
    )
    (net (code "286") (name "unconnected-(RPI-CM1A-ETH_~{LED1}-Pad19)") (class "Default")
      (node (ref "RPI-CM1") (pin "19") (pinfunction "ETH_~{LED1}_19") (pintype "passive"))
    )
    (net (code "287") (name "unconnected-(RPI-CM1A-ETH_~{LED2}-Pad17)") (class "Default")
      (node (ref "RPI-CM1") (pin "17") (pinfunction "ETH_~{LED2}_17") (pintype "passive"))
    )
    (net (code "288") (name "unconnected-(RPI-CM1A-ETH_~{LED3}-Pad15)") (class "Default")
      (node (ref "RPI-CM1") (pin "15") (pinfunction "ETH_~{LED3}_15") (pintype "passive"))
    )
    (net (code "289") (name "unconnected-(RPI-CM1A-GLOBAL_EN-Pad99)") (class "Default")
      (node (ref "RPI-CM1") (pin "99") (pinfunction "GLOBAL_EN_99") (pintype "passive"))
    )
    (net (code "290") (name "unconnected-(RPI-CM1A-GPIO7-Pad37)") (class "Default")
      (node (ref "RPI-CM1") (pin "37") (pinfunction "GPIO7_37") (pintype "passive"))
    )
    (net (code "291") (name "unconnected-(RPI-CM1A-GPIO12-Pad31)") (class "Default")
      (node (ref "RPI-CM1") (pin "31") (pinfunction "GPIO12_31") (pintype "passive"))
    )
    (net (code "292") (name "unconnected-(RPI-CM1A-GPIO17-Pad50)") (class "Default")
      (node (ref "RPI-CM1") (pin "50") (pinfunction "GPIO17_50") (pintype "passive"))
    )
    (net (code "293") (name "unconnected-(RPI-CM1A-GPIO23-Pad47)") (class "Default")
      (node (ref "RPI-CM1") (pin "47") (pinfunction "GPIO23_47") (pintype "passive"))
    )
    (net (code "294") (name "unconnected-(RPI-CM1A-GPIO24-Pad45)") (class "Default")
      (node (ref "RPI-CM1") (pin "45") (pinfunction "GPIO24_45") (pintype "passive"))
    )
    (net (code "295") (name "unconnected-(RPI-CM1A-GPIO25-Pad41)") (class "Default")
      (node (ref "RPI-CM1") (pin "41") (pinfunction "GPIO25_41") (pintype "passive"))
    )
    (net (code "296") (name "unconnected-(RPI-CM1A-GPIO26-Pad24)") (class "Default")
      (node (ref "RPI-CM1") (pin "24") (pinfunction "GPIO26_24") (pintype "passive"))
    )
    (net (code "297") (name "unconnected-(RPI-CM1A-GPIO27-Pad48)") (class "Default")
      (node (ref "RPI-CM1") (pin "48") (pinfunction "GPIO27_48") (pintype "passive"))
    )
    (net (code "298") (name "unconnected-(RPI-CM1A-ID_SC-Pad35)") (class "Default")
      (node (ref "RPI-CM1") (pin "35") (pinfunction "ID_SC_35") (pintype "passive"))
    )
    (net (code "299") (name "unconnected-(RPI-CM1A-ID_SD-Pad36)") (class "Default")
      (node (ref "RPI-CM1") (pin "36") (pinfunction "ID_SD_36") (pintype "passive"))
    )
    (net (code "300") (name "unconnected-(RPI-CM1A-RESERVED-Pad76)") (class "Default")
      (node (ref "RPI-CM1") (pin "76") (pinfunction "RESERVED_76") (pintype "passive"))
    )
    (net (code "301") (name "unconnected-(RPI-CM1A-RUN_PG-Pad92)") (class "Default")
      (node (ref "RPI-CM1") (pin "92") (pinfunction "RUN_PG_92") (pintype "passive"))
    )
    (net (code "302") (name "unconnected-(RPI-CM1A-SD_CLK-Pad57)") (class "Default")
      (node (ref "RPI-CM1") (pin "57") (pinfunction "SD_CLK_57") (pintype "passive"))
    )
    (net (code "303") (name "unconnected-(RPI-CM1A-SD_CMD-Pad62)") (class "Default")
      (node (ref "RPI-CM1") (pin "62") (pinfunction "SD_CMD_62") (pintype "passive"))
    )
    (net (code "304") (name "unconnected-(RPI-CM1A-SD_DAT0-Pad63)") (class "Default")
      (node (ref "RPI-CM1") (pin "63") (pinfunction "SD_DAT0_63") (pintype "passive"))
    )
    (net (code "305") (name "unconnected-(RPI-CM1A-SD_DAT1-Pad67)") (class "Default")
      (node (ref "RPI-CM1") (pin "67") (pinfunction "SD_DAT1_67") (pintype "passive"))
    )
    (net (code "306") (name "unconnected-(RPI-CM1A-SD_DAT2-Pad69)") (class "Default")
      (node (ref "RPI-CM1") (pin "69") (pinfunction "SD_DAT2_69") (pintype "passive"))
    )
    (net (code "307") (name "unconnected-(RPI-CM1A-SD_DAT3-Pad61)") (class "Default")
      (node (ref "RPI-CM1") (pin "61") (pinfunction "SD_DAT3_61") (pintype "passive"))
    )
    (net (code "308") (name "unconnected-(RPI-CM1A-SD_DAT4-Pad68)") (class "Default")
      (node (ref "RPI-CM1") (pin "68") (pinfunction "SD_DAT4_68") (pintype "passive"))
    )
    (net (code "309") (name "unconnected-(RPI-CM1A-SD_DAT5-Pad64)") (class "Default")
      (node (ref "RPI-CM1") (pin "64") (pinfunction "SD_DAT5_64") (pintype "passive"))
    )
    (net (code "310") (name "unconnected-(RPI-CM1A-SD_DAT6-Pad72)") (class "Default")
      (node (ref "RPI-CM1") (pin "72") (pinfunction "SD_DAT6_72") (pintype "passive"))
    )
    (net (code "311") (name "unconnected-(RPI-CM1A-SD_DAT7-Pad70)") (class "Default")
      (node (ref "RPI-CM1") (pin "70") (pinfunction "SD_DAT7_70") (pintype "passive"))
    )
    (net (code "312") (name "unconnected-(RPI-CM1A-SD_PWR_ON-Pad75)") (class "Default")
      (node (ref "RPI-CM1") (pin "75") (pinfunction "SD_PWR_ON_75") (pintype "passive"))
    )
    (net (code "313") (name "unconnected-(RPI-CM1A-SD_VDD_OVERRIDE-Pad73)") (class "Default")
      (node (ref "RPI-CM1") (pin "73") (pinfunction "SD_VDD_OVERRIDE_73") (pintype "passive"))
    )
    (net (code "314") (name "unconnected-(RPI-CM1A-WL_~{DISABLE}-Pad89)") (class "Default")
      (node (ref "RPI-CM1") (pin "89") (pinfunction "WL_~{DISABLE}_89") (pintype "passive"))
    )
    (net (code "315") (name "unconnected-(RPI-CM1A-~{EXTRST}-Pad100)") (class "Default")
      (node (ref "RPI-CM1") (pin "100") (pinfunction "~{EXTRST}_100") (pintype "passive"))
    )
    (net (code "316") (name "unconnected-(U2-NC-Pad1)") (class "Default")
      (node (ref "U2") (pin "1") (pinfunction "NC_1") (pintype "no_connect"))
    )
    (net (code "317") (name "unconnected-(U4-~{PGOOD}-Pad7)") (class "Default")
      (node (ref "U4") (pin "7") (pinfunction "~{PGOOD}_7") (pintype "bidirectional"))
    )
    (net (code "318") (name "unconnected-(U5-NC-Pad1)") (class "Default")
      (node (ref "U5") (pin "1") (pinfunction "NC_1") (pintype "no_connect"))
    )
    (net (code "319") (name "unconnected-(U6-CS-Pad12)") (class "Default")
      (node (ref "U6") (pin "12") (pinfunction "CS_12") (pintype "bidirectional"))
    )
    (net (code "320") (name "unconnected-(U6-INT1-Pad4)") (class "Default")
      (node (ref "U6") (pin "4") (pinfunction "INT1_4") (pintype "bidirectional"))
    )
    (net (code "321") (name "unconnected-(U6-INT2-Pad9)") (class "Default")
      (node (ref "U6") (pin "9") (pinfunction "INT2_9") (pintype "bidirectional"))
    )
    (net (code "322") (name "unconnected-(U6-SCX-Pad3)") (class "Default")
      (node (ref "U6") (pin "3") (pinfunction "SCX_3") (pintype "bidirectional"))
    )
    (net (code "323") (name "unconnected-(U6-SDX-Pad2)") (class "Default")
      (node (ref "U6") (pin "2") (pinfunction "SDX_2") (pintype "bidirectional"))
    )
    (net (code "324") (name "unconnected-(U9-CLK-Pad7)") (class "Default")
      (node (ref "U9") (pin "7") (pinfunction "CLK_7") (pintype "bidirectional"))
    )
    (net (code "325") (name "unconnected-(U9-~{ALERT}-Pad8)") (class "Default")
      (node (ref "U9") (pin "8") (pinfunction "~{ALERT}_8") (pintype "output"))
    )
    (net (code "326") (name "unconnected-(U10-P4-Pad4)") (class "Default")
      (node (ref "U10") (pin "4") (pinfunction "P4_4") (pintype "bidirectional"))
    )
    (net (code "327") (name "unconnected-(U11-P4-Pad4)") (class "Default")
      (node (ref "U11") (pin "4") (pinfunction "P4_4") (pintype "bidirectional"))
    )
    (net (code "328") (name "unconnected-(U13-D1+-Pad1)") (class "Default")
      (node (ref "U13") (pin "1") (pinfunction "D1+_1") (pintype "passive"))
    )
    (net (code "329") (name "unconnected-(U13-D1--Pad2)") (class "Default")
      (node (ref "U13") (pin "2") (pinfunction "D1-_2") (pintype "passive"))
    )
    (net (code "330") (name "unconnected-(U13-NC-Pad10)") (class "Default")
      (node (ref "U13") (pin "10") (pinfunction "NC_10") (pintype "passive"))
    )
    (net (code "331") (name "unconnected-(U13-NC_2-Pad6)") (class "Default")
      (node (ref "U13") (pin "6") (pinfunction "NC_2_6") (pintype "passive"))
    )
    (net (code "332") (name "unconnected-(U13-NC_3-Pad7)") (class "Default")
      (node (ref "U13") (pin "7") (pinfunction "NC_3_7") (pintype "passive"))
    )
    (net (code "333") (name "unconnected-(U13-NC_4-Pad9)") (class "Default")
      (node (ref "U13") (pin "9") (pinfunction "NC_4_9") (pintype "passive"))
    )
    (net (code "334") (name "unconnected-(U15-P4-Pad4)") (class "Default")
      (node (ref "U15") (pin "4") (pinfunction "P4_4") (pintype "bidirectional"))
    )
    (net (code "335") (name "unconnected-(USB2.0MUX-D2+-Pad2)") (class "Default")
      (node (ref "USB2.0MUX") (pin "2") (pinfunction "D2+_2") (pintype "bidirectional"))
    )
    (net (code "336") (name "unconnected-(USB2.0MUX-D2--Pad6)") (class "Default")
      (node (ref "USB2.0MUX") (pin "6") (pinfunction "D2-_6") (pintype "bidirectional"))
    )
  )
)
